# PixHawk_Fire_v1_4.net
KiCad netlist of a schematic drawn in EAGLE
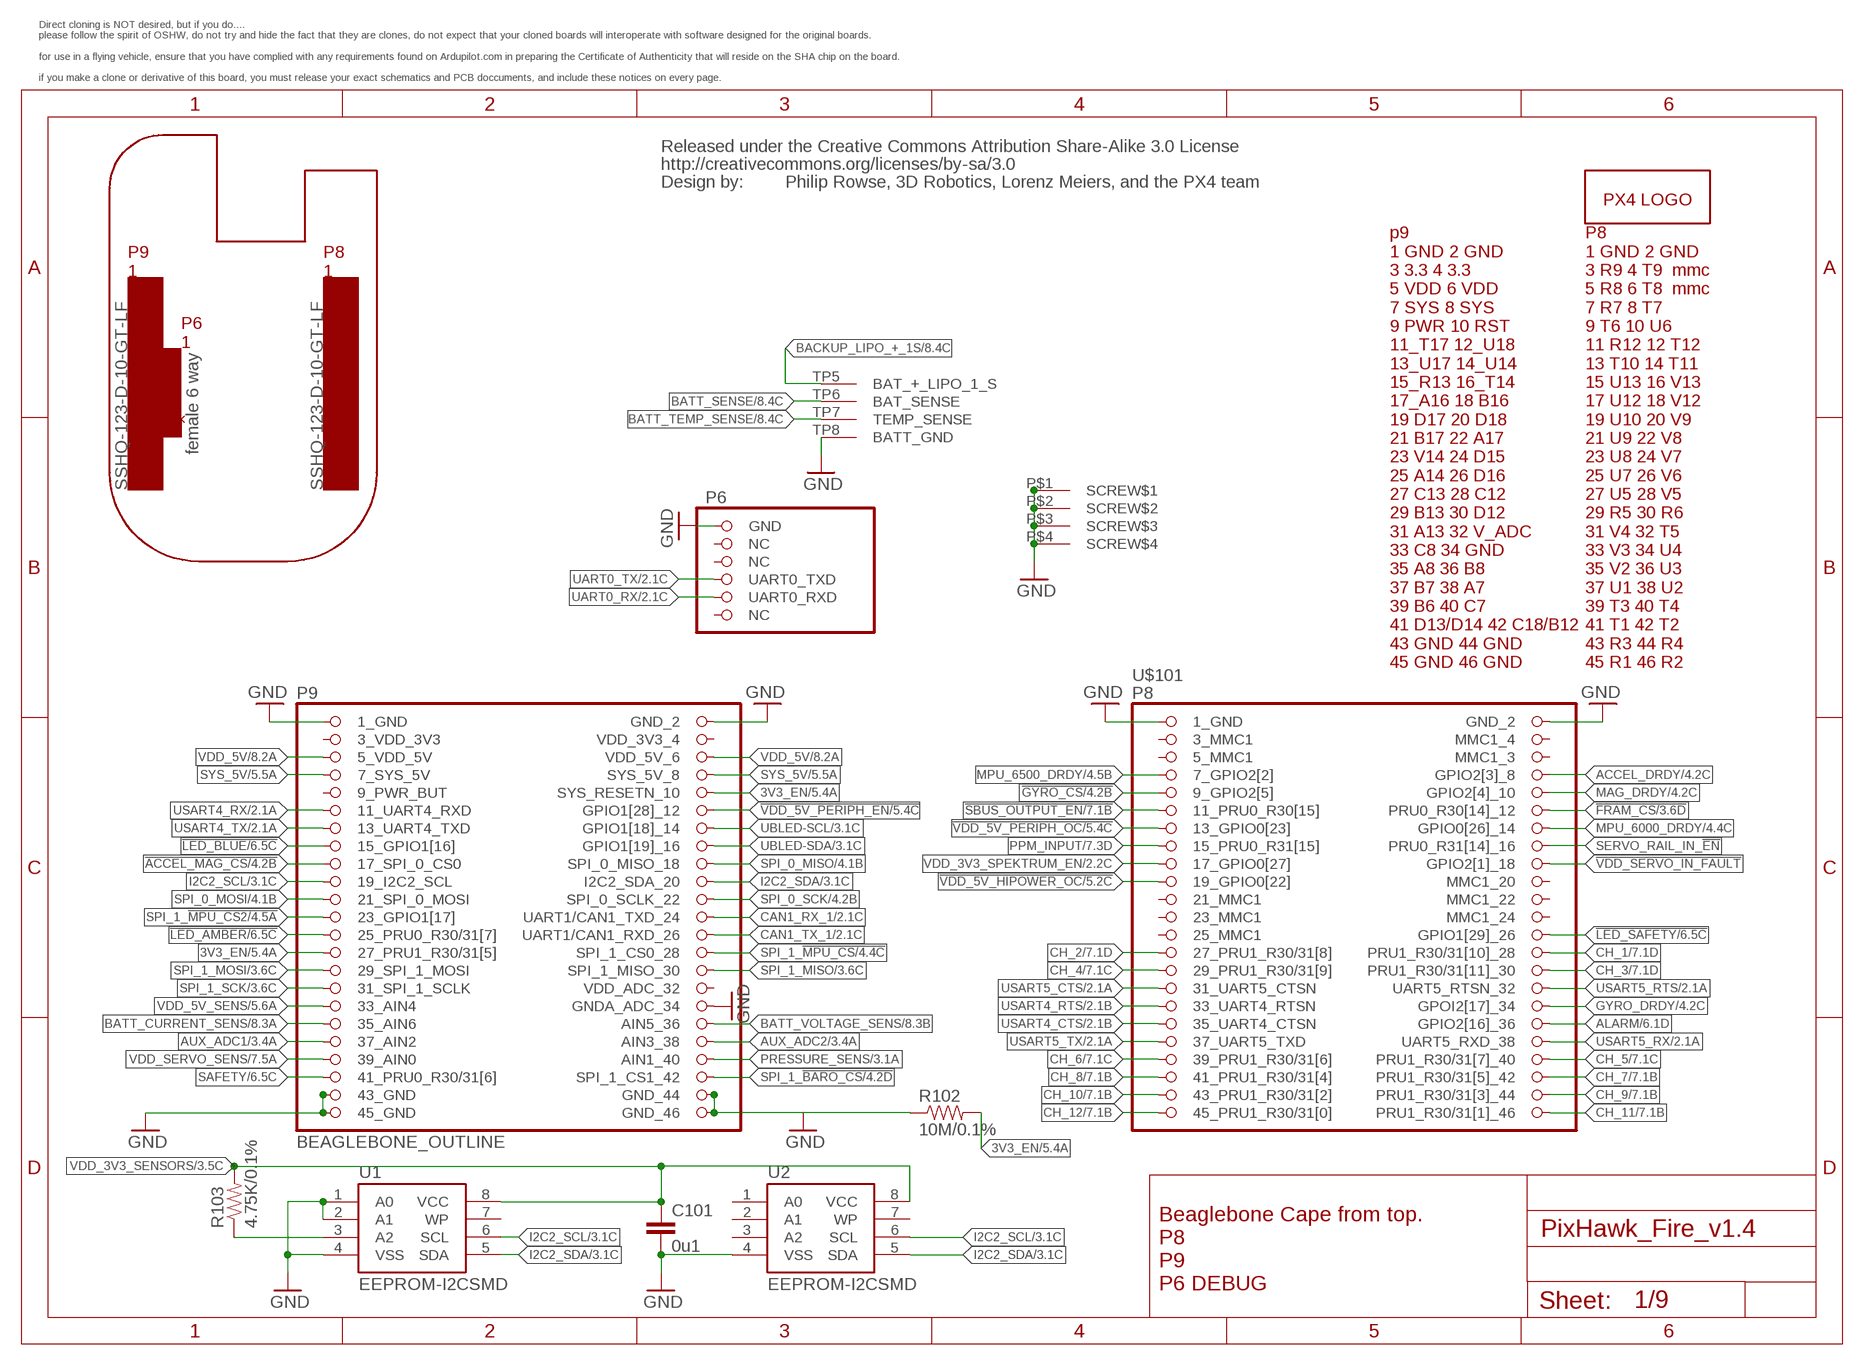
[diagram p0: schematic, sheet 1]
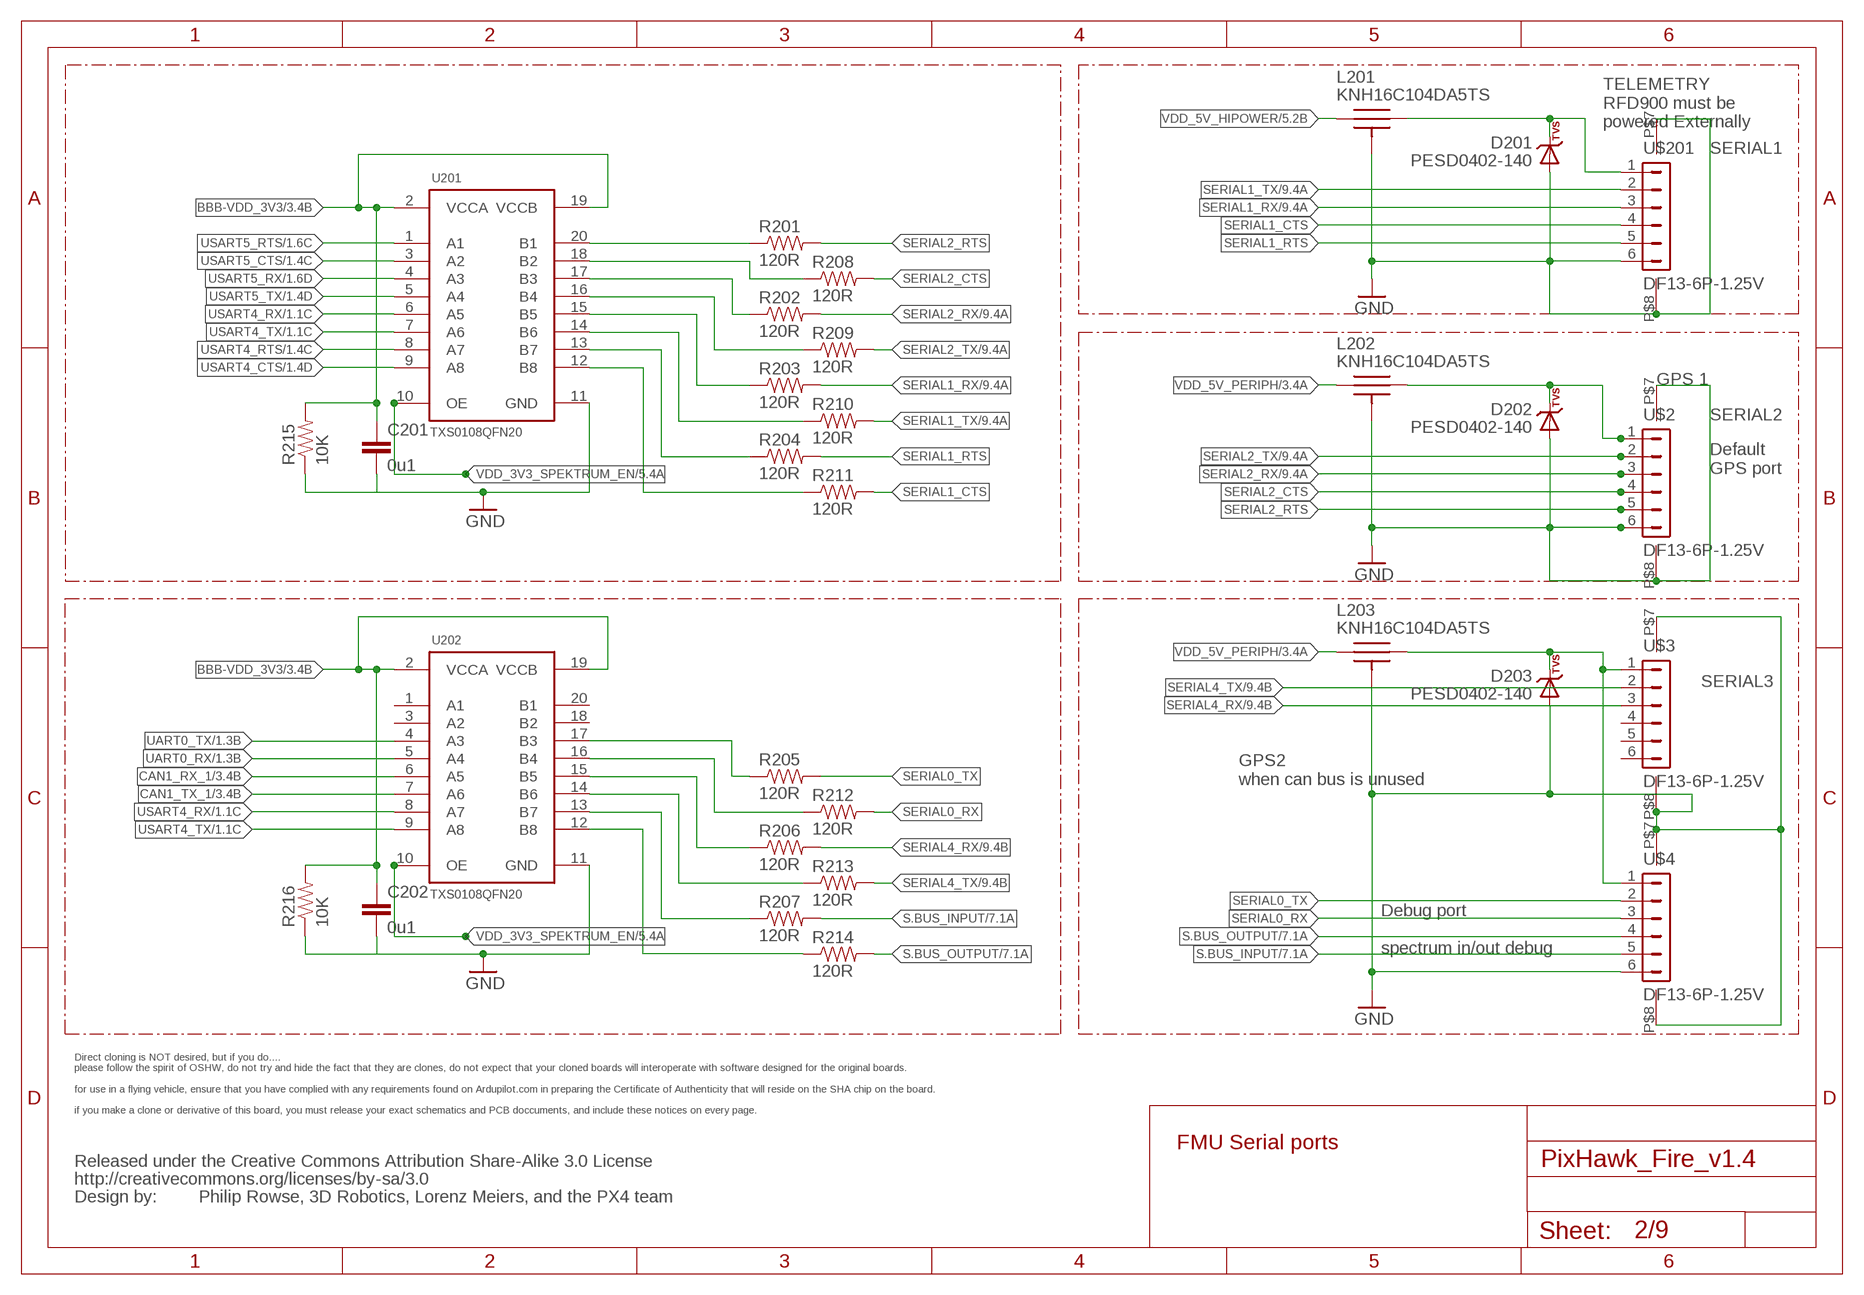
[diagram p1: schematic, sheet 2]
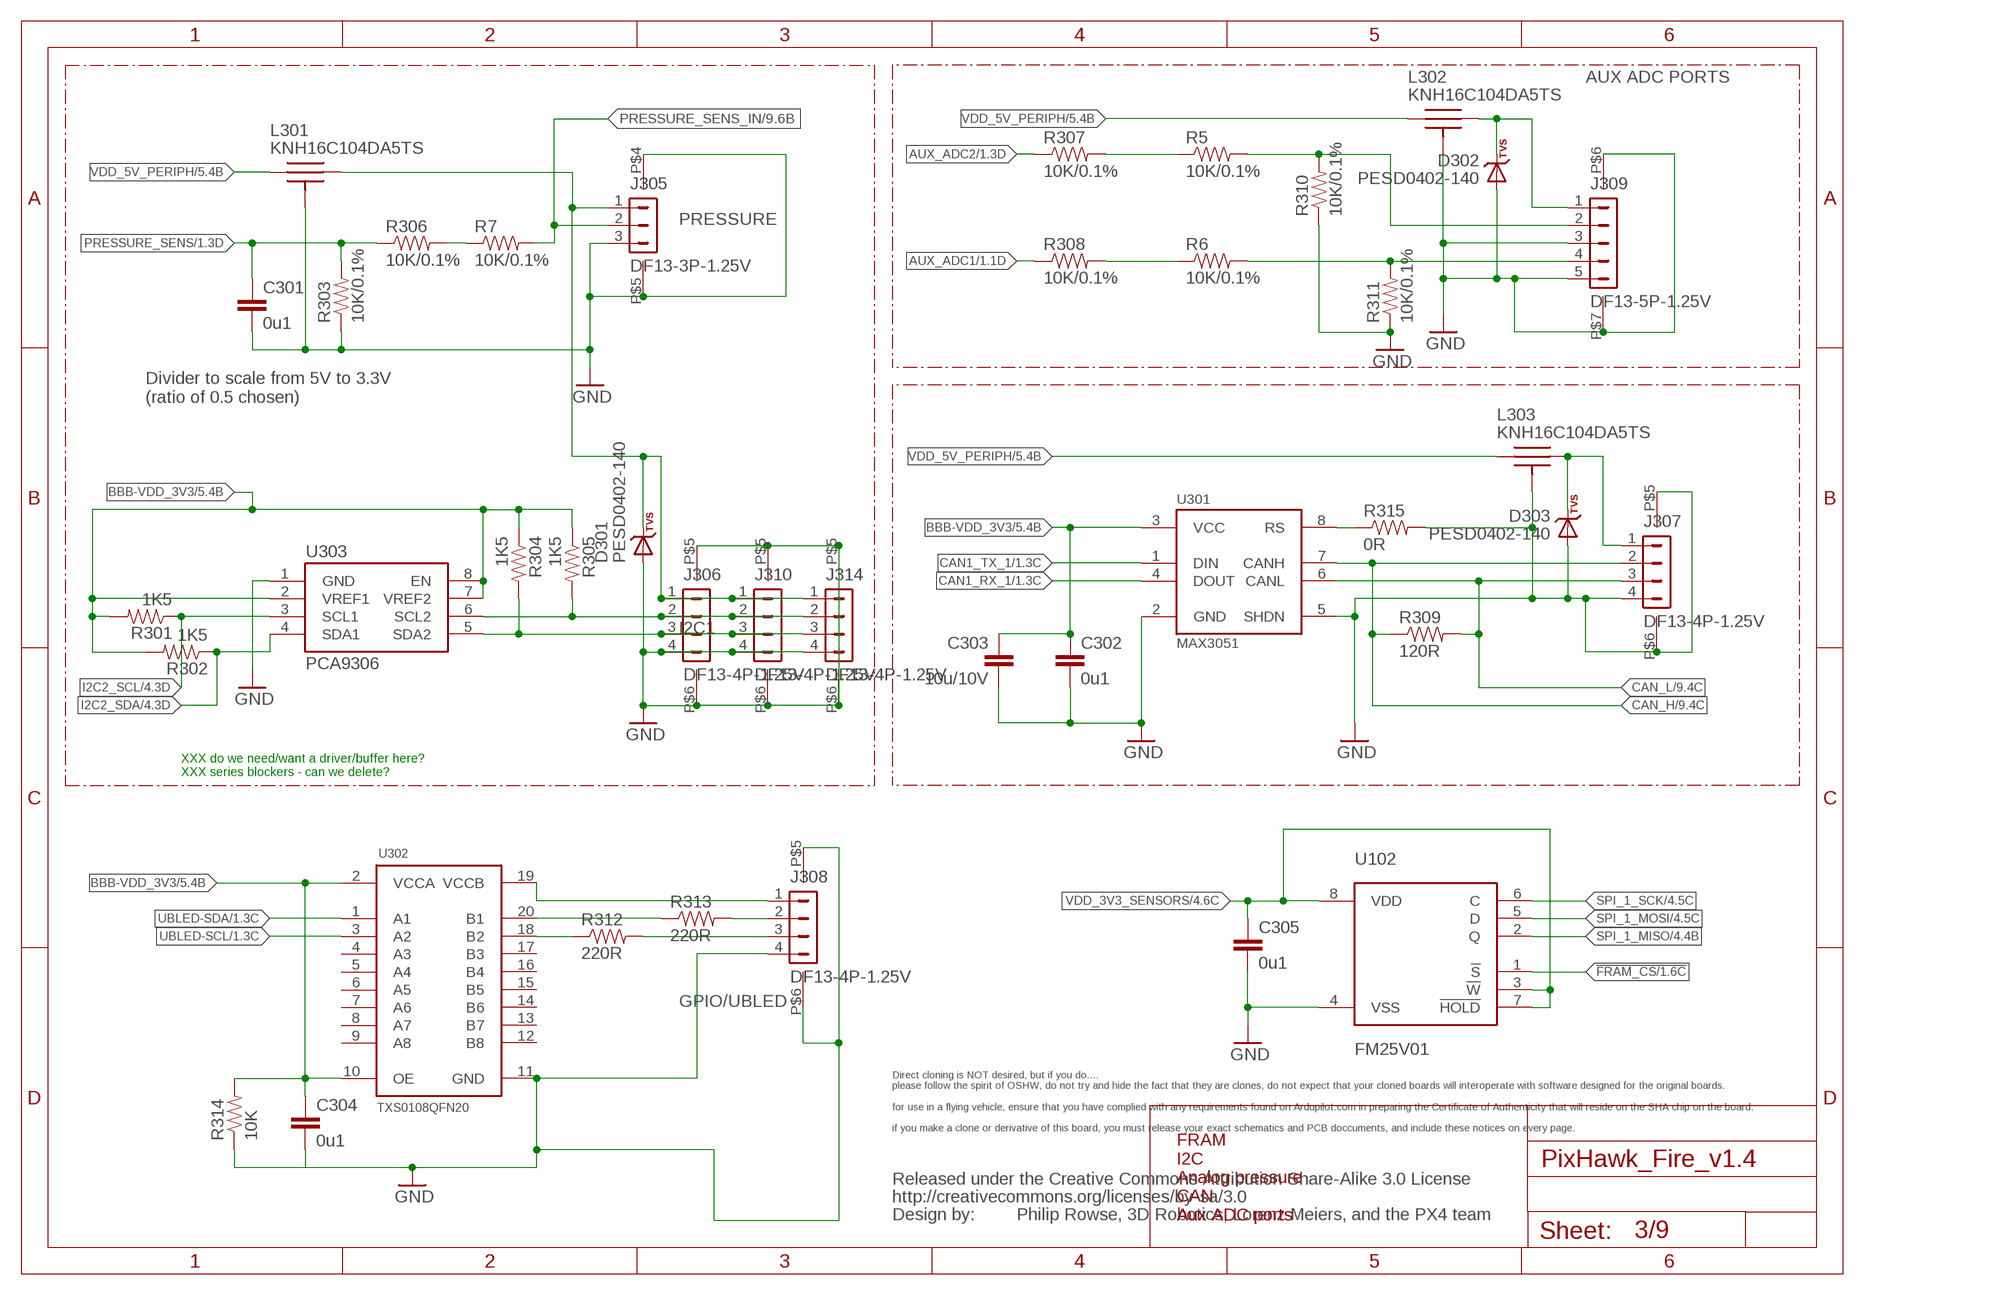
[diagram p2: schematic, sheet 3]
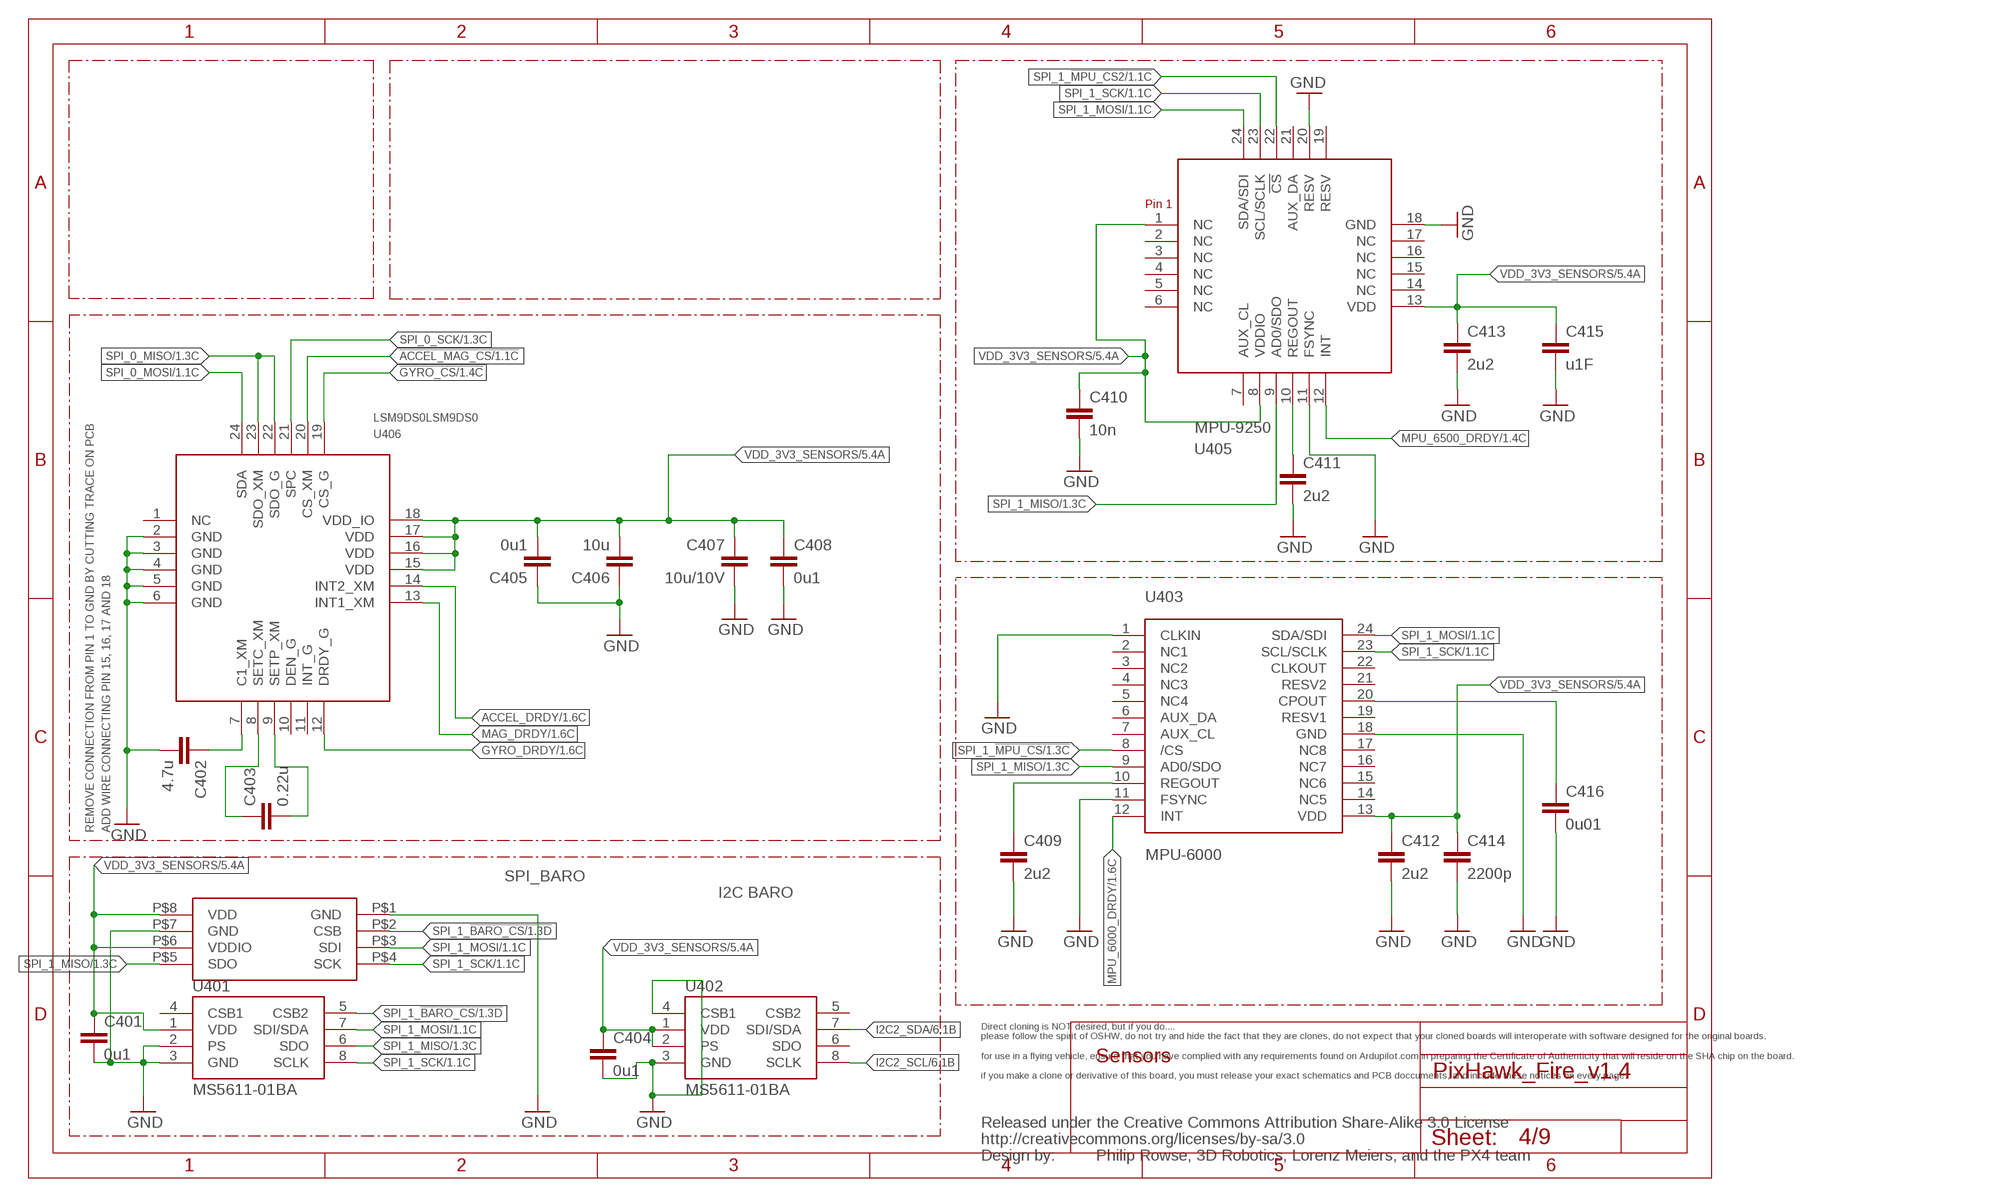
[diagram p3: schematic, sheet 4]
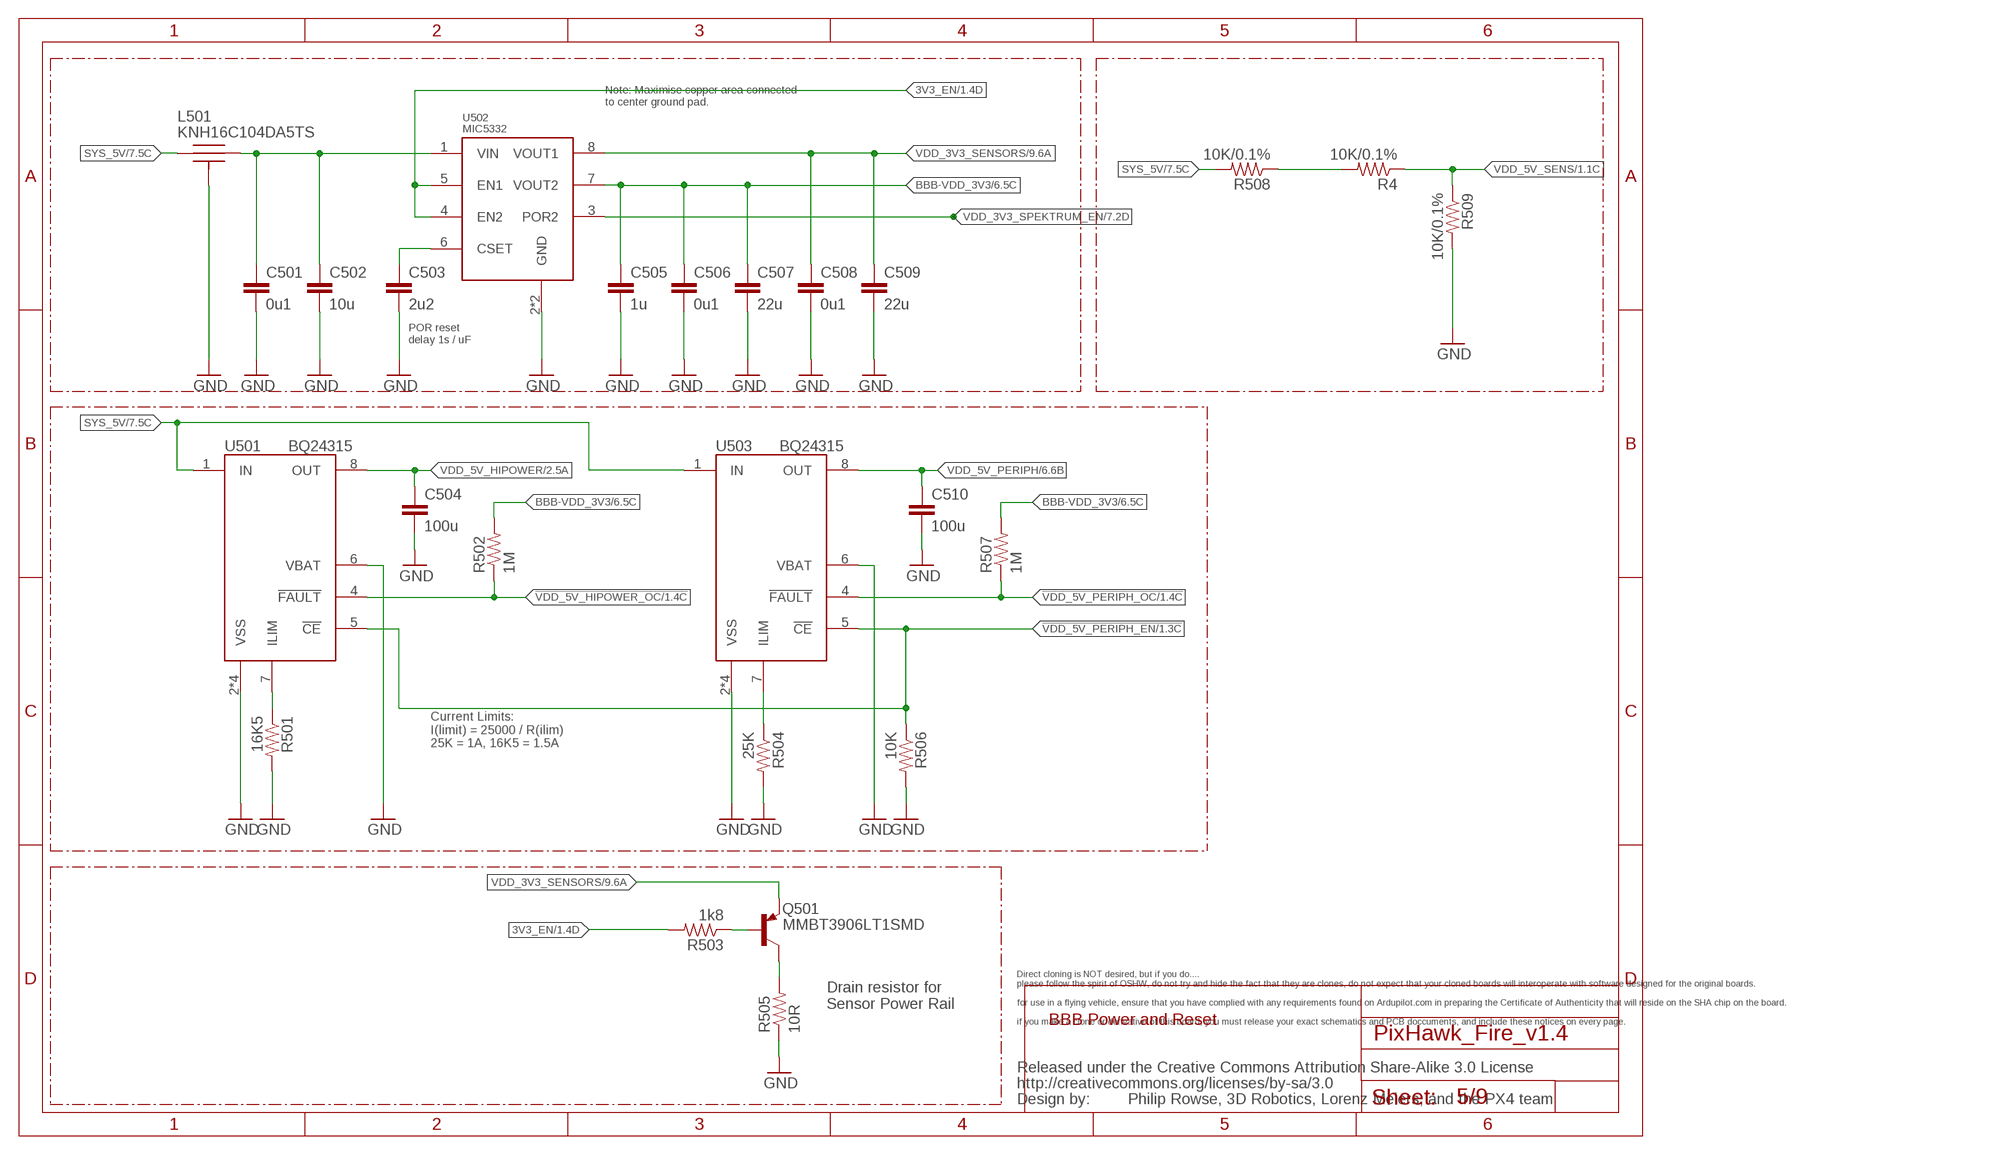
[diagram p4: schematic, sheet 5]
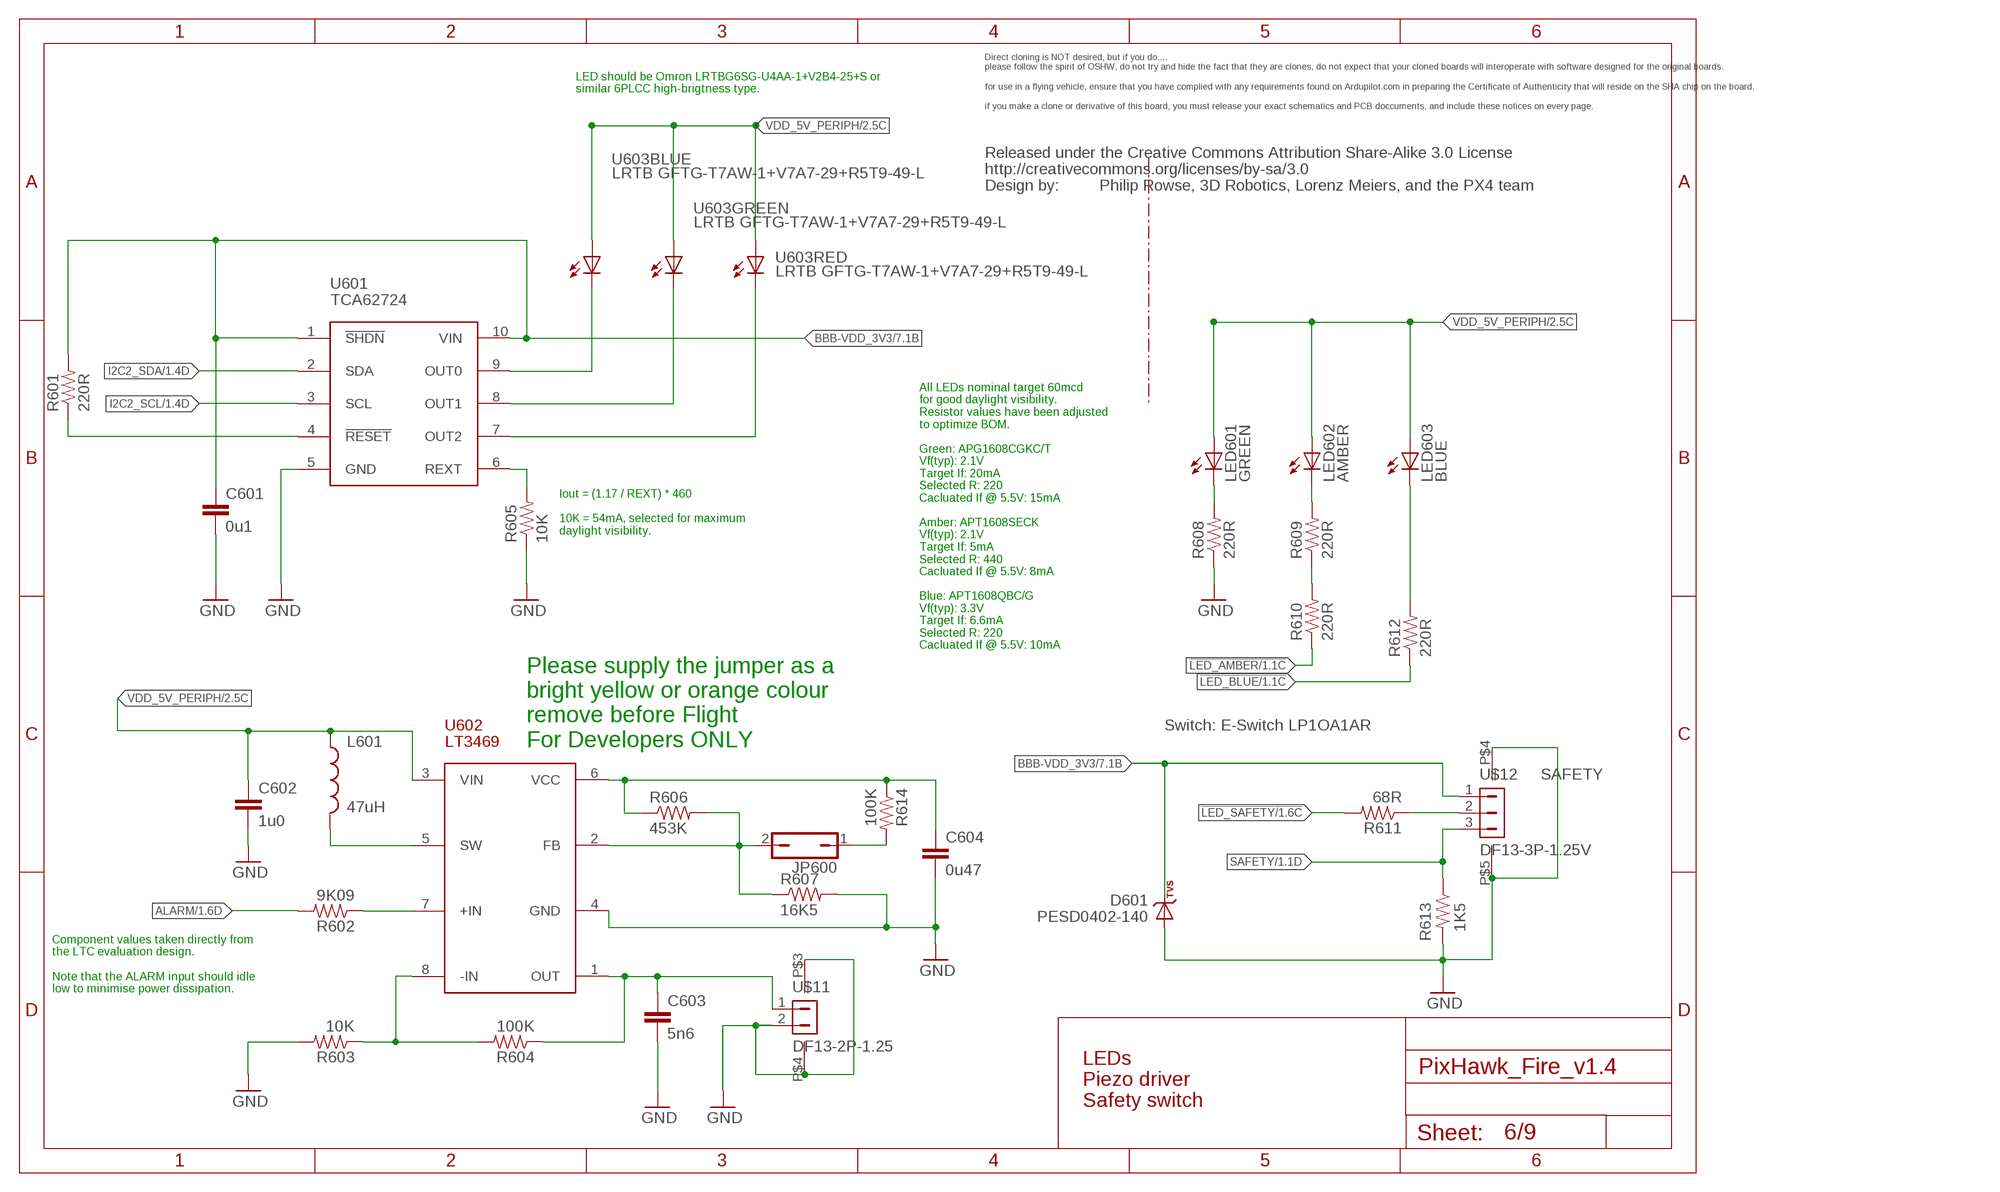
[diagram p5: schematic, sheet 6]
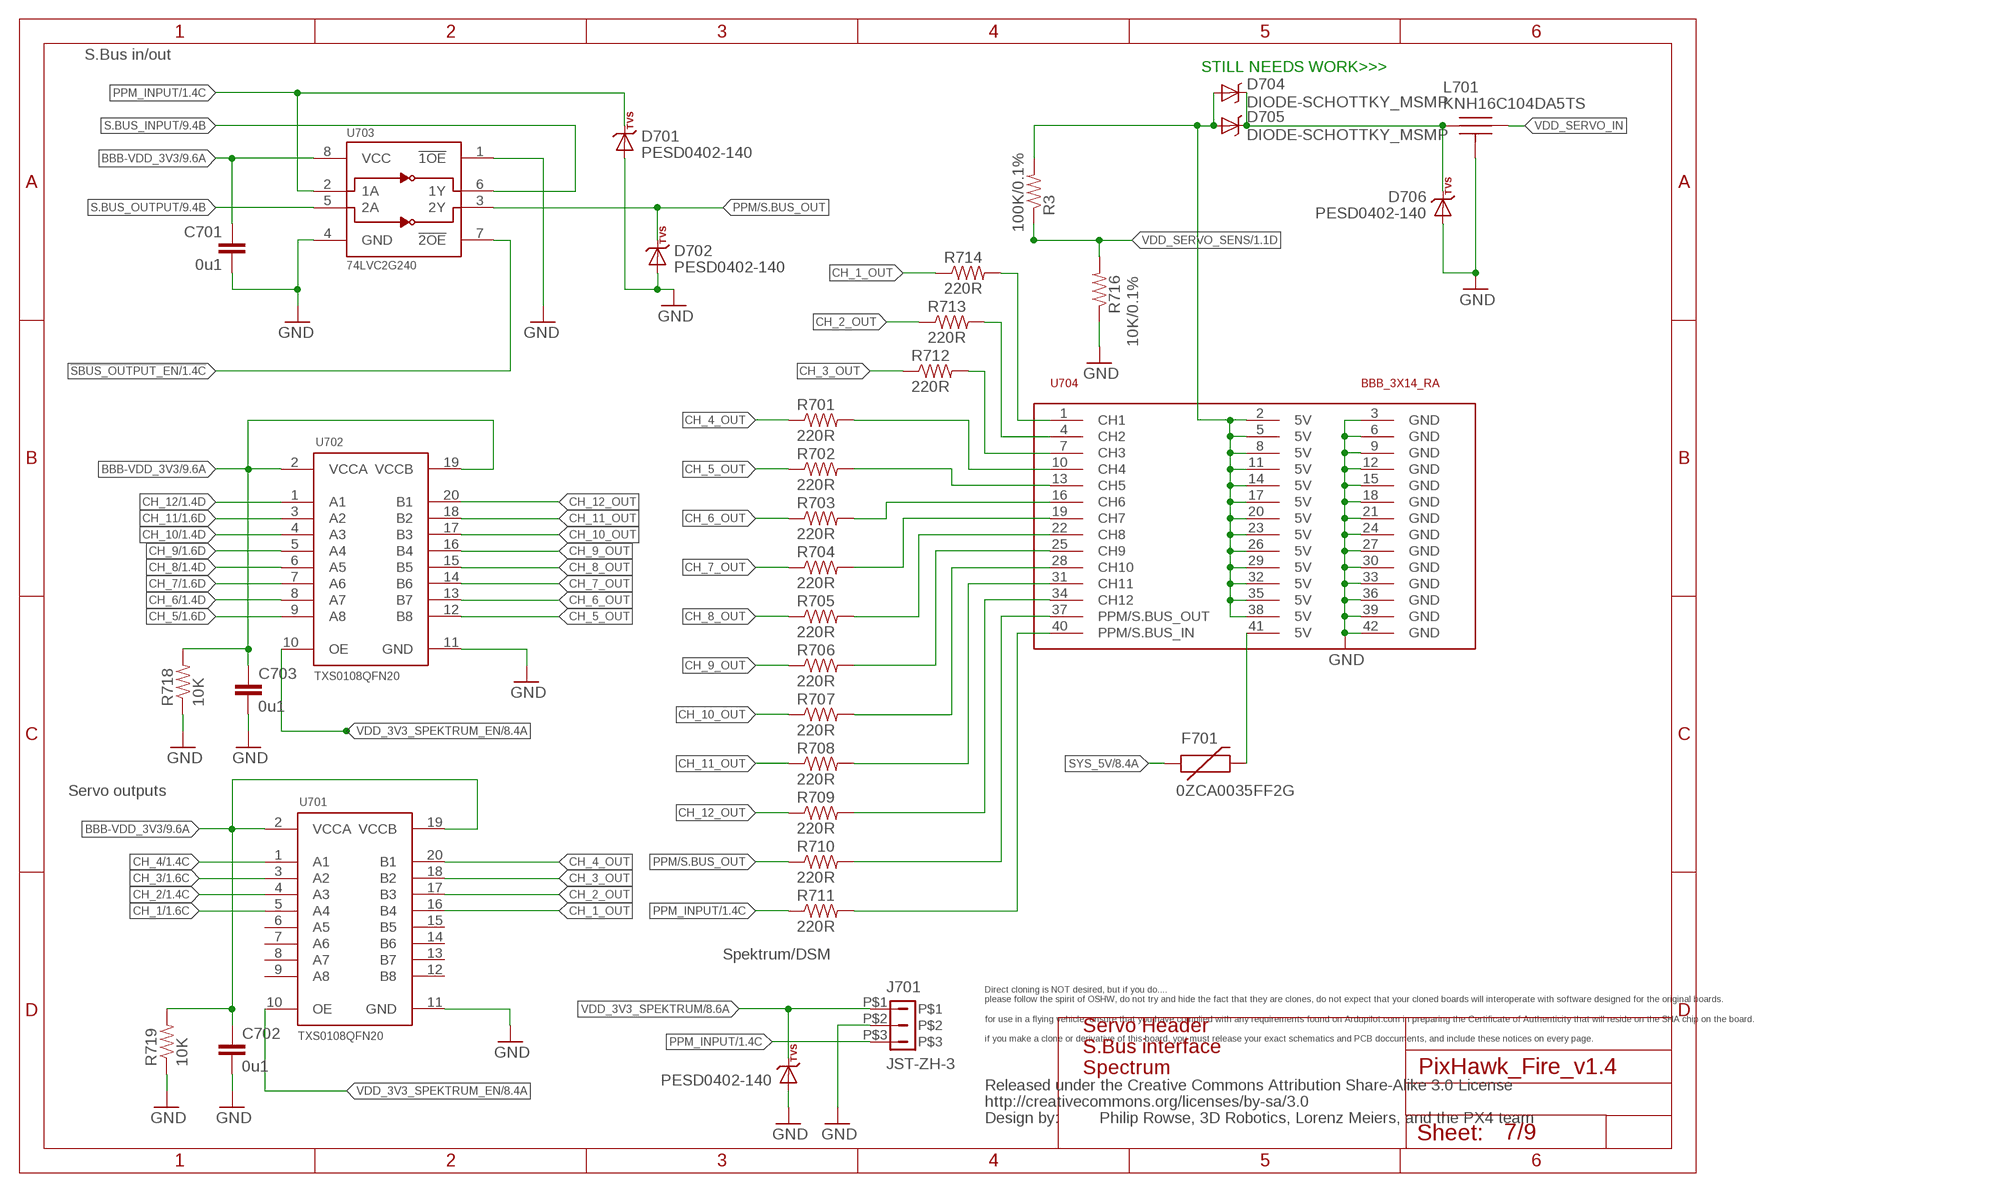
[diagram p6: schematic, sheet 7]
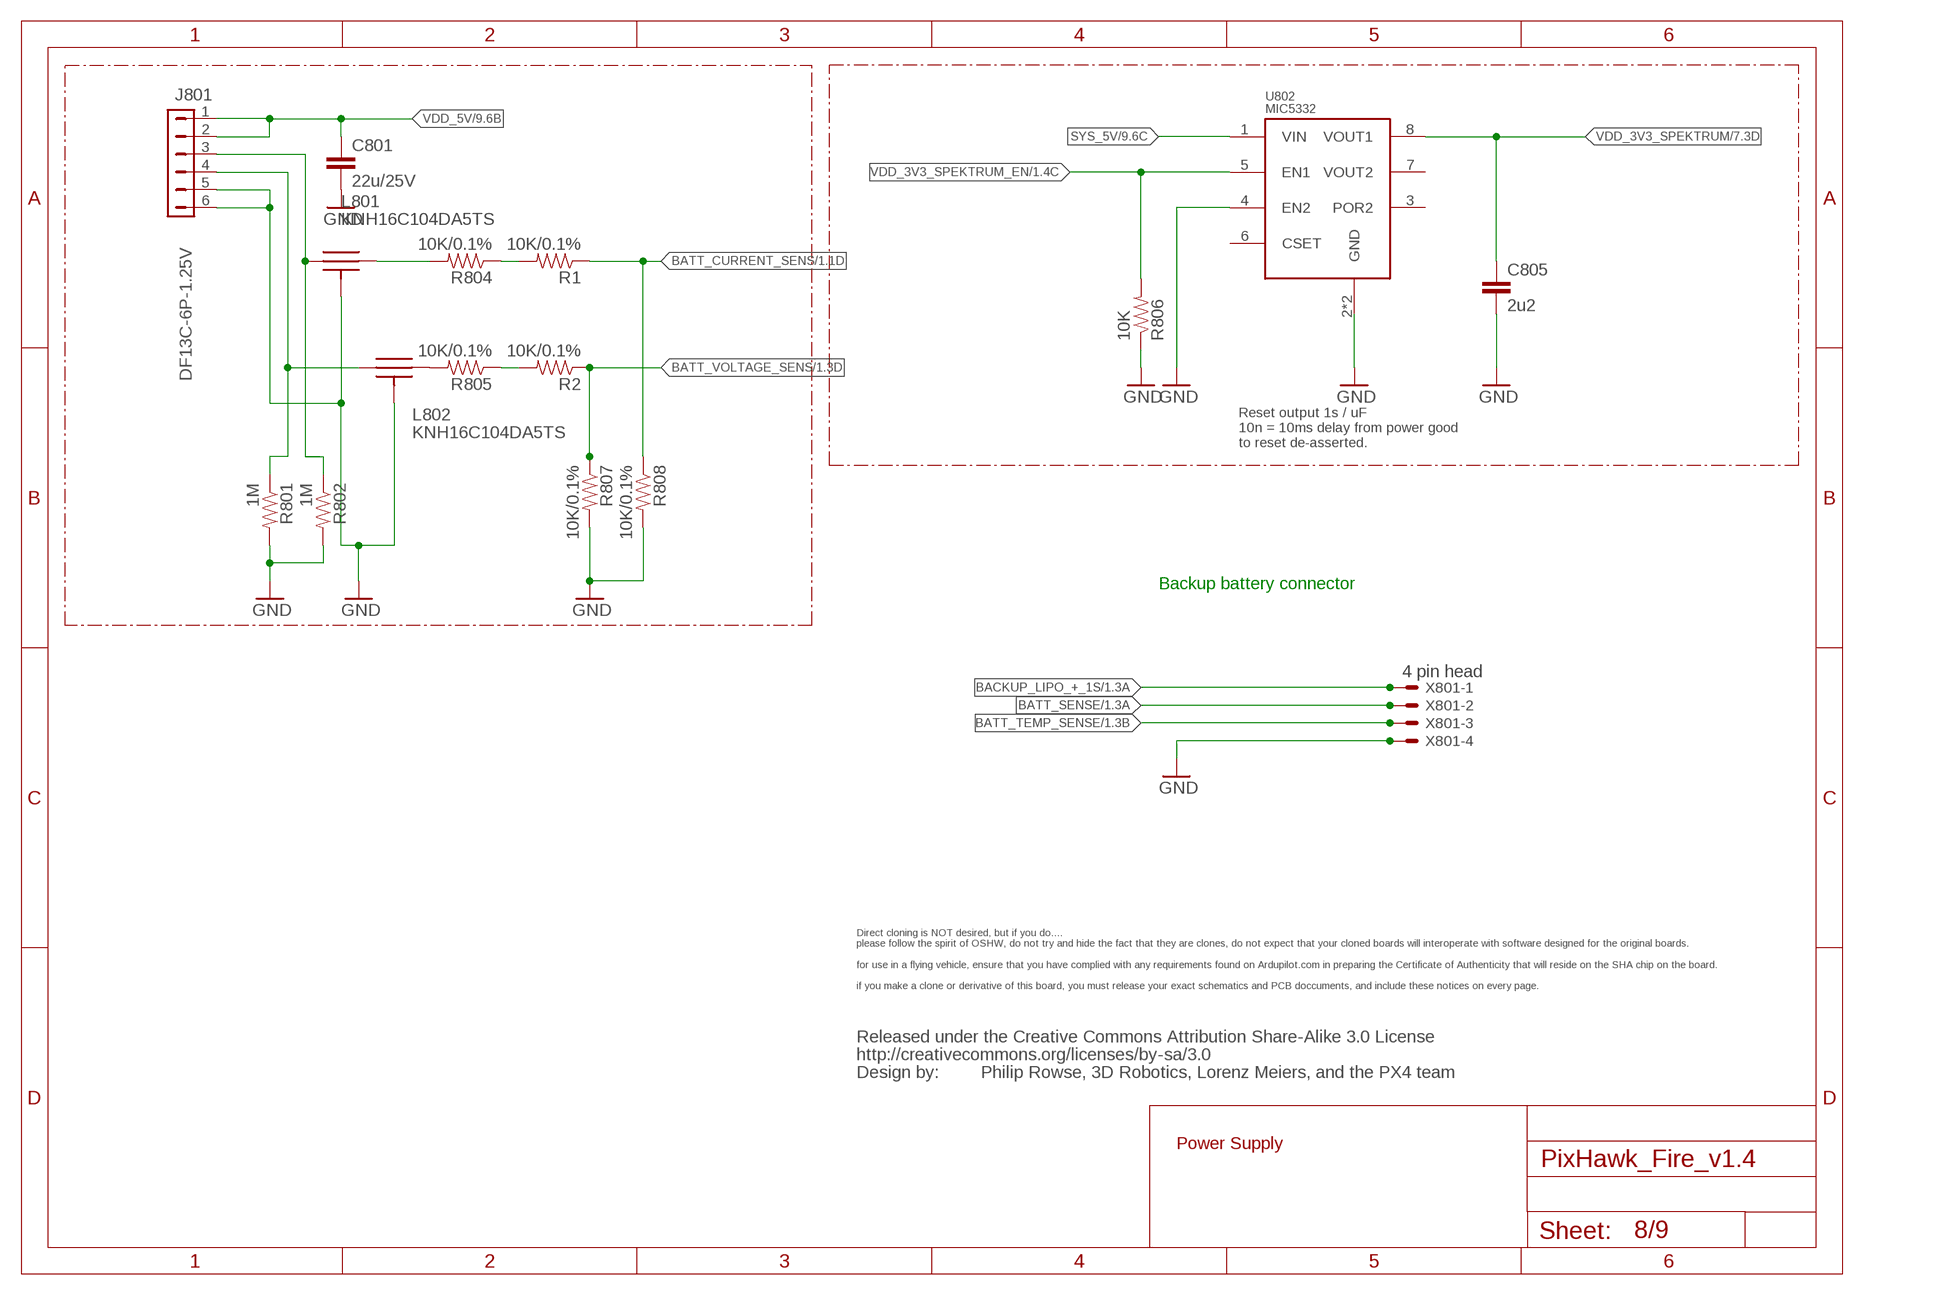
[diagram p7: schematic, sheet 8]
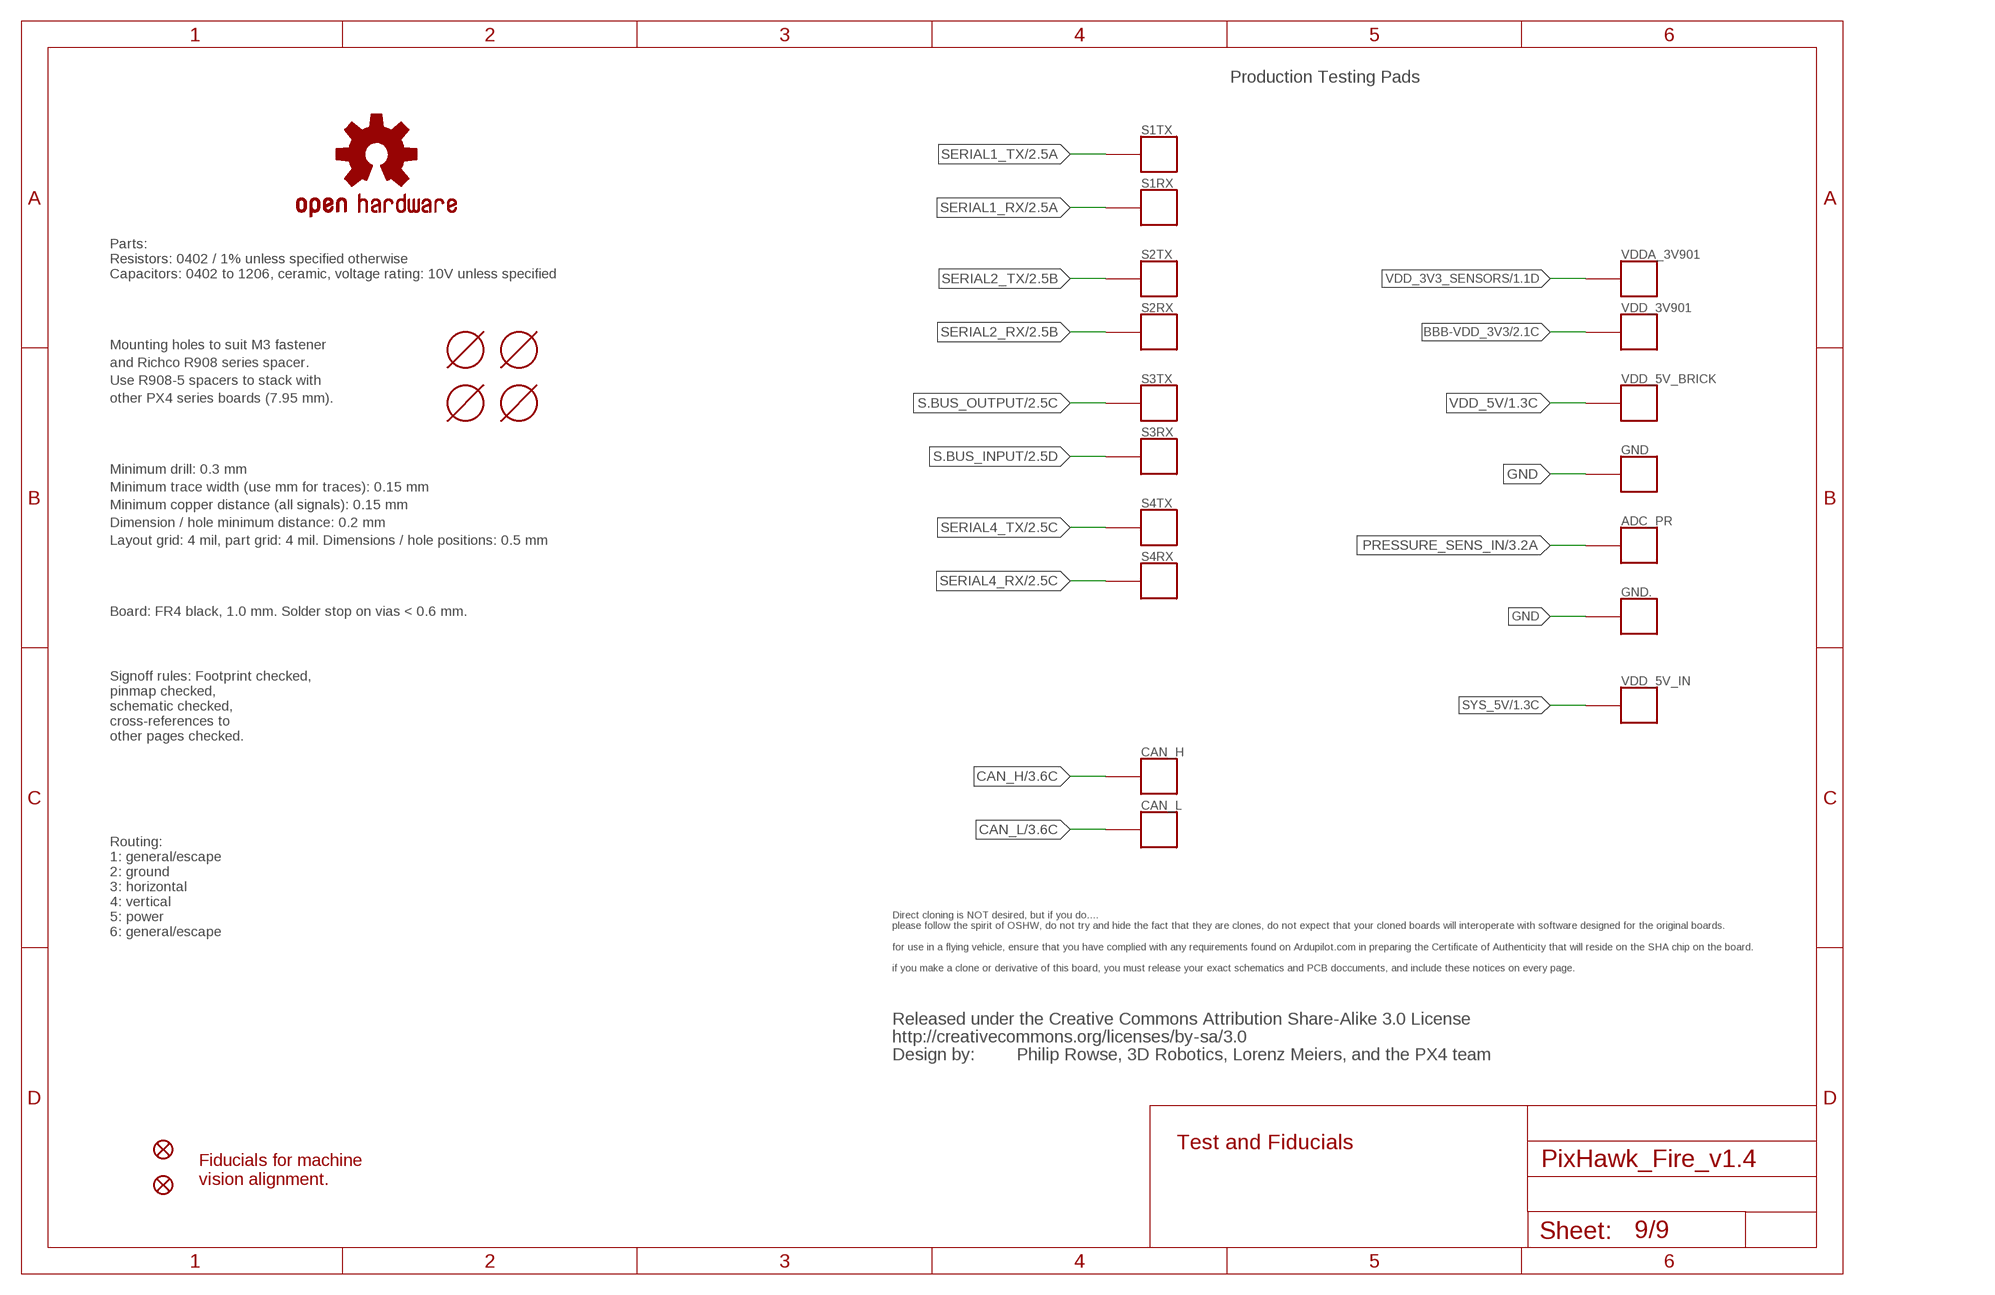
[diagram p8: schematic, sheet 9]

(export (version "E")
  (design (tool "Eeschema 10.0.6"))
  (components
    (comp (ref "C401")
      (value "0u1")
      (footprint "eagle-import:0402-CAP")
      (fields (field (name "PARTNO") "CC0402ZRY5V7BB104"))
      (libsource (lib "eagle-import") (part "CAP0402"))
    )
    (comp (ref "C402")
      (value "4.7u")
      (footprint "eagle-import:0603-CAP")
      (fields (field (name "PARTNO") "C1608X7S1A475K080AC"))
      (libsource (lib "eagle-import") (part "CAP0603"))
    )
    (comp (ref "C403")
      (value "0.22u")
      (footprint "eagle-import:0603-CAP")
      (fields (field (name "PARTNO") "CL10B224JP8NNNC"))
      (libsource (lib "eagle-import") (part "CAP0603"))
    )
    (comp (ref "C404")
      (value "0u1")
      (footprint "eagle-import:0402-CAP")
      (fields (field (name "PARTNO") "CC0402ZRY5V7BB104"))
      (libsource (lib "eagle-import") (part "CAP0402"))
    )
    (comp (ref "C405")
      (value "0u1")
      (footprint "eagle-import:0603-CAP")
      (fields (field (name "PARTNO") "CL10B104JO8NNNC"))
      (libsource (lib "eagle-import") (part "CAP0603"))
    )
    (comp (ref "C406")
      (value "10u")
      (footprint "eagle-import:0603-CAP")
      (fields (field (name "PARTNO") "C1608X7S0J106M080AC"))
      (libsource (lib "eagle-import") (part "CAP0603"))
    )
    (comp (ref "C407")
      (value "10u/10V")
      (footprint "eagle-import:0805-CAP")
      (fields (field (name "PARTNO") "CC0805ZKY5V6BB106"))
      (libsource (lib "eagle-import") (part "CAP0805"))
    )
    (comp (ref "C408")
      (value "0u1")
      (footprint "eagle-import:0402-CAP")
      (fields (field (name "PARTNO") "CC0402ZRY5V7BB104"))
      (libsource (lib "eagle-import") (part "CAP0402"))
    )
    (comp (ref "C409")
      (value "2u2")
      (footprint "eagle-import:0603-CAP")
      (fields (field (name "PARTNO") "C1608X6S1C225K080AC"))
      (libsource (lib "eagle-import") (part "CAP0603"))
    )
    (comp (ref "C410")
      (value "10n")
      (footprint "eagle-import:0603-CAP")
      (fields (field (name "PARTNO") "C0603C103J5RAC7411"))
      (libsource (lib "eagle-import") (part "CAP0603"))
    )
    (comp (ref "C411")
      (value "2u2")
      (footprint "eagle-import:0603-CAP")
      (fields (field (name "PARTNO") "C1608X6S1C225K080AC"))
      (libsource (lib "eagle-import") (part "CAP0603"))
    )
    (comp (ref "C412")
      (value "2u2")
      (footprint "eagle-import:0603-CAP")
      (fields (field (name "PARTNO") "CGA3E1X7R0J225K080AC"))
      (libsource (lib "eagle-import") (part "CAP0603"))
    )
    (comp (ref "C413")
      (value "2u2")
      (footprint "eagle-import:0603-CAP")
      (libsource (lib "eagle-import") (part "CAP0603"))
    )
    (comp (ref "C414")
      (value "2200p")
      (footprint "eagle-import:0402-CAP")
      (fields (field (name "PARTNO") "C0603C222J5RACTU"))
      (libsource (lib "eagle-import") (part "CAP0402"))
    )
    (comp (ref "C415")
      (value "u1F")
      (footprint "eagle-import:0402-CAP")
      (fields (field (name "PARTNO") "CC0402ZRY5V7BB104"))
      (libsource (lib "eagle-import") (part "CAP0402"))
    )
    (comp (ref "C416")
      (value "0u01")
      (footprint "eagle-import:0603-CAP")
      (fields (field (name "PARTNO") "06033C103JAT2A"))
      (libsource (lib "eagle-import") (part "CAP0603"))
    )
    (comp (ref "U$8")
      (value "CREATIVE_COMMONS")
      (footprint "eagle-import:CREATIVE_COMMONS")
      (libsource (lib "eagle-import") (part "CREATIVE_COMMONS"))
    )
    (comp (ref "U401")
      (value "MS5611-01BA")
      (footprint "eagle-import:MS5611-01BA")
      (libsource (lib "eagle-import") (part "MS5611-01BA"))
    )
    (comp (ref "U402")
      (value "MS5611-01BA")
      (footprint "eagle-import:MS5611-01BA")
      (libsource (lib "eagle-import") (part "MS5611-01BA"))
    )
    (comp (ref "U403")
      (value "MPU-6000")
      (footprint "eagle-import:QFN-24")
      (libsource (lib "eagle-import") (part "MPU-6000"))
    )
    (comp (ref "U405")
      (value "MPU-9250")
      (footprint "eagle-import:MPU-6500")
      (libsource (lib "eagle-import") (part "MPU-6500"))
    )
    (comp (ref "U406")
      (value "LSM9DS0LSM9DS0")
      (footprint "eagle-import:LSM9DS0")
      (fields (field (name "PARTNO") "LSM9DS0TR"))
      (libsource (lib "eagle-import") (part "LSM9DS0LSM9DS0"))
    )
    (comp (ref "U407")
      (value "BMP280_PRELIM")
      (footprint "eagle-import:BMP280_PRELIM")
      (libsource (lib "eagle-import") (part "BMP280_PRELIM"))
    )
    (comp (ref "C801")
      (value "22u/25V")
      (footprint "eagle-import:0805-CAP")
      (fields (field (name "PARTNO") "CL21A226MAQNNNE"))
      (libsource (lib "eagle-import") (part "CAP0805"))
    )
    (comp (ref "C805")
      (value "2u2")
      (footprint "eagle-import:0402-CAP")
      (fields (field (name "PARTNO") "CC0603ZRY5V6BB225"))
      (libsource (lib "eagle-import") (part "CAP0402"))
    )
    (comp (ref "J801")
      (value "DF13C-6P-1.25V")
      (footprint "eagle-import:DF13C-6P-1.25V")
      (fields (field (name "PARTNO") "DF13C-6P-1.25V(20)"))
      (libsource (lib "eagle-import") (part "DF13-6P-1.25V"))
    )
    (comp (ref "L801")
      (value "KNH16C104DA5TS")
      (footprint "eagle-import:KYOCERA-KNH16-DA")
      (libsource (lib "eagle-import") (part "KNH16C104DA5TS"))
    )
    (comp (ref "L802")
      (value "KNH16C104DA5TS")
      (footprint "eagle-import:KYOCERA-KNH16-DA")
      (libsource (lib "eagle-import") (part "KNH16C104DA5TS"))
    )
    (comp (ref "R1")
      (value "10K/0.1%")
      (footprint "eagle-import:0402-RES")
      (fields (field (name "PARTNO") "ERA-2AEB103X"))
      (libsource (lib "eagle-import") (part "RESISTOR0402-RES"))
    )
    (comp (ref "R2")
      (value "10K/0.1%")
      (footprint "eagle-import:0402-RES")
      (fields (field (name "PARTNO") "ERA-2AEB103X"))
      (libsource (lib "eagle-import") (part "RESISTOR0402-RES"))
    )
    (comp (ref "R801")
      (value "1M")
      (footprint "eagle-import:0402-RES")
      (fields (field (name "PARTNO") "RC0402FR-071ML"))
      (libsource (lib "eagle-import") (part "RESISTOR0402-RES"))
    )
    (comp (ref "R802")
      (value "1M")
      (footprint "eagle-import:0402-RES")
      (fields (field (name "PARTNO") "RC0402FR-071ML"))
      (libsource (lib "eagle-import") (part "RESISTOR0402-RES"))
    )
    (comp (ref "R804")
      (value "10K/0.1%")
      (footprint "eagle-import:0402-RES")
      (fields (field (name "PARTNO") "ERA-2AEB103X"))
      (libsource (lib "eagle-import") (part "RESISTOR0402-RES"))
    )
    (comp (ref "R805")
      (value "10K/0.1%")
      (footprint "eagle-import:0402-RES")
      (fields (field (name "PARTNO") "ERA-2AEB103X"))
      (libsource (lib "eagle-import") (part "RESISTOR0402-RES"))
    )
    (comp (ref "R806")
      (value "10K")
      (footprint "eagle-import:0402-RES")
      (fields (field (name "PARTNO") "ERA-2AEB103X"))
      (libsource (lib "eagle-import") (part "RESISTOR0402-RES"))
    )
    (comp (ref "R807")
      (value "10K/0.1%")
      (footprint "eagle-import:0402-RES")
      (fields (field (name "PARTNO") "ERA-2AEB103X"))
      (libsource (lib "eagle-import") (part "RESISTOR0402-RES"))
    )
    (comp (ref "R808")
      (value "10K/0.1%")
      (footprint "eagle-import:0402-RES")
      (fields (field (name "PARTNO") "ERA-2AEB103X"))
      (libsource (lib "eagle-import") (part "RESISTOR0402-RES"))
    )
    (comp (ref "U$14")
      (value "CREATIVE_COMMONS")
      (footprint "eagle-import:CREATIVE_COMMONS")
      (libsource (lib "eagle-import") (part "CREATIVE_COMMONS"))
    )
    (comp (ref "U802")
      (value "MIC5332")
      (footprint "eagle-import:MLF-8-EPAD")
      (fields (field (name "PARTNO") "MIC5332-SSYMT"))
      (libsource (lib "eagle-import") (part "MIC5332"))
    )
    (comp (ref "X801")
      (value "4 pin head")
      (footprint "eagle-import:53047-04")
      (fields (field (name "PARTNO") "53047-04"))
      (libsource (lib "eagle-import") (part "53?-04047"))
    )
    (comp (ref "ADC_PR")
      (value "PAD.04")
      (footprint "eagle-import:PAD.04X.04")
      (libsource (lib "eagle-import") (part "PAD.04"))
    )
    (comp (ref "CAN_H")
      (value "PAD.04")
      (footprint "eagle-import:PAD.04X.04")
      (libsource (lib "eagle-import") (part "PAD.04"))
    )
    (comp (ref "CAN_L")
      (value "PAD.04")
      (footprint "eagle-import:PAD.04X.04")
      (libsource (lib "eagle-import") (part "PAD.04"))
    )
    (comp (ref "GND")
      (value "PAD.04")
      (footprint "eagle-import:PAD.04X.04")
      (libsource (lib "eagle-import") (part "PAD.04"))
    )
    (comp (ref "GND.")
      (value "PAD.04")
      (footprint "eagle-import:PAD.04X.04")
      (libsource (lib "eagle-import") (part "PAD.04"))
    )
    (comp (ref "JP901")
      (value "FIDUCIAL1.5X3")
      (footprint "eagle-import:FIDUCIAL-1.5X3")
      (libsource (lib "eagle-import") (part "FIDUCIAL1.5X3"))
    )
    (comp (ref "JP902")
      (value "FIDUCIAL1.5X3")
      (footprint "eagle-import:FIDUCIAL-1.5X3")
      (libsource (lib "eagle-import") (part "FIDUCIAL1.5X3"))
    )
    (comp (ref "M3_MOUNT901")
      (value "MOUNT-HOLE3.1MM")
      (footprint "eagle-import:MOUNT-HOLE3.1")
      (libsource (lib "eagle-import") (part "MOUNT-HOLE3.1MM"))
    )
    (comp (ref "M3_MOUNT902")
      (value "MOUNT-HOLE3.1MM")
      (footprint "eagle-import:MOUNT-HOLE3.1")
      (libsource (lib "eagle-import") (part "MOUNT-HOLE3.1MM"))
    )
    (comp (ref "M3_MOUNT903")
      (value "MOUNT-HOLE3.1MM")
      (footprint "eagle-import:MOUNT-HOLE3.1")
      (libsource (lib "eagle-import") (part "MOUNT-HOLE3.1MM"))
    )
    (comp (ref "M3_MOUNT904")
      (value "MOUNT-HOLE3.1MM")
      (footprint "eagle-import:MOUNT-HOLE3.1")
      (libsource (lib "eagle-import") (part "MOUNT-HOLE3.1MM"))
    )
    (comp (ref "OSHW_LOGO")
      (value "OSHW-LOGOS")
      (footprint "eagle-import:OSHW-LOGO-S")
      (libsource (lib "eagle-import") (part "OSHW-LOGOS"))
    )
    (comp (ref "S1RX")
      (value "PAD.04")
      (footprint "eagle-import:PAD.04X.04")
      (libsource (lib "eagle-import") (part "PAD.04"))
    )
    (comp (ref "S1TX")
      (value "PAD.04")
      (footprint "eagle-import:PAD.04X.04")
      (libsource (lib "eagle-import") (part "PAD.04"))
    )
    (comp (ref "S2RX")
      (value "PAD.04")
      (footprint "eagle-import:PAD.04X.04")
      (libsource (lib "eagle-import") (part "PAD.04"))
    )
    (comp (ref "S2TX")
      (value "PAD.04")
      (footprint "eagle-import:PAD.04X.04")
      (libsource (lib "eagle-import") (part "PAD.04"))
    )
    (comp (ref "S3RX")
      (value "PAD.04")
      (footprint "eagle-import:PAD.04X.04")
      (libsource (lib "eagle-import") (part "PAD.04"))
    )
    (comp (ref "S3TX")
      (value "PAD.04")
      (footprint "eagle-import:PAD.04X.04")
      (libsource (lib "eagle-import") (part "PAD.04"))
    )
    (comp (ref "S4RX")
      (value "PAD.04")
      (footprint "eagle-import:PAD.04X.04")
      (libsource (lib "eagle-import") (part "PAD.04"))
    )
    (comp (ref "S4TX")
      (value "PAD.04")
      (footprint "eagle-import:PAD.04X.04")
      (libsource (lib "eagle-import") (part "PAD.04"))
    )
    (comp (ref "U$15")
      (value "CREATIVE_COMMONS")
      (footprint "eagle-import:CREATIVE_COMMONS")
      (libsource (lib "eagle-import") (part "CREATIVE_COMMONS"))
    )
    (comp (ref "VDDA_3V901")
      (value "PAD.04")
      (footprint "eagle-import:PAD.04X.04")
      (libsource (lib "eagle-import") (part "PAD.04"))
    )
    (comp (ref "VDD_3V901")
      (value "PAD.04")
      (footprint "eagle-import:PAD.04X.04")
      (libsource (lib "eagle-import") (part "PAD.04"))
    )
    (comp (ref "VDD_5V_BRICK")
      (value "PAD.04")
      (footprint "eagle-import:PAD.04X.04")
      (libsource (lib "eagle-import") (part "PAD.04"))
    )
    (comp (ref "VDD_5V_IN")
      (value "PAD.04")
      (footprint "eagle-import:PAD.04X.04")
      (libsource (lib "eagle-import") (part "PAD.04"))
    )
    (comp (ref "C701")
      (value "0u1")
      (footprint "eagle-import:0402-CAP")
      (fields (field (name "PARTNO") "CC0402ZRY5V7BB104"))
      (libsource (lib "eagle-import") (part "CAP0402"))
    )
    (comp (ref "C702")
      (value "0u1")
      (footprint "eagle-import:0402-CAP")
      (fields (field (name "PARTNO") "CC0402ZRY5V7BB104"))
      (libsource (lib "eagle-import") (part "CAP0402"))
    )
    (comp (ref "C703")
      (value "0u1")
      (footprint "eagle-import:0402-CAP")
      (fields (field (name "PARTNO") "CC0402ZRY5V7BB104"))
      (libsource (lib "eagle-import") (part "CAP0402"))
    )
    (comp (ref "D701")
      (value "PESD0402-140")
      (footprint "eagle-import:0402-TVS")
      (libsource (lib "eagle-import") (part "DIODE-TVS"))
    )
    (comp (ref "D702")
      (value "PESD0402-140")
      (footprint "eagle-import:0402-TVS")
      (libsource (lib "eagle-import") (part "DIODE-TVS"))
    )
    (comp (ref "D703")
      (value "PESD0402-140")
      (footprint "eagle-import:0402-TVS")
      (libsource (lib "eagle-import") (part "DIODE-TVS"))
    )
    (comp (ref "D704")
      (value "DIODE-SCHOTTKY_MSMP")
      (footprint "eagle-import:MICROSMP")
      (fields (field (name "PARTNO") "SS14"))
      (libsource (lib "eagle-import") (part "DIODE-SCHOTTKY_MSMP"))
    )
    (comp (ref "D705")
      (value "DIODE-SCHOTTKY_MSMP")
      (footprint "eagle-import:MICROSMP")
      (fields (field (name "PARTNO") "SS14"))
      (libsource (lib "eagle-import") (part "DIODE-SCHOTTKY_MSMP"))
    )
    (comp (ref "D706")
      (value "PESD0402-140")
      (footprint "eagle-import:0402-TVS")
      (libsource (lib "eagle-import") (part "DIODE-TVS"))
    )
    (comp (ref "F701")
      (value "0ZCA0035FF2G")
      (footprint "eagle-import:PTC-1206")
      (libsource (lib "eagle-import") (part "PTCSMD"))
    )
    (comp (ref "J701")
      (value "JST-ZH-3")
      (footprint "eagle-import:JST-ZH-SMT-VERTICAL")
      (fields (field (name "PARTNO") "B3B-ZR-SM4-TF (LF)(SN)(P)"))
      (libsource (lib "eagle-import") (part "JST-ZH-3"))
    )
    (comp (ref "L701")
      (value "KNH16C104DA5TS")
      (footprint "eagle-import:KYOCERA-KNH16-DA")
      (libsource (lib "eagle-import") (part "KNH16C104DA5TS"))
    )
    (comp (ref "R3")
      (value "100K/0.1%")
      (footprint "eagle-import:0402-RES")
      (fields (field (name "PARTNO") "ERA-2AEB104X"))
      (libsource (lib "eagle-import") (part "RESISTOR0402-RES"))
    )
    (comp (ref "R701")
      (value "220R")
      (footprint "eagle-import:0402-RES")
      (fields (field (name "PARTNO") "RC0402FR-07220RL"))
      (libsource (lib "eagle-import") (part "RESISTOR0402-RES"))
    )
    (comp (ref "R702")
      (value "220R")
      (footprint "eagle-import:0402-RES")
      (fields (field (name "PARTNO") "RC0402FR-07220RL"))
      (libsource (lib "eagle-import") (part "RESISTOR0402-RES"))
    )
    (comp (ref "R703")
      (value "220R")
      (footprint "eagle-import:0402-RES")
      (fields (field (name "PARTNO") "RC0402FR-07220RL"))
      (libsource (lib "eagle-import") (part "RESISTOR0402-RES"))
    )
    (comp (ref "R704")
      (value "220R")
      (footprint "eagle-import:0402-RES")
      (fields (field (name "PARTNO") "RC0402FR-07220RL"))
      (libsource (lib "eagle-import") (part "RESISTOR0402-RES"))
    )
    (comp (ref "R705")
      (value "220R")
      (footprint "eagle-import:0402-RES")
      (fields (field (name "PARTNO") "RC0402FR-07220RL"))
      (libsource (lib "eagle-import") (part "RESISTOR0402-RES"))
    )
    (comp (ref "R706")
      (value "220R")
      (footprint "eagle-import:0402-RES")
      (fields (field (name "PARTNO") "RC0402FR-07220RL"))
      (libsource (lib "eagle-import") (part "RESISTOR0402-RES"))
    )
    (comp (ref "R707")
      (value "220R")
      (footprint "eagle-import:0402-RES")
      (fields (field (name "PARTNO") "RC0402FR-07220RL"))
      (libsource (lib "eagle-import") (part "RESISTOR0402-RES"))
    )
    (comp (ref "R708")
      (value "220R")
      (footprint "eagle-import:0402-RES")
      (fields (field (name "PARTNO") "RC0402FR-07220RL"))
      (libsource (lib "eagle-import") (part "RESISTOR0402-RES"))
    )
    (comp (ref "R709")
      (value "220R")
      (footprint "eagle-import:0402-RES")
      (fields (field (name "PARTNO") "RC0402FR-07220RL"))
      (libsource (lib "eagle-import") (part "RESISTOR0402-RES"))
    )
    (comp (ref "R710")
      (value "220R")
      (footprint "eagle-import:0402-RES")
      (fields (field (name "PARTNO") "RC0402FR-07220RL"))
      (libsource (lib "eagle-import") (part "RESISTOR0402-RES"))
    )
    (comp (ref "R711")
      (value "220R")
      (footprint "eagle-import:0402-RES")
      (fields (field (name "PARTNO") "RC0402FR-07220RL"))
      (libsource (lib "eagle-import") (part "RESISTOR0402-RES"))
    )
    (comp (ref "R712")
      (value "220R")
      (footprint "eagle-import:0402-RES")
      (fields (field (name "PARTNO") "RC0402FR-07220RL"))
      (libsource (lib "eagle-import") (part "RESISTOR0402-RES"))
    )
    (comp (ref "R713")
      (value "220R")
      (footprint "eagle-import:0402-RES")
      (fields (field (name "PARTNO") "RC0402FR-07220RL"))
      (libsource (lib "eagle-import") (part "RESISTOR0402-RES"))
    )
    (comp (ref "R714")
      (value "220R")
      (footprint "eagle-import:0402-RES")
      (fields (field (name "PARTNO") "RC0402FR-07220RL"))
      (libsource (lib "eagle-import") (part "RESISTOR0402-RES"))
    )
    (comp (ref "R716")
      (value "10K/0.1%")
      (footprint "eagle-import:0402-RES")
      (fields (field (name "PARTNO") "ERA-2AEB103X"))
      (libsource (lib "eagle-import") (part "RESISTOR0402-RES"))
    )
    (comp (ref "R718")
      (value "10K")
      (footprint "eagle-import:0402-RES")
      (fields (field (name "PARTNO") "ERA-2AEB103X"))
      (libsource (lib "eagle-import") (part "RESISTOR0402-RES"))
    )
    (comp (ref "R719")
      (value "10K")
      (footprint "eagle-import:0402-RES")
      (fields (field (name "PARTNO") "ERA-2AEB103X"))
      (libsource (lib "eagle-import") (part "RESISTOR0402-RES"))
    )
    (comp (ref "U$13")
      (value "CREATIVE_COMMONS")
      (footprint "eagle-import:CREATIVE_COMMONS")
      (libsource (lib "eagle-import") (part "CREATIVE_COMMONS"))
    )
    (comp (ref "U701")
      (value "TXS0108QFN20")
      (footprint "eagle-import:QFN20-RGY")
      (fields (field (name "PARTNO") "TXS0108ERGYR"))
      (libsource (lib "eagle-import") (part "TXS0108QFN20"))
    )
    (comp (ref "U702")
      (value "TXS0108QFN20")
      (footprint "eagle-import:QFN20-RGY")
      (fields (field (name "PARTNO") "TXS0108ERGYR"))
      (libsource (lib "eagle-import") (part "TXS0108QFN20"))
    )
    (comp (ref "U703")
      (value "74LVC2G240")
      (footprint "eagle-import:TSSOP8_SOT505-2")
      (fields (field (name "PARTNO") "74LVC2G240DP,125"))
      (libsource (lib "eagle-import") (part "74LVC2G240-TSSOP-8"))
    )
    (comp (ref "U704")
      (value "BBB_3X14_RA")
      (footprint "eagle-import:3X14RA")
      (fields (field (name "PARTNO") "07579"))
      (libsource (lib "eagle-import") (part "BBB_3X14_RA"))
    )
    (comp (ref "C201")
      (value "0u1")
      (footprint "eagle-import:0402-CAP")
      (fields (field (name "PARTNO") "CC0402ZRY5V7BB104"))
      (libsource (lib "eagle-import") (part "CAP0402"))
    )
    (comp (ref "C202")
      (value "0u1")
      (footprint "eagle-import:0402-CAP")
      (fields (field (name "PARTNO") "CC0402ZRY5V7BB104"))
      (libsource (lib "eagle-import") (part "CAP0402"))
    )
    (comp (ref "D201")
      (value "PESD0402-140")
      (footprint "eagle-import:0402-TVS")
      (libsource (lib "eagle-import") (part "DIODE-TVS"))
    )
    (comp (ref "D202")
      (value "PESD0402-140")
      (footprint "eagle-import:0402-TVS")
      (libsource (lib "eagle-import") (part "DIODE-TVS"))
    )
    (comp (ref "D203")
      (value "PESD0402-140")
      (footprint "eagle-import:0402-TVS")
      (libsource (lib "eagle-import") (part "DIODE-TVS"))
    )
    (comp (ref "L201")
      (value "KNH16C104DA5TS")
      (footprint "eagle-import:KYOCERA-KNH16-DA")
      (libsource (lib "eagle-import") (part "KNH16C104DA5TS"))
    )
    (comp (ref "L202")
      (value "KNH16C104DA5TS")
      (footprint "eagle-import:KYOCERA-KNH16-DA")
      (libsource (lib "eagle-import") (part "KNH16C104DA5TS"))
    )
    (comp (ref "L203")
      (value "KNH16C104DA5TS")
      (footprint "eagle-import:KYOCERA-KNH16-DA")
      (libsource (lib "eagle-import") (part "KNH16C104DA5TS"))
    )
    (comp (ref "R201")
      (value "120R")
      (footprint "eagle-import:0402-RES")
      (fields (field (name "PARTNO") "RC0402FR-07120RL"))
      (libsource (lib "eagle-import") (part "RESISTOR0402-RES"))
    )
    (comp (ref "R202")
      (value "120R")
      (footprint "eagle-import:0402-RES")
      (fields (field (name "PARTNO") "RC0402FR-07120RL"))
      (libsource (lib "eagle-import") (part "RESISTOR0402-RES"))
    )
    (comp (ref "R203")
      (value "120R")
      (footprint "eagle-import:0402-RES")
      (fields (field (name "PARTNO") "RC0402FR-07120RL"))
      (libsource (lib "eagle-import") (part "RESISTOR0402-RES"))
    )
    (comp (ref "R204")
      (value "120R")
      (footprint "eagle-import:0402-RES")
      (fields (field (name "PARTNO") "RC0402FR-07120RL"))
      (libsource (lib "eagle-import") (part "RESISTOR0402-RES"))
    )
    (comp (ref "R205")
      (value "120R")
      (footprint "eagle-import:0402-RES")
      (fields (field (name "PARTNO") "RC0402FR-07120RL"))
      (libsource (lib "eagle-import") (part "RESISTOR0402-RES"))
    )
    (comp (ref "R206")
      (value "120R")
      (footprint "eagle-import:0402-RES")
      (fields (field (name "PARTNO") "RC0402FR-07120RL"))
      (libsource (lib "eagle-import") (part "RESISTOR0402-RES"))
    )
    (comp (ref "R207")
      (value "120R")
      (footprint "eagle-import:0402-RES")
      (fields (field (name "PARTNO") "RC0402FR-07120RL"))
      (libsource (lib "eagle-import") (part "RESISTOR0402-RES"))
    )
    (comp (ref "R208")
      (value "120R")
      (footprint "eagle-import:0402-RES")
      (fields (field (name "PARTNO") "RC0402FR-07120RL"))
      (libsource (lib "eagle-import") (part "RESISTOR0402-RES"))
    )
    (comp (ref "R209")
      (value "120R")
      (footprint "eagle-import:0402-RES")
      (fields (field (name "PARTNO") "RC0402FR-07120RL"))
      (libsource (lib "eagle-import") (part "RESISTOR0402-RES"))
    )
    (comp (ref "R210")
      (value "120R")
      (footprint "eagle-import:0402-RES")
      (fields (field (name "PARTNO") "RC0402FR-07120RL"))
      (libsource (lib "eagle-import") (part "RESISTOR0402-RES"))
    )
    (comp (ref "R211")
      (value "120R")
      (footprint "eagle-import:0402-RES")
      (fields (field (name "PARTNO") "RC0402FR-07120RL"))
      (libsource (lib "eagle-import") (part "RESISTOR0402-RES"))
    )
    (comp (ref "R212")
      (value "120R")
      (footprint "eagle-import:0402-RES")
      (fields (field (name "PARTNO") "RC0402FR-07120RL"))
      (libsource (lib "eagle-import") (part "RESISTOR0402-RES"))
    )
    (comp (ref "R213")
      (value "120R")
      (footprint "eagle-import:0402-RES")
      (fields (field (name "PARTNO") "RC0402FR-07120RL"))
      (libsource (lib "eagle-import") (part "RESISTOR0402-RES"))
    )
    (comp (ref "R214")
      (value "120R")
      (footprint "eagle-import:0402-RES")
      (fields (field (name "PARTNO") "RC0402FR-07120RL"))
      (libsource (lib "eagle-import") (part "RESISTOR0402-RES"))
    )
    (comp (ref "R215")
      (value "10K")
      (footprint "eagle-import:0402-RES")
      (fields (field (name "PARTNO") "ERA-2AEB103X"))
      (libsource (lib "eagle-import") (part "RESISTOR0402-RES"))
    )
    (comp (ref "R216")
      (value "10K")
      (footprint "eagle-import:0402-RES")
      (fields (field (name "PARTNO") "ERA-2AEB103X"))
      (libsource (lib "eagle-import") (part "RESISTOR0402-RES"))
    )
    (comp (ref "U$2")
      (value "DF13-6P-1.25V")
      (footprint "eagle-import:DF13C-6P-1.25V")
      (fields (field (name "PARTNO") "DF13C-6P-1.25V(20)"))
      (libsource (lib "eagle-import") (part "pxf_DF13-6P-1.25V"))
    )
    (comp (ref "U$3")
      (value "DF13-6P-1.25V")
      (footprint "eagle-import:DF13C-6P-1.25V")
      (fields (field (name "PARTNO") "DF13C-6P-1.25V(20)"))
      (libsource (lib "eagle-import") (part "pxf_DF13-6P-1.25V"))
    )
    (comp (ref "U$4")
      (value "DF13-6P-1.25V")
      (footprint "eagle-import:DF13C-6P-1.25V")
      (fields (field (name "PARTNO") "DF13C-6P-1.25V(20)"))
      (libsource (lib "eagle-import") (part "pxf_DF13-6P-1.25V"))
    )
    (comp (ref "U$5")
      (value "CREATIVE_COMMONS")
      (footprint "eagle-import:CREATIVE_COMMONS")
      (libsource (lib "eagle-import") (part "CREATIVE_COMMONS"))
    )
    (comp (ref "U$201")
      (value "DF13-6P-1.25V")
      (footprint "eagle-import:DF13C-6P-1.25V")
      (fields (field (name "PARTNO") "DF13C-6P-1.25V(20)"))
      (libsource (lib "eagle-import") (part "pxf_DF13-6P-1.25V"))
    )
    (comp (ref "U201")
      (value "TXS0108QFN20")
      (footprint "eagle-import:QFN20-RGY")
      (fields (field (name "PARTNO") "TXS0108ERGYR"))
      (libsource (lib "eagle-import") (part "TXS0108QFN20"))
    )
    (comp (ref "U202")
      (value "TXS0108QFN20")
      (footprint "eagle-import:QFN20-RGY")
      (fields (field (name "PARTNO") "TXS0108ERGYR"))
      (libsource (lib "eagle-import") (part "TXS0108QFN20"))
    )
    (comp (ref "C501")
      (value "0u1")
      (footprint "eagle-import:0402-CAP")
      (fields (field (name "PARTNO") "CC0402ZRY5V7BB104"))
      (libsource (lib "eagle-import") (part "CAP0402"))
    )
    (comp (ref "C502")
      (value "10u")
      (footprint "eagle-import:0805-CAP")
      (fields (field (name "PARTNO") "C1608X7S0J106M080AC"))
      (libsource (lib "eagle-import") (part "CAP0805"))
    )
    (comp (ref "C503")
      (value "2u2")
      (footprint "eagle-import:0603-CAP")
      (fields (field (name "PARTNO") "C1608X6S1C225K080AC"))
      (libsource (lib "eagle-import") (part "CAP0603"))
    )
    (comp (ref "C504")
      (value "100u")
      (footprint "eagle-import:1206-CAP")
      (fields (field (name "PARTNO") "C3216X5R1A107M160AC"))
      (libsource (lib "eagle-import") (part "CAP1206"))
    )
    (comp (ref "C505")
      (value "1u")
      (footprint "eagle-import:0603-CAP")
      (fields (field (name "PARTNO") "CC0603ZRY5V7BB105"))
      (libsource (lib "eagle-import") (part "CAP0603"))
    )
    (comp (ref "C506")
      (value "0u1")
      (footprint "eagle-import:0402-CAP")
      (fields (field (name "PARTNO") "CC0402ZRY5V7BB104"))
      (libsource (lib "eagle-import") (part "CAP0402"))
    )
    (comp (ref "C507")
      (value "22u")
      (footprint "eagle-import:0805-CAP")
      (fields (field (name "PARTNO") "CC0805MKX5R5BB226"))
      (libsource (lib "eagle-import") (part "CAP0805"))
    )
    (comp (ref "C508")
      (value "0u1")
      (footprint "eagle-import:0402-CAP")
      (fields (field (name "PARTNO") "CC0402ZRY5V7BB104"))
      (libsource (lib "eagle-import") (part "CAP0402"))
    )
    (comp (ref "C509")
      (value "22u")
      (footprint "eagle-import:0805-CAP")
      (fields (field (name "PARTNO") "CC0805MKX5R5BB226"))
      (libsource (lib "eagle-import") (part "CAP0805"))
    )
    (comp (ref "C510")
      (value "100u")
      (footprint "eagle-import:1206-CAP")
      (fields (field (name "PARTNO") "C3216X5R1A107M160AC"))
      (libsource (lib "eagle-import") (part "CAP1206"))
    )
    (comp (ref "L501")
      (value "KNH16C104DA5TS")
      (footprint "eagle-import:KYOCERA-KNH16-DA")
      (libsource (lib "eagle-import") (part "KNH16C104DA5TS"))
    )
    (comp (ref "Q501")
      (value "MMBT3906LT1SMD")
      (footprint "eagle-import:SOT23-BEC")
      (fields (field (name "PARTNO") "MMBT3906LT1G"))
      (libsource (lib "eagle-import") (part "MMBT3906SMDLT1"))
    )
    (comp (ref "R4")
      (value "10K/0.1%")
      (footprint "eagle-import:0402-RES")
      (fields (field (name "PARTNO") "ERA-2AEB103X"))
      (libsource (lib "eagle-import") (part "RESISTOR0402-RES"))
    )
    (comp (ref "R501")
      (value "16K5")
      (footprint "eagle-import:0402-RES")
      (fields (field (name "PARTNO") "RMCF0402FT16K5"))
      (libsource (lib "eagle-import") (part "RESISTOR0402-RES"))
    )
    (comp (ref "R502")
      (value "1M")
      (footprint "eagle-import:0402-RES")
      (fields (field (name "PARTNO") "MCR01MRTF1004"))
      (libsource (lib "eagle-import") (part "RESISTOR0402-RES"))
    )
    (comp (ref "R503")
      (value "1k8")
      (footprint "eagle-import:0402-RES")
      (fields (field (name "PARTNO") "RC0402FR-071K8L"))
      (libsource (lib "eagle-import") (part "RESISTOR0402-RES"))
    )
    (comp (ref "R504")
      (value "25K")
      (footprint "eagle-import:0402-RES")
      (fields (field (name "PARTNO") "RMCF0402FT25K5"))
      (libsource (lib "eagle-import") (part "RESISTOR0402-RES"))
    )
    (comp (ref "R505")
      (value "10R")
      (footprint "eagle-import:0603-RES")
      (fields (field (name "PARTNO") "RC0402FR-0710RL"))
      (libsource (lib "eagle-import") (part "RESISTOR0603-RES"))
    )
    (comp (ref "R506")
      (value "10K")
      (footprint "eagle-import:0402-RES")
      (fields (field (name "PARTNO") "ERA-2AEB103X"))
      (libsource (lib "eagle-import") (part "RESISTOR0402-RES"))
    )
    (comp (ref "R507")
      (value "1M")
      (footprint "eagle-import:0402-RES")
      (fields (field (name "PARTNO") "MCR01MRTF1004"))
      (libsource (lib "eagle-import") (part "RESISTOR0402-RES"))
    )
    (comp (ref "R508")
      (value "10K/0.1%")
      (footprint "eagle-import:0402-RES")
      (fields (field (name "PARTNO") "ERA-2AEB103X"))
      (libsource (lib "eagle-import") (part "RESISTOR0402-RES"))
    )
    (comp (ref "R509")
      (value "10K/0.1%")
      (footprint "eagle-import:0402-RES")
      (fields (field (name "PARTNO") "ERA-2AEB103X"))
      (libsource (lib "eagle-import") (part "RESISTOR0402-RES"))
    )
    (comp (ref "U$9")
      (value "CREATIVE_COMMONS")
      (footprint "eagle-import:CREATIVE_COMMONS")
      (libsource (lib "eagle-import") (part "CREATIVE_COMMONS"))
    )
    (comp (ref "U501")
      (value "BQ24315")
      (footprint "eagle-import:QFN8-DSG")
      (fields (field (name "PARTNO") "BQ24315DSGR"))
      (libsource (lib "eagle-import") (part "BQ24315"))
    )
    (comp (ref "U502")
      (value "MIC5332")
      (footprint "eagle-import:MLF-8-EPAD")
      (fields (field (name "PARTNO") "MIC5332-SSYMT"))
      (libsource (lib "eagle-import") (part "MIC5332"))
    )
    (comp (ref "U503")
      (value "BQ24315")
      (footprint "eagle-import:QFN8-DSG")
      (fields (field (name "PARTNO") "BQ24315DSGR"))
      (libsource (lib "eagle-import") (part "BQ24315"))
    )
    (comp (ref "C101")
      (value "0u1")
      (footprint "eagle-import:0402-CAP")
      (fields (field (name "PARTNO") "CC0402ZRY5V7BB104"))
      (libsource (lib "eagle-import") (part "CAP0402"))
    )
    (comp (ref "R102")
      (value "10M/0.1%")
      (footprint "eagle-import:0402-RES")
      (fields (field (name "PARTNO") "RC0402FR-0710ML"))
      (libsource (lib "eagle-import") (part "RESISTOR0402-RES"))
    )
    (comp (ref "R103")
      (value "4.75K/0.1%")
      (footprint "eagle-import:0402-RES")
      (fields (field (name "PARTNO") "RC0402FR-074K75L"))
      (libsource (lib "eagle-import") (part "RESISTOR0402-RES"))
    )
    (comp (ref "U$1")
      (value "PX4-LOGO")
      (footprint "eagle-import:PIXHAWK-FIRE-LOGO-30")
      (libsource (lib "eagle-import") (part "PX4-LOGO"))
    )
    (comp (ref "U$6")
      (value "CREATIVE_COMMONS")
      (footprint "eagle-import:CREATIVE_COMMONS")
      (libsource (lib "eagle-import") (part "CREATIVE_COMMONS"))
    )
    (comp (ref "U$101")
      (value "BEAGLEBONE_OUTLINE")
      (footprint "eagle-import:BEAGLEBONE_SHIELD")
      (libsource (lib "eagle-import") (part "BEAGLEBONE_OUTLINE"))
    )
    (comp (ref "U1")
      (value "EEPROM-I2CSMD")
      (footprint "eagle-import:SO08")
      (fields (field (name "PARTNO") "AT24CS32-SSHM"))
      (libsource (lib "eagle-import") (part "EEPROM-I2CSMD"))
    )
    (comp (ref "U2")
      (value "EEPROM-I2CSMD")
      (footprint "eagle-import:SO08")
      (fields (field (name "PARTNO") "ATSHA204-SH-DA-TTR-ND"))
      (libsource (lib "eagle-import") (part "EEPROM-I2CSMD"))
    )
    (comp (ref "C601")
      (value "0u1")
      (footprint "eagle-import:0402-CAP")
      (fields (field (name "PARTNO") "CC0402ZRY5V7BB104"))
      (libsource (lib "eagle-import") (part "CAP0402"))
    )
    (comp (ref "C602")
      (value "1u0")
      (footprint "eagle-import:0603-CAP")
      (fields (field (name "PARTNO") "CC0603ZRY5V7BB105"))
      (libsource (lib "eagle-import") (part "CAP0603"))
    )
    (comp (ref "C603")
      (value "5n6")
      (footprint "eagle-import:0402-CAP")
      (fields (field (name "PARTNO") "CC0402KRX7R7BB562"))
      (libsource (lib "eagle-import") (part "CAP0402"))
    )
    (comp (ref "C604")
      (value "0u47")
      (footprint "eagle-import:0402-CAP")
      (fields (field (name "PARTNO") "C1005X5R1C474K050BC"))
      (libsource (lib "eagle-import") (part "CAP0402"))
    )
    (comp (ref "D601")
      (value "PESD0402-140")
      (footprint "eagle-import:0402-TVS")
      (libsource (lib "eagle-import") (part "DIODE-TVS"))
    )
    (comp (ref "JP600")
      (value "JP1Q")
      (footprint "eagle-import:JP1")
      (fields (field (name "PARTNO") "1-87215-0"))
      (libsource (lib "eagle-import") (part "JP1Q"))
    )
    (comp (ref "L601")
      (value "47uH")
      (footprint "eagle-import:0805-IND")
      (fields (field (name "PARTNO") "MLZ2012M470W"))
      (libsource (lib "eagle-import") (part "INDUCTOR0805"))
    )
    (comp (ref "LED601")
      (value "GREEN")
      (footprint "eagle-import:0603-LED")
      (fields (field (name "PARTNO") "APTD1608CGCK"))
      (libsource (lib "eagle-import") (part "LED0603"))
    )
    (comp (ref "LED602")
      (value "AMBER")
      (footprint "eagle-import:0603-LED")
      (fields (field (name "PARTNO") "APTD1608SECK"))
      (libsource (lib "eagle-import") (part "LED0603"))
    )
    (comp (ref "LED603")
      (value "BLUE")
      (footprint "eagle-import:0603-LED")
      (fields (field (name "PARTNO") "APTD1608QBC/D"))
      (libsource (lib "eagle-import") (part "LED0603"))
    )
    (comp (ref "R601")
      (value "220R")
      (footprint "eagle-import:0402-RES")
      (fields (field (name "PARTNO") "RC0402FR-07220RL"))
      (libsource (lib "eagle-import") (part "RESISTOR0402-RES"))
    )
    (comp (ref "R602")
      (value "9K09")
      (footprint "eagle-import:0402-RES")
      (fields (field (name "PARTNO") "RMCF0402FT9K09"))
      (libsource (lib "eagle-import") (part "RESISTOR0402-RES"))
    )
    (comp (ref "R603")
      (value "10K")
      (footprint "eagle-import:0402-RES")
      (fields (field (name "PARTNO") "ERA-2AEB103X"))
      (libsource (lib "eagle-import") (part "RESISTOR0402-RES"))
    )
    (comp (ref "R604")
      (value "100K")
      (footprint "eagle-import:0402-RES")
      (fields (field (name "PARTNO") "RC0402FR-07100KL"))
      (libsource (lib "eagle-import") (part "RESISTOR0402-RES"))
    )
    (comp (ref "R605")
      (value "10K")
      (footprint "eagle-import:0402-RES")
      (fields (field (name "PARTNO") "ERA-2AEB103X"))
      (libsource (lib "eagle-import") (part "RESISTOR0402-RES"))
    )
    (comp (ref "R606")
      (value "453K")
      (footprint "eagle-import:0402-RES")
      (fields (field (name "PARTNO") "RMCF0402FT453K"))
      (libsource (lib "eagle-import") (part "RESISTOR0402-RES"))
    )
    (comp (ref "R607")
      (value "16K5")
      (footprint "eagle-import:0402-RES")
      (fields (field (name "PARTNO") "RMCF0402FT16K5"))
      (libsource (lib "eagle-import") (part "RESISTOR0402-RES"))
    )
    (comp (ref "R608")
      (value "220R")
      (footprint "eagle-import:0402-RES")
      (fields (field (name "PARTNO") "RC0402FR-07220RL"))
      (libsource (lib "eagle-import") (part "RESISTOR0402-RES"))
    )
    (comp (ref "R609")
      (value "220R")
      (footprint "eagle-import:0402-RES")
      (fields (field (name "PARTNO") "RC0402FR-07220RL"))
      (libsource (lib "eagle-import") (part "RESISTOR0402-RES"))
    )
    (comp (ref "R610")
      (value "220R")
      (footprint "eagle-import:0402-RES")
      (fields (field (name "PARTNO") "RC0402FR-07220RL"))
      (libsource (lib "eagle-import") (part "RESISTOR0402-RES"))
    )
    (comp (ref "R611")
      (value "68R")
      (footprint "eagle-import:0402-RES")
      (fields (field (name "PARTNO") "RC0402FR-0768RL"))
      (libsource (lib "eagle-import") (part "RESISTOR0402-RES"))
    )
    (comp (ref "R612")
      (value "220R")
      (footprint "eagle-import:0402-RES")
      (fields (field (name "PARTNO") "RC0402FR-07220RL"))
      (libsource (lib "eagle-import") (part "RESISTOR0402-RES"))
    )
    (comp (ref "R613")
      (value "1K5")
      (footprint "eagle-import:0402-RES")
      (fields (field (name "PARTNO") "RC0402FR-071K5L"))
      (libsource (lib "eagle-import") (part "RESISTOR0402-RES"))
    )
    (comp (ref "R614")
      (value "100K")
      (footprint "eagle-import:0402-RES")
      (fields (field (name "PARTNO") "RC0402FR-07100KL"))
      (libsource (lib "eagle-import") (part "RESISTOR0402-RES"))
    )
    (comp (ref "U$10")
      (value "CREATIVE_COMMONS")
      (footprint "eagle-import:CREATIVE_COMMONS")
      (libsource (lib "eagle-import") (part "CREATIVE_COMMONS"))
    )
    (comp (ref "U$11")
      (value "DF13-2P-1.25")
      (footprint "eagle-import:DF13C-2P-1.25V")
      (fields (field (name "PARTNO") "DF13C-2P-1.25V(20)"))
      (libsource (lib "eagle-import") (part "DF13-2P-1.25"))
    )
    (comp (ref "U$12")
      (value "DF13-3P-1.25V")
      (footprint "eagle-import:DF13C-3P-1.25V")
      (fields (field (name "PARTNO") "DF13C-3P-1.25V(20)"))
      (libsource (lib "eagle-import") (part "DF13-3P-1.25V"))
    )
    (comp (ref "U601")
      (value "TCA62724FMG")
      (footprint "eagle-import:SON10")
      (libsource (lib "eagle-import") (part "TCA62724FMG"))
    )
    (comp (ref "U602")
      (value "LT3469")
      (footprint "eagle-import:SOT23-8")
      (fields (field (name "PARTNO") "LT3469ETS8"))
      (libsource (lib "eagle-import") (part "LT3469"))
    )
    (comp (ref "U603")
      (value "LRTB GFTG-T7AW-1+V7A7-29+R5T9-49-L")
      (footprint "eagle-import:6-PLCC")
      (fields (field (name "PARTNO") "LRTB GFTG-T7AW-1+V7A7-29+R5T9-49-L"))
      (libsource (lib "eagle-import") (part "RGB-LED6-PLCC"))
    )
    (comp (ref "C301")
      (value "0u1")
      (footprint "eagle-import:0402-CAP")
      (fields (field (name "PARTNO") "CC0402ZRY5V7BB104"))
      (libsource (lib "eagle-import") (part "CAP0402"))
    )
    (comp (ref "C302")
      (value "0u1")
      (footprint "eagle-import:0402-CAP")
      (fields (field (name "PARTNO") "CC0402ZRY5V7BB104"))
      (libsource (lib "eagle-import") (part "CAP0402"))
    )
    (comp (ref "C303")
      (value "10u/10V")
      (footprint "eagle-import:0805-CAP")
      (fields (field (name "PARTNO") "CC0805ZKY5V6BB106"))
      (libsource (lib "eagle-import") (part "CAP0805"))
    )
    (comp (ref "C304")
      (value "0u1")
      (footprint "eagle-import:0402-CAP")
      (fields (field (name "PARTNO") "CC0402ZRY5V7BB104"))
      (libsource (lib "eagle-import") (part "CAP0402"))
    )
    (comp (ref "C305")
      (value "0u1")
      (footprint "eagle-import:0402-CAP")
      (fields (field (name "PARTNO") "CC0402ZRY5V7BB104"))
      (libsource (lib "eagle-import") (part "CAP0402"))
    )
    (comp (ref "D301")
      (value "PESD0402-140")
      (footprint "eagle-import:0402-TVS")
      (libsource (lib "eagle-import") (part "DIODE-TVS"))
    )
    (comp (ref "D302")
      (value "PESD0402-140")
      (footprint "eagle-import:0402-TVS")
      (libsource (lib "eagle-import") (part "DIODE-TVS"))
    )
    (comp (ref "D303")
      (value "PESD0402-140")
      (footprint "eagle-import:0402-TVS")
      (libsource (lib "eagle-import") (part "DIODE-TVS"))
    )
    (comp (ref "J305")
      (value "DF13-3P-1.25V")
      (footprint "eagle-import:DF13C-3P-1.25V")
      (fields (field (name "PARTNO") "DF13C-3P-1.25V(20)"))
      (libsource (lib "eagle-import") (part "DF13-3P-1.25V"))
    )
    (comp (ref "J306")
      (value "DF13-4P-1.25V")
      (footprint "eagle-import:DF13C-4P-1.25V")
      (fields (field (name "PARTNO") "DF13C-4P-1.25V(20)"))
      (libsource (lib "eagle-import") (part "DF13-4P-1.25V"))
    )
    (comp (ref "J307")
      (value "DF13-4P-1.25V")
      (footprint "eagle-import:DF13C-4P-1.25V")
      (fields (field (name "PARTNO") "DF13C-4P-1.25V(20)"))
      (libsource (lib "eagle-import") (part "DF13-4P-1.25V"))
    )
    (comp (ref "J308")
      (value "DF13-4P-1.25V")
      (footprint "eagle-import:DF13C-4P-1.25V")
      (fields (field (name "PARTNO") "DF13C-4P-1.25V(20)"))
      (libsource (lib "eagle-import") (part "DF13-4P-1.25V"))
    )
    (comp (ref "J309")
      (value "DF13-5P-1.25V")
      (footprint "eagle-import:DF13C-5P-1.25V")
      (fields (field (name "PARTNO") "DF13C-5P-1.25V(20)"))
      (libsource (lib "eagle-import") (part "DF13-5P-1.25V"))
    )
    (comp (ref "J310")
      (value "DF13-4P-1.25V")
      (footprint "eagle-import:DF13C-4P-1.25V")
      (fields (field (name "PARTNO") "DF13C-4P-1.25V(20)"))
      (libsource (lib "eagle-import") (part "DF13-4P-1.25V"))
    )
    (comp (ref "J314")
      (value "DF13-4P-1.25V")
      (footprint "eagle-import:DF13C-4P-1.25V")
      (fields (field (name "PARTNO") "DF13C-4P-1.25V(20)"))
      (libsource (lib "eagle-import") (part "DF13-4P-1.25V"))
    )
    (comp (ref "L301")
      (value "KNH16C104DA5TS")
      (footprint "eagle-import:KYOCERA-KNH16-DA")
      (libsource (lib "eagle-import") (part "KNH16C104DA5TS"))
    )
    (comp (ref "L302")
      (value "KNH16C104DA5TS")
      (footprint "eagle-import:KYOCERA-KNH16-DA")
      (libsource (lib "eagle-import") (part "KNH16C104DA5TS"))
    )
    (comp (ref "L303")
      (value "KNH16C104DA5TS")
      (footprint "eagle-import:KYOCERA-KNH16-DA")
      (libsource (lib "eagle-import") (part "KNH16C104DA5TS"))
    )
    (comp (ref "R5")
      (value "10K/0.1%")
      (footprint "eagle-import:0402-RES")
      (fields (field (name "PARTNO") "ERA-2AEB103X"))
      (libsource (lib "eagle-import") (part "RESISTOR0402-RES"))
    )
    (comp (ref "R6")
      (value "10K/0.1%")
      (footprint "eagle-import:0402-RES")
      (fields (field (name "PARTNO") "ERA-2AEB103X"))
      (libsource (lib "eagle-import") (part "RESISTOR0402-RES"))
    )
    (comp (ref "R7")
      (value "10K/0.1%")
      (footprint "eagle-import:0402-RES")
      (fields (field (name "PARTNO") "ERA-2AEB103X"))
      (libsource (lib "eagle-import") (part "RESISTOR0402-RES"))
    )
    (comp (ref "R301")
      (value "1K5")
      (footprint "eagle-import:0402-RES")
      (fields (field (name "PARTNO") "RC0402FR-071K5L"))
      (libsource (lib "eagle-import") (part "RESISTOR0402-RES"))
    )
    (comp (ref "R302")
      (value "1K5")
      (footprint "eagle-import:0402-RES")
      (fields (field (name "PARTNO") "RC0402FR-071K5L"))
      (libsource (lib "eagle-import") (part "RESISTOR0402-RES"))
    )
    (comp (ref "R303")
      (value "10K/0.1%")
      (footprint "eagle-import:0402-RES")
      (fields (field (name "PARTNO") "ERA-2AEB103X"))
      (libsource (lib "eagle-import") (part "RESISTOR0402-RES"))
    )
    (comp (ref "R304")
      (value "1K5")
      (footprint "eagle-import:0402-RES")
      (fields (field (name "PARTNO") "RC0402FR-071K5L"))
      (libsource (lib "eagle-import") (part "RESISTOR0402-RES"))
    )
    (comp (ref "R305")
      (value "1K5")
      (footprint "eagle-import:0402-RES")
      (fields (field (name "PARTNO") "RC0402FR-071K5L"))
      (libsource (lib "eagle-import") (part "RESISTOR0402-RES"))
    )
    (comp (ref "R306")
      (value "10K/0.1%")
      (footprint "eagle-import:0402-RES")
      (fields (field (name "PARTNO") "ERA-2AEB103X"))
      (libsource (lib "eagle-import") (part "RESISTOR0402-RES"))
    )
    (comp (ref "R307")
      (value "10K/0.1%")
      (footprint "eagle-import:0402-RES")
      (fields (field (name "PARTNO") "ERA-2AEB103X"))
      (libsource (lib "eagle-import") (part "RESISTOR0402-RES"))
    )
    (comp (ref "R308")
      (value "10K/0.1%")
      (footprint "eagle-import:0402-RES")
      (fields (field (name "PARTNO") "ERA-2AEB103X"))
      (libsource (lib "eagle-import") (part "RESISTOR0402-RES"))
    )
    (comp (ref "R309")
      (value "120R")
      (footprint "eagle-import:0402-RES")
      (fields (field (name "PARTNO") "RC0402FR-07120RL"))
      (libsource (lib "eagle-import") (part "RESISTOR0402-RES"))
    )
    (comp (ref "R310")
      (value "10K/0.1%")
      (footprint "eagle-import:0402-RES")
      (fields (field (name "PARTNO") "ERA-2AEB103X"))
      (libsource (lib "eagle-import") (part "RESISTOR0402-RES"))
    )
    (comp (ref "R311")
      (value "10K/0.1%")
      (footprint "eagle-import:0402-RES")
      (fields (field (name "PARTNO") "ERA-2AEB103X"))
      (libsource (lib "eagle-import") (part "RESISTOR0402-RES"))
    )
    (comp (ref "R312")
      (value "220R")
      (footprint "eagle-import:0402-RES")
      (fields (field (name "PARTNO") "RC0402FR-07220RL"))
      (libsource (lib "eagle-import") (part "RESISTOR0402-RES"))
    )
    (comp (ref "R313")
      (value "220R")
      (footprint "eagle-import:0402-RES")
      (fields (field (name "PARTNO") "RC0402FR-07220RL"))
      (libsource (lib "eagle-import") (part "RESISTOR0402-RES"))
    )
    (comp (ref "R314")
      (value "10K")
      (footprint "eagle-import:0402-RES")
      (fields (field (name "PARTNO") "ERA-2AEB103X"))
      (libsource (lib "eagle-import") (part "RESISTOR0402-RES"))
    )
    (comp (ref "R315")
      (value "0R")
      (footprint "eagle-import:0402-RES")
      (fields (field (name "PARTNO") "RC0402FR-070RL"))
      (libsource (lib "eagle-import") (part "RESISTOR0402-RES"))
    )
    (comp (ref "U$7")
      (value "CREATIVE_COMMONS")
      (footprint "eagle-import:CREATIVE_COMMONS")
      (libsource (lib "eagle-import") (part "CREATIVE_COMMONS"))
    )
    (comp (ref "U102")
      (value "FM25V01")
      (footprint "eagle-import:SO08")
      (fields (field (name "PARTNO") "FM25V01-G"))
      (libsource (lib "eagle-import") (part "FM25V01"))
    )
    (comp (ref "U301")
      (value "MAX3051")
      (footprint "eagle-import:SOT23-8")
      (fields (field (name "PARTNO") "MAX3051EKA"))
      (libsource (lib "eagle-import") (part "MAX3051MAX3051EKA"))
    )
    (comp (ref "U302")
      (value "TXS0108QFN20")
      (footprint "eagle-import:QFN20-RGY")
      (fields (field (name "PARTNO") "TXS0108ERGYR"))
      (libsource (lib "eagle-import") (part "TXS0108QFN20"))
    )
    (comp (ref "U303")
      (value "PCA9306")
      (footprint "eagle-import:PCA9306")
      (fields (field (name "PARTNO") "PCA9306DQER"))
      (libsource (lib "eagle-import") (part "PCA9306"))
    )
  )
  (nets
    (net (code "1") (name "3V3_EN") (class "Default")
      (node (ref "R102") (pin "P$2") (pinfunction "2_P$2") (pintype "passive"))
      (node (ref "R503") (pin "P$2") (pinfunction "2_P$2") (pintype "passive"))
      (node (ref "U$101") (pin "56") (pinfunction "SYS_RESETN_10_56") (pintype "passive"))
      (node (ref "U$101") (pin "73") (pinfunction "27_PRU1_R30/31[5]_73") (pintype "passive"))
      (node (ref "U502") (pin "4") (pinfunction "EN2_4") (pintype "bidirectional"))
      (node (ref "U502") (pin "5") (pinfunction "EN1_5") (pintype "bidirectional"))
    )
    (net (code "2") (name "3_VDD_3V3") (class "Default")
      (node (ref "U$101") (pin "49") (pinfunction "3_VDD_3V3_49") (pintype "power_in"))
    )
    (net (code "3") (name "ACCEL_DRDY") (class "Default")
      (node (ref "U$101") (pin "8") (pinfunction "GPIO2[3]_8_8") (pintype "passive"))
      (node (ref "U406") (pin "14") (pinfunction "INT2_XM_14") (pintype "bidirectional"))
    )
    (net (code "4") (name "ALARM") (class "Default")
      (node (ref "R602") (pin "P$2") (pinfunction "2_P$2") (pintype "passive"))
      (node (ref "U$101") (pin "36") (pinfunction "GPIO2[16]_36_36") (pintype "passive"))
    )
    (net (code "5") (name "AUX_ADC1") (class "Default")
      (node (ref "R308") (pin "P$1") (pinfunction "1_P$1") (pintype "passive"))
      (node (ref "U$101") (pin "83") (pinfunction "37_AIN2_83") (pintype "passive"))
    )
    (net (code "6") (name "AUX_ADC2") (class "Default")
      (node (ref "R307") (pin "P$1") (pinfunction "1_P$1") (pintype "passive"))
      (node (ref "U$101") (pin "84") (pinfunction "AIN3_38_84") (pintype "passive"))
    )
    (net (code "7") (name "BACKUP_LIPO_+_1S") (class "Default")
      (node (ref "U$101") (pin "TP5") (pinfunction "BAT_+_LIPO_1_S_TP5") (pintype "bidirectional"))
      (node (ref "X801") (pin "1") (pinfunction "S_1") (pintype "passive"))
    )
    (net (code "8") (name "BATT_CURRENT_SENS") (class "Default")
      (node (ref "R1") (pin "P$1") (pinfunction "1_P$1") (pintype "passive"))
      (node (ref "R808") (pin "P$1") (pinfunction "1_P$1") (pintype "passive"))
      (node (ref "U$101") (pin "81") (pinfunction "35_AIN6_81") (pintype "passive"))
    )
    (net (code "9") (name "BATT_SENSE") (class "Default")
      (node (ref "U$101") (pin "TP6") (pinfunction "BAT_SENSE_TP6") (pintype "bidirectional"))
      (node (ref "X801") (pin "2") (pinfunction "S_2") (pintype "passive"))
    )
    (net (code "10") (name "BATT_TEMP_SENSE") (class "Default")
      (node (ref "U$101") (pin "TP7") (pinfunction "TEMP_SENSE_TP7") (pintype "bidirectional"))
      (node (ref "X801") (pin "3") (pinfunction "S_3") (pintype "passive"))
    )
    (net (code "11") (name "BATT_VOLTAGE_SENS") (class "Default")
      (node (ref "R2") (pin "P$1") (pinfunction "1_P$1") (pintype "passive"))
      (node (ref "R807") (pin "P$1") (pinfunction "1_P$1") (pintype "passive"))
      (node (ref "U$101") (pin "82") (pinfunction "AIN5_36_82") (pintype "passive"))
    )
    (net (code "12") (name "BBB-VDD_3V3") (class "Default")
      (node (ref "C201") (pin "P$1") (pinfunction "1_P$1") (pintype "passive"))
      (node (ref "C202") (pin "P$1") (pinfunction "1_P$1") (pintype "passive"))
      (node (ref "C302") (pin "P$1") (pinfunction "1_P$1") (pintype "passive"))
      (node (ref "C303") (pin "P$1") (pinfunction "1_P$1") (pintype "passive"))
      (node (ref "C304") (pin "P$1") (pinfunction "1_P$1") (pintype "passive"))
      (node (ref "C505") (pin "P$1") (pinfunction "1_P$1") (pintype "passive"))
      (node (ref "C506") (pin "P$1") (pinfunction "1_P$1") (pintype "passive"))
      (node (ref "C507") (pin "P$1") (pinfunction "1_P$1") (pintype "passive"))
      (node (ref "C601") (pin "P$1") (pinfunction "1_P$1") (pintype "passive"))
      (node (ref "C701") (pin "P$1") (pinfunction "1_P$1") (pintype "passive"))
      (node (ref "C702") (pin "P$1") (pinfunction "1_P$1") (pintype "passive"))
      (node (ref "C703") (pin "P$1") (pinfunction "1_P$1") (pintype "passive"))
      (node (ref "D601") (pin "C") (pinfunction "C_C") (pintype "passive"))
      (node (ref "R215") (pin "P$2") (pinfunction "2_P$2") (pintype "passive"))
      (node (ref "R216") (pin "P$2") (pinfunction "2_P$2") (pintype "passive"))
      (node (ref "R301") (pin "P$2") (pinfunction "2_P$2") (pintype "passive"))
      (node (ref "R302") (pin "P$2") (pinfunction "2_P$2") (pintype "passive"))
      (node (ref "R304") (pin "P$1") (pinfunction "1_P$1") (pintype "passive"))
      (node (ref "R305") (pin "P$1") (pinfunction "1_P$1") (pintype "passive"))
      (node (ref "R314") (pin "P$2") (pinfunction "2_P$2") (pintype "passive"))
      (node (ref "R502") (pin "P$2") (pinfunction "2_P$2") (pintype "passive"))
      (node (ref "R507") (pin "P$2") (pinfunction "2_P$2") (pintype "passive"))
      (node (ref "R601") (pin "P$2") (pinfunction "2_P$2") (pintype "passive"))
      (node (ref "R718") (pin "P$2") (pinfunction "2_P$2") (pintype "passive"))
      (node (ref "R719") (pin "P$2") (pinfunction "2_P$2") (pintype "passive"))
      (node (ref "U$12") (pin "1") (pinfunction "1_1") (pintype "passive"))
      (node (ref "U201") (pin "19") (pinfunction "VCCB_19") (pintype "input"))
      (node (ref "U201") (pin "2") (pinfunction "VCCA_2") (pintype "input"))
      (node (ref "U202") (pin "19") (pinfunction "VCCB_19") (pintype "input"))
      (node (ref "U202") (pin "2") (pinfunction "VCCA_2") (pintype "input"))
      (node (ref "U301") (pin "3") (pinfunction "VCC_3") (pintype "input"))
      (node (ref "U302") (pin "10") (pinfunction "OE_10") (pintype "input"))
      (node (ref "U302") (pin "2") (pinfunction "VCCA_2") (pintype "input"))
      (node (ref "U303") (pin "2") (pinfunction "VREF1_2") (pintype "bidirectional"))
      (node (ref "U303") (pin "7") (pinfunction "VREF2_7") (pintype "bidirectional"))
      (node (ref "U303") (pin "8") (pinfunction "EN_8") (pintype "bidirectional"))
      (node (ref "U502") (pin "7") (pinfunction "VOUT2_7") (pintype "bidirectional"))
      (node (ref "U601") (pin "1") (pinfunction "~{SHDN}_1") (pintype "input"))
      (node (ref "U601") (pin "10") (pinfunction "VIN_10") (pintype "power_in"))
      (node (ref "U701") (pin "19") (pinfunction "VCCB_19") (pintype "input"))
      (node (ref "U701") (pin "2") (pinfunction "VCCA_2") (pintype "input"))
      (node (ref "U702") (pin "19") (pinfunction "VCCB_19") (pintype "input"))
      (node (ref "U702") (pin "2") (pinfunction "VCCA_2") (pintype "input"))
      (node (ref "U703") (pin "8") (pinfunction "VCC_8") (pintype "power_in"))
      (node (ref "VDD_3V901") (pin "P$1") (pinfunction "P$1_P$1") (pintype "passive"))
    )
    (net (code "13") (name "CAN1_RX_1") (class "Default")
      (node (ref "U$101") (pin "70") (pinfunction "UART1/CAN1_TXD_24_70") (pintype "passive"))
      (node (ref "U202") (pin "6") (pinfunction "A5_6") (pintype "bidirectional"))
      (node (ref "U301") (pin "4") (pinfunction "DOUT_4") (pintype "output"))
    )
    (net (code "14") (name "CAN1_TX_1") (class "Default")
      (node (ref "U$101") (pin "72") (pinfunction "UART1/CAN1_RXD_26_72") (pintype "passive"))
      (node (ref "U202") (pin "7") (pinfunction "A6_7") (pintype "bidirectional"))
      (node (ref "U301") (pin "1") (pinfunction "DIN_1") (pintype "input"))
    )
    (net (code "15") (name "CAN_H") (class "Default")
      (node (ref "CAN_H") (pin "P$1") (pinfunction "P$1_P$1") (pintype "passive"))
      (node (ref "J307") (pin "2") (pinfunction "2_2") (pintype "passive"))
      (node (ref "R309") (pin "P$1") (pinfunction "1_P$1") (pintype "passive"))
      (node (ref "U301") (pin "7") (pinfunction "CANH_7") (pintype "bidirectional"))
    )
    (net (code "16") (name "CAN_L") (class "Default")
      (node (ref "CAN_L") (pin "P$1") (pinfunction "P$1_P$1") (pintype "passive"))
      (node (ref "J307") (pin "3") (pinfunction "3_3") (pintype "passive"))
      (node (ref "R309") (pin "P$2") (pinfunction "2_P$2") (pintype "passive"))
      (node (ref "U301") (pin "6") (pinfunction "CANL_6") (pintype "bidirectional"))
    )
    (net (code "17") (name "CH_1") (class "Default")
      (node (ref "U$101") (pin "28") (pinfunction "PRU1_R30/31[10]_28_28") (pintype "passive"))
      (node (ref "U701") (pin "5") (pinfunction "A4_5") (pintype "bidirectional"))
    )
    (net (code "18") (name "CH_1_OUT") (class "Default")
      (node (ref "R714") (pin "P$1") (pinfunction "1_P$1") (pintype "passive"))
      (node (ref "U701") (pin "16") (pinfunction "B4_16") (pintype "bidirectional"))
    )
    (net (code "19") (name "CH_2") (class "Default")
      (node (ref "U$101") (pin "27") (pinfunction "27_PRU1_R30/31[8]_27") (pintype "passive"))
      (node (ref "U701") (pin "4") (pinfunction "A3_4") (pintype "bidirectional"))
    )
    (net (code "20") (name "CH_2_OUT") (class "Default")
      (node (ref "R713") (pin "P$1") (pinfunction "1_P$1") (pintype "passive"))
      (node (ref "U701") (pin "17") (pinfunction "B3_17") (pintype "bidirectional"))
    )
    (net (code "21") (name "CH_3") (class "Default")
      (node (ref "U$101") (pin "30") (pinfunction "PRU1_R30/31[11]_30_30") (pintype "passive"))
      (node (ref "U701") (pin "3") (pinfunction "A2_3") (pintype "bidirectional"))
    )
    (net (code "22") (name "CH_3_OUT") (class "Default")
      (node (ref "R712") (pin "P$1") (pinfunction "1_P$1") (pintype "passive"))
      (node (ref "U701") (pin "18") (pinfunction "B2_18") (pintype "bidirectional"))
    )
    (net (code "23") (name "CH_4") (class "Default")
      (node (ref "U$101") (pin "29") (pinfunction "29_PRU1_R30/31[9]_29") (pintype "passive"))
      (node (ref "U701") (pin "1") (pinfunction "A1_1") (pintype "bidirectional"))
    )
    (net (code "24") (name "CH_4_OUT") (class "Default")
      (node (ref "R701") (pin "P$1") (pinfunction "1_P$1") (pintype "passive"))
      (node (ref "U701") (pin "20") (pinfunction "B1_20") (pintype "bidirectional"))
    )
    (net (code "25") (name "CH_5") (class "Default")
      (node (ref "U$101") (pin "40") (pinfunction "PRU1_R30/31[7]_40_40") (pintype "passive"))
      (node (ref "U702") (pin "9") (pinfunction "A8_9") (pintype "bidirectional"))
    )
    (net (code "26") (name "CH_5_OUT") (class "Default")
      (node (ref "R702") (pin "P$1") (pinfunction "1_P$1") (pintype "passive"))
      (node (ref "U702") (pin "12") (pinfunction "B8_12") (pintype "bidirectional"))
    )
    (net (code "27") (name "CH_6") (class "Default")
      (node (ref "U$101") (pin "39") (pinfunction "39_PRU1_R30/31[6]_39") (pintype "passive"))
      (node (ref "U702") (pin "8") (pinfunction "A7_8") (pintype "bidirectional"))
    )
    (net (code "28") (name "CH_6_OUT") (class "Default")
      (node (ref "R703") (pin "P$1") (pinfunction "1_P$1") (pintype "passive"))
      (node (ref "U702") (pin "13") (pinfunction "B7_13") (pintype "bidirectional"))
    )
    (net (code "29") (name "CH_7") (class "Default")
      (node (ref "U$101") (pin "42") (pinfunction "PRU1_R30/31[5]_42_42") (pintype "passive"))
      (node (ref "U702") (pin "7") (pinfunction "A6_7") (pintype "bidirectional"))
    )
    (net (code "30") (name "CH_7_OUT") (class "Default")
      (node (ref "R704") (pin "P$1") (pinfunction "1_P$1") (pintype "passive"))
      (node (ref "U702") (pin "14") (pinfunction "B6_14") (pintype "bidirectional"))
    )
    (net (code "31") (name "CH_8") (class "Default")
      (node (ref "U$101") (pin "41") (pinfunction "41_PRU1_R30/31[4]_41") (pintype "passive"))
      (node (ref "U702") (pin "6") (pinfunction "A5_6") (pintype "bidirectional"))
    )
    (net (code "32") (name "CH_8_OUT") (class "Default")
      (node (ref "R705") (pin "P$1") (pinfunction "1_P$1") (pintype "passive"))
      (node (ref "U702") (pin "15") (pinfunction "B5_15") (pintype "bidirectional"))
    )
    (net (code "33") (name "CH_9") (class "Default")
      (node (ref "U$101") (pin "44") (pinfunction "PRU1_R30/31[3]_44_44") (pintype "passive"))
      (node (ref "U702") (pin "5") (pinfunction "A4_5") (pintype "bidirectional"))
    )
    (net (code "34") (name "CH_9_OUT") (class "Default")
      (node (ref "R706") (pin "P$1") (pinfunction "1_P$1") (pintype "passive"))
      (node (ref "U702") (pin "16") (pinfunction "B4_16") (pintype "bidirectional"))
    )
    (net (code "35") (name "CH_10") (class "Default")
      (node (ref "U$101") (pin "43") (pinfunction "43_PRU1_R30/31[2]_43") (pintype "passive"))
      (node (ref "U702") (pin "4") (pinfunction "A3_4") (pintype "bidirectional"))
    )
    (net (code "36") (name "CH_10_OUT") (class "Default")
      (node (ref "R707") (pin "P$1") (pinfunction "1_P$1") (pintype "passive"))
      (node (ref "U702") (pin "17") (pinfunction "B3_17") (pintype "bidirectional"))
    )
    (net (code "37") (name "CH_11") (class "Default")
      (node (ref "U$101") (pin "46") (pinfunction "PRU1_R30/31[1]_46_46") (pintype "passive"))
      (node (ref "U702") (pin "3") (pinfunction "A2_3") (pintype "bidirectional"))
    )
    (net (code "38") (name "CH_11_OUT") (class "Default")
      (node (ref "R708") (pin "P$1") (pinfunction "1_P$1") (pintype "passive"))
      (node (ref "U702") (pin "18") (pinfunction "B2_18") (pintype "bidirectional"))
    )
    (net (code "39") (name "CH_12") (class "Default")
      (node (ref "U$101") (pin "45") (pinfunction "45_PRU1_R30/31[0]_45") (pintype "passive"))
      (node (ref "U702") (pin "1") (pinfunction "A1_1") (pintype "bidirectional"))
    )
    (net (code "40") (name "CH_12_OUT") (class "Default")
      (node (ref "R709") (pin "P$1") (pinfunction "1_P$1") (pintype "passive"))
      (node (ref "U702") (pin "20") (pinfunction "B1_20") (pintype "bidirectional"))
    )
    (net (code "41") (name "GND") (class "Default")
      (node (ref "C101") (pin "P$2") (pinfunction "2_P$2") (pintype "passive"))
      (node (ref "C201") (pin "P$2") (pinfunction "2_P$2") (pintype "passive"))
      (node (ref "C202") (pin "P$2") (pinfunction "2_P$2") (pintype "passive"))
      (node (ref "C301") (pin "P$2") (pinfunction "2_P$2") (pintype "passive"))
      (node (ref "C302") (pin "P$2") (pinfunction "2_P$2") (pintype "passive"))
      (node (ref "C303") (pin "P$2") (pinfunction "2_P$2") (pintype "passive"))
      (node (ref "C304") (pin "P$2") (pinfunction "2_P$2") (pintype "passive"))
      (node (ref "C305") (pin "P$2") (pinfunction "2_P$2") (pintype "passive"))
      (node (ref "C401") (pin "P$2") (pinfunction "2_P$2") (pintype "passive"))
      (node (ref "C402") (pin "P$2") (pinfunction "2_P$2") (pintype "passive"))
      (node (ref "C404") (pin "P$2") (pinfunction "2_P$2") (pintype "passive"))
      (node (ref "C405") (pin "P$1") (pinfunction "1_P$1") (pintype "passive"))
      (node (ref "C406") (pin "P$1") (pinfunction "1_P$1") (pintype "passive"))
      (node (ref "C407") (pin "P$2") (pinfunction "2_P$2") (pintype "passive"))
      (node (ref "C408") (pin "P$2") (pinfunction "2_P$2") (pintype "passive"))
      (node (ref "C409") (pin "P$2") (pinfunction "2_P$2") (pintype "passive"))
      (node (ref "C410") (pin "P$2") (pinfunction "2_P$2") (pintype "passive"))
      (node (ref "C411") (pin "P$2") (pinfunction "2_P$2") (pintype "passive"))
      (node (ref "C412") (pin "P$2") (pinfunction "2_P$2") (pintype "passive"))
      (node (ref "C413") (pin "P$2") (pinfunction "2_P$2") (pintype "passive"))
      (node (ref "C414") (pin "P$2") (pinfunction "2_P$2") (pintype "passive"))
      (node (ref "C415") (pin "P$2") (pinfunction "2_P$2") (pintype "passive"))
      (node (ref "C416") (pin "P$2") (pinfunction "2_P$2") (pintype "passive"))
      (node (ref "C501") (pin "P$2") (pinfunction "2_P$2") (pintype "passive"))
      (node (ref "C502") (pin "P$2") (pinfunction "2_P$2") (pintype "passive"))
      (node (ref "C503") (pin "P$2") (pinfunction "2_P$2") (pintype "passive"))
      (node (ref "C504") (pin "P$2") (pinfunction "2_P$2") (pintype "passive"))
      (node (ref "C505") (pin "P$2") (pinfunction "2_P$2") (pintype "passive"))
      (node (ref "C506") (pin "P$2") (pinfunction "2_P$2") (pintype "passive"))
      (node (ref "C507") (pin "P$2") (pinfunction "2_P$2") (pintype "passive"))
      (node (ref "C508") (pin "P$2") (pinfunction "2_P$2") (pintype "passive"))
      (node (ref "C509") (pin "P$2") (pinfunction "2_P$2") (pintype "passive"))
      (node (ref "C510") (pin "P$2") (pinfunction "2_P$2") (pintype "passive"))
      (node (ref "C601") (pin "P$2") (pinfunction "2_P$2") (pintype "passive"))
      (node (ref "C602") (pin "P$2") (pinfunction "2_P$2") (pintype "passive"))
      (node (ref "C603") (pin "P$2") (pinfunction "2_P$2") (pintype "passive"))
      (node (ref "C604") (pin "P$2") (pinfunction "2_P$2") (pintype "passive"))
      (node (ref "C701") (pin "P$2") (pinfunction "2_P$2") (pintype "passive"))
      (node (ref "C702") (pin "P$2") (pinfunction "2_P$2") (pintype "passive"))
      (node (ref "C703") (pin "P$2") (pinfunction "2_P$2") (pintype "passive"))
      (node (ref "C801") (pin "P$2") (pinfunction "2_P$2") (pintype "passive"))
      (node (ref "C805") (pin "P$2") (pinfunction "2_P$2") (pintype "passive"))
      (node (ref "D201") (pin "A") (pinfunction "A_A") (pintype "passive"))
      (node (ref "D202") (pin "A") (pinfunction "A_A") (pintype "passive"))
      (node (ref "D203") (pin "A") (pinfunction "A_A") (pintype "passive"))
      (node (ref "D301") (pin "A") (pinfunction "A_A") (pintype "passive"))
      (node (ref "D302") (pin "A") (pinfunction "A_A") (pintype "passive"))
      (node (ref "D303") (pin "A") (pinfunction "A_A") (pintype "passive"))
      (node (ref "D601") (pin "A") (pinfunction "A_A") (pintype "passive"))
      (node (ref "D701") (pin "A") (pinfunction "A_A") (pintype "passive"))
      (node (ref "D702") (pin "A") (pinfunction "A_A") (pintype "passive"))
      (node (ref "D703") (pin "A") (pinfunction "A_A") (pintype "passive"))
      (node (ref "D706") (pin "A") (pinfunction "A_A") (pintype "passive"))
      (node (ref "GND") (pin "P$1") (pinfunction "P$1_P$1") (pintype "passive"))
      (node (ref "GND.") (pin "P$1") (pinfunction "P$1_P$1") (pintype "passive"))
      (node (ref "J305") (pin "3") (pinfunction "3_3") (pintype "passive"))
      (node (ref "J305") (pin "P$4") (pinfunction "P$1_P$4") (pintype "bidirectional"))
      (node (ref "J305") (pin "P$5") (pinfunction "P$2_P$5") (pintype "bidirectional"))
      (node (ref "J306") (pin "4") (pinfunction "4_4") (pintype "passive"))
      (node (ref "J306") (pin "P$5") (pinfunction "P$1_P$5") (pintype "bidirectional"))
      (node (ref "J306") (pin "P$6") (pinfunction "P$2_P$6") (pintype "bidirectional"))
      (node (ref "J307") (pin "4") (pinfunction "4_4") (pintype "passive"))
      (node (ref "J307") (pin "P$5") (pinfunction "P$1_P$5") (pintype "bidirectional"))
      (node (ref "J307") (pin "P$6") (pinfunction "P$2_P$6") (pintype "bidirectional"))
      (node (ref "J308") (pin "4") (pinfunction "4_4") (pintype "passive"))
      (node (ref "J308") (pin "P$5") (pinfunction "P$1_P$5") (pintype "bidirectional"))
      (node (ref "J308") (pin "P$6") (pinfunction "P$2_P$6") (pintype "bidirectional"))
      (node (ref "J309") (pin "3") (pinfunction "3_3") (pintype "passive"))
      (node (ref "J309") (pin "5") (pinfunction "5_5") (pintype "passive"))
      (node (ref "J309") (pin "P$6") (pinfunction "P$1_P$6") (pintype "bidirectional"))
      (node (ref "J309") (pin "P$7") (pinfunction "P$2_P$7") (pintype "bidirectional"))
      (node (ref "J310") (pin "4") (pinfunction "4_4") (pintype "passive"))
      (node (ref "J310") (pin "P$5") (pinfunction "P$1_P$5") (pintype "bidirectional"))
      (node (ref "J310") (pin "P$6") (pinfunction "P$2_P$6") (pintype "bidirectional"))
      (node (ref "J314") (pin "4") (pinfunction "4_4") (pintype "passive"))
      (node (ref "J314") (pin "P$5") (pinfunction "P$1_P$5") (pintype "bidirectional"))
      (node (ref "J314") (pin "P$6") (pinfunction "P$2_P$6") (pintype "bidirectional"))
      (node (ref "J701") (pin "P$2") (pinfunction "P$2_P$2") (pintype "bidirectional"))
      (node (ref "J801") (pin "5") (pinfunction "5_5") (pintype "passive"))
      (node (ref "J801") (pin "6") (pinfunction "6_6") (pintype "passive"))
      (node (ref "L201") (pin "P$3") (pinfunction "P$3_P$3") (pintype "bidirectional"))
      (node (ref "L201") (pin "P$4") (pinfunction "P$3_P$4") (pintype "bidirectional"))
      (node (ref "L201") (pin "P$5") (pinfunction "P$3_P$5") (pintype "bidirectional"))
      (node (ref "L202") (pin "P$3") (pinfunction "P$3_P$3") (pintype "bidirectional"))
      (node (ref "L202") (pin "P$4") (pinfunction "P$3_P$4") (pintype "bidirectional"))
      (node (ref "L202") (pin "P$5") (pinfunction "P$3_P$5") (pintype "bidirectional"))
      (node (ref "L203") (pin "P$3") (pinfunction "P$3_P$3") (pintype "bidirectional"))
      (node (ref "L203") (pin "P$4") (pinfunction "P$3_P$4") (pintype "bidirectional"))
      (node (ref "L203") (pin "P$5") (pinfunction "P$3_P$5") (pintype "bidirectional"))
      (node (ref "L301") (pin "P$3") (pinfunction "P$3_P$3") (pintype "bidirectional"))
      (node (ref "L301") (pin "P$4") (pinfunction "P$3_P$4") (pintype "bidirectional"))
      (node (ref "L301") (pin "P$5") (pinfunction "P$3_P$5") (pintype "bidirectional"))
      (node (ref "L302") (pin "P$3") (pinfunction "P$3_P$3") (pintype "bidirectional"))
      (node (ref "L302") (pin "P$4") (pinfunction "P$3_P$4") (pintype "bidirectional"))
      (node (ref "L302") (pin "P$5") (pinfunction "P$3_P$5") (pintype "bidirectional"))
      (node (ref "L303") (pin "P$3") (pinfunction "P$3_P$3") (pintype "bidirectional"))
      (node (ref "L303") (pin "P$4") (pinfunction "P$3_P$4") (pintype "bidirectional"))
      (node (ref "L303") (pin "P$5") (pinfunction "P$3_P$5") (pintype "bidirectional"))
      (node (ref "L501") (pin "P$3") (pinfunction "P$3_P$3") (pintype "bidirectional"))
      (node (ref "L501") (pin "P$4") (pinfunction "P$3_P$4") (pintype "bidirectional"))
      (node (ref "L501") (pin "P$5") (pinfunction "P$3_P$5") (pintype "bidirectional"))
      (node (ref "L701") (pin "P$3") (pinfunction "P$3_P$3") (pintype "bidirectional"))
      (node (ref "L701") (pin "P$4") (pinfunction "P$3_P$4") (pintype "bidirectional"))
      (node (ref "L701") (pin "P$5") (pinfunction "P$3_P$5") (pintype "bidirectional"))
      (node (ref "L801") (pin "P$3") (pinfunction "P$3_P$3") (pintype "bidirectional"))
      (node (ref "L801") (pin "P$4") (pinfunction "P$3_P$4") (pintype "bidirectional"))
      (node (ref "L801") (pin "P$5") (pinfunction "P$3_P$5") (pintype "bidirectional"))
      (node (ref "L802") (pin "P$3") (pinfunction "P$3_P$3") (pintype "bidirectional"))
      (node (ref "L802") (pin "P$4") (pinfunction "P$3_P$4") (pintype "bidirectional"))
      (node (ref "L802") (pin "P$5") (pinfunction "P$3_P$5") (pintype "bidirectional"))
      (node (ref "R102") (pin "P$1") (pinfunction "1_P$1") (pintype "passive"))
      (node (ref "R215") (pin "P$1") (pinfunction "1_P$1") (pintype "passive"))
      (node (ref "R216") (pin "P$1") (pinfunction "1_P$1") (pintype "passive"))
      (node (ref "R303") (pin "P$1") (pinfunction "1_P$1") (pintype "passive"))
      (node (ref "R310") (pin "P$1") (pinfunction "1_P$1") (pintype "passive"))
      (node (ref "R311") (pin "P$1") (pinfunction "1_P$1") (pintype "passive"))
      (node (ref "R314") (pin "P$1") (pinfunction "1_P$1") (pintype "passive"))
      (node (ref "R315") (pin "P$2") (pinfunction "2_P$2") (pintype "passive"))
      (node (ref "R501") (pin "P$2") (pinfunction "2_P$2") (pintype "passive"))
      (node (ref "R504") (pin "P$2") (pinfunction "2_P$2") (pintype "passive"))
      (node (ref "R505") (pin "1") (pinfunction "1_1") (pintype "passive"))
      (node (ref "R506") (pin "P$2") (pinfunction "2_P$2") (pintype "passive"))
      (node (ref "R509") (pin "P$2") (pinfunction "2_P$2") (pintype "passive"))
      (node (ref "R603") (pin "P$2") (pinfunction "2_P$2") (pintype "passive"))
      (node (ref "R605") (pin "P$1") (pinfunction "1_P$1") (pintype "passive"))
      (node (ref "R607") (pin "P$2") (pinfunction "2_P$2") (pintype "passive"))
      (node (ref "R608") (pin "P$1") (pinfunction "1_P$1") (pintype "passive"))
      (node (ref "R613") (pin "P$2") (pinfunction "2_P$2") (pintype "passive"))
      (node (ref "R716") (pin "P$1") (pinfunction "1_P$1") (pintype "passive"))
      (node (ref "R718") (pin "P$1") (pinfunction "1_P$1") (pintype "passive"))
      (node (ref "R719") (pin "P$1") (pinfunction "1_P$1") (pintype "passive"))
      (node (ref "R801") (pin "P$2") (pinfunction "2_P$2") (pintype "passive"))
      (node (ref "R802") (pin "P$2") (pinfunction "2_P$2") (pintype "passive"))
      (node (ref "R806") (pin "P$1") (pinfunction "1_P$1") (pintype "passive"))
      (node (ref "R807") (pin "P$2") (pinfunction "2_P$2") (pintype "passive"))
      (node (ref "R808") (pin "P$2") (pinfunction "2_P$2") (pintype "passive"))
      (node (ref "U$101") (pin "1") (pinfunction "1_GND_1") (pintype "power_in"))
      (node (ref "U$101") (pin "2") (pinfunction "GND_2_2") (pintype "power_in"))
      (node (ref "U$101") (pin "47") (pinfunction "1_GND_47") (pintype "power_in"))
      (node (ref "U$101") (pin "48") (pinfunction "GND_2_48") (pintype "power_in"))
      (node (ref "U$101") (pin "80") (pinfunction "GNDA_ADC_34_80") (pintype "passive"))
      (node (ref "U$101") (pin "89") (pinfunction "43_GND_89") (pintype "power_in"))
      (node (ref "U$101") (pin "90") (pinfunction "GND_44_90") (pintype "power_in"))
      (node (ref "U$101") (pin "91") (pinfunction "45_GND_91") (pintype "power_in"))
      (node (ref "U$101") (pin "92") (pinfunction "GND_46_92") (pintype "power_in"))
      (node (ref "U$101") (pin "93") (pinfunction "GND_93") (pintype "bidirectional"))
      (node (ref "U$101") (pin "P$1") (pinfunction "SCREW$1_P$1") (pintype "bidirectional"))
      (node (ref "U$101") (pin "P$2") (pinfunction "SCREW$2_P$2") (pintype "bidirectional"))
      (node (ref "U$101") (pin "P$3") (pinfunction "SCREW$3_P$3") (pintype "bidirectional"))
      (node (ref "U$101") (pin "P$4") (pinfunction "SCREW$4_P$4") (pintype "bidirectional"))
      (node (ref "U$101") (pin "TP8") (pinfunction "BATT_GND_TP8") (pintype "bidirectional"))
      (node (ref "U$11") (pin "2") (pinfunction "2_2") (pintype "passive"))
      (node (ref "U$11") (pin "P$3") (pinfunction "P$1_P$3") (pintype "bidirectional"))
      (node (ref "U$11") (pin "P$4") (pinfunction "P$2_P$4") (pintype "bidirectional"))
      (node (ref "U$12") (pin "P$4") (pinfunction "P$1_P$4") (pintype "bidirectional"))
      (node (ref "U$12") (pin "P$5") (pinfunction "P$2_P$5") (pintype "bidirectional"))
      (node (ref "U$2") (pin "6") (pinfunction "6_6") (pintype "passive"))
      (node (ref "U$2") (pin "P$7") (pinfunction "P$1_P$7") (pintype "bidirectional"))
      (node (ref "U$2") (pin "P$8") (pinfunction "P$2_P$8") (pintype "bidirectional"))
      (node (ref "U$201") (pin "6") (pinfunction "6_6") (pintype "passive"))
      (node (ref "U$201") (pin "P$7") (pinfunction "P$1_P$7") (pintype "bidirectional"))
      (node (ref "U$201") (pin "P$8") (pinfunction "P$2_P$8") (pintype "bidirectional"))
      (node (ref "U$3") (pin "P$7") (pinfunction "P$1_P$7") (pintype "bidirectional"))
      (node (ref "U$3") (pin "P$8") (pinfunction "P$2_P$8") (pintype "bidirectional"))
      (node (ref "U$4") (pin "6") (pinfunction "6_6") (pintype "passive"))
      (node (ref "U$4") (pin "P$7") (pinfunction "P$1_P$7") (pintype "bidirectional"))
      (node (ref "U$4") (pin "P$8") (pinfunction "P$2_P$8") (pintype "bidirectional"))
      (node (ref "U1") (pin "1") (pinfunction "A0_1") (pintype "bidirectional"))
      (node (ref "U1") (pin "2") (pinfunction "A1_2") (pintype "bidirectional"))
      (node (ref "U1") (pin "4") (pinfunction "VSS_4") (pintype "power_in"))
      (node (ref "U102") (pin "4") (pinfunction "VSS_4") (pintype "bidirectional"))
      (node (ref "U2") (pin "4") (pinfunction "VSS_4") (pintype "power_in"))
      (node (ref "U201") (pin "11") (pinfunction "GND_11") (pintype "power_in"))
      (node (ref "U202") (pin "11") (pinfunction "GND_11") (pintype "power_in"))
      (node (ref "U301") (pin "2") (pinfunction "GND_2") (pintype "power_in"))
      (node (ref "U301") (pin "5") (pinfunction "SHDN_5") (pintype "input"))
      (node (ref "U302") (pin "11") (pinfunction "GND_11") (pintype "power_in"))
      (node (ref "U303") (pin "1") (pinfunction "GND_1") (pintype "bidirectional"))
      (node (ref "U401") (pin "2") (pinfunction "PS_2") (pintype "bidirectional"))
      (node (ref "U401") (pin "3") (pinfunction "GND_3") (pintype "bidirectional"))
      (node (ref "U402") (pin "3") (pinfunction "GND_3") (pintype "bidirectional"))
      (node (ref "U402") (pin "4") (pinfunction "CSB1_4") (pintype "bidirectional"))
      (node (ref "U403") (pin "1") (pinfunction "CLKIN_1") (pintype "bidirectional"))
      (node (ref "U403") (pin "11") (pinfunction "FSYNC_11") (pintype "bidirectional"))
      (node (ref "U403") (pin "18") (pinfunction "GND_18") (pintype "bidirectional"))
      (node (ref "U405") (pin "11") (pinfunction "FSYNC_11") (pintype "bidirectional"))
      (node (ref "U405") (pin "18") (pinfunction "GND_18") (pintype "bidirectional"))
      (node (ref "U405") (pin "20") (pinfunction "RESV_20") (pintype "bidirectional"))
      (node (ref "U406") (pin "2") (pinfunction "GND_2") (pintype "bidirectional"))
      (node (ref "U406") (pin "3") (pinfunction "GND_3") (pintype "bidirectional"))
      (node (ref "U406") (pin "4") (pinfunction "GND_4") (pintype "bidirectional"))
      (node (ref "U406") (pin "5") (pinfunction "GND_5") (pintype "bidirectional"))
      (node (ref "U406") (pin "6") (pinfunction "GND_6") (pintype "bidirectional"))
      (node (ref "U407") (pin "P$1") (pinfunction "GND_P$1") (pintype "bidirectional"))
      (node (ref "U407") (pin "P$7") (pinfunction "GND_P$7") (pintype "bidirectional"))
      (node (ref "U501") (pin "2") (pinfunction "VSS_2") (pintype "bidirectional"))
      (node (ref "U501") (pin "6") (pinfunction "VBAT_6") (pintype "bidirectional"))
      (node (ref "U501") (pin "GND") (pinfunction "VSS_GND") (pintype "bidirectional"))
      (node (ref "U501") (pin "P$2") (pinfunction "VSS_P$2") (pintype "bidirectional"))
      (node (ref "U501") (pin "P$3") (pinfunction "VSS_P$3") (pintype "bidirectional"))
      (node (ref "U502") (pin "2") (pinfunction "GND_2") (pintype "bidirectional"))
      (node (ref "U502") (pin "GND") (pinfunction "GND_GND") (pintype "bidirectional"))
      (node (ref "U503") (pin "2") (pinfunction "VSS_2") (pintype "bidirectional"))
      (node (ref "U503") (pin "6") (pinfunction "VBAT_6") (pintype "bidirectional"))
      (node (ref "U503") (pin "GND") (pinfunction "VSS_GND") (pintype "bidirectional"))
      (node (ref "U503") (pin "P$2") (pinfunction "VSS_P$2") (pintype "bidirectional"))
      (node (ref "U503") (pin "P$3") (pinfunction "VSS_P$3") (pintype "bidirectional"))
      (node (ref "U601") (pin "5") (pinfunction "GND_5") (pintype "power_in"))
      (node (ref "U602") (pin "4") (pinfunction "GND_4") (pintype "power_in"))
      (node (ref "U701") (pin "11") (pinfunction "GND_11") (pintype "power_in"))
      (node (ref "U702") (pin "11") (pinfunction "GND_11") (pintype "power_in"))
      (node (ref "U703") (pin "1") (pinfunction "~{1OE}_1") (pintype "input"))
      (node (ref "U703") (pin "4") (pinfunction "GND_4") (pintype "power_in"))
      (node (ref "U704") (pin "12") (pinfunction "GND_12") (pintype "bidirectional"))
      (node (ref "U704") (pin "15") (pinfunction "GND_15") (pintype "bidirectional"))
      (node (ref "U704") (pin "18") (pinfunction "GND_18") (pintype "bidirectional"))
      (node (ref "U704") (pin "21") (pinfunction "GND_21") (pintype "bidirectional"))
      (node (ref "U704") (pin "24") (pinfunction "GND_24") (pintype "bidirectional"))
      (node (ref "U704") (pin "27") (pinfunction "GND_27") (pintype "bidirectional"))
      (node (ref "U704") (pin "3") (pinfunction "GND_3") (pintype "bidirectional"))
      (node (ref "U704") (pin "30") (pinfunction "GND_30") (pintype "bidirectional"))
      (node (ref "U704") (pin "33") (pinfunction "GND_33") (pintype "bidirectional"))
      (node (ref "U704") (pin "36") (pinfunction "GND_36") (pintype "bidirectional"))
      (node (ref "U704") (pin "39") (pinfunction "GND_39") (pintype "bidirectional"))
      (node (ref "U704") (pin "42") (pinfunction "GND_42") (pintype "bidirectional"))
      (node (ref "U704") (pin "6") (pinfunction "GND_6") (pintype "bidirectional"))
      (node (ref "U704") (pin "9") (pinfunction "GND_9") (pintype "bidirectional"))
      (node (ref "U802") (pin "2") (pinfunction "GND_2") (pintype "bidirectional"))
      (node (ref "U802") (pin "4") (pinfunction "EN2_4") (pintype "bidirectional"))
      (node (ref "U802") (pin "GND") (pinfunction "GND_GND") (pintype "bidirectional"))
      (node (ref "X801") (pin "4") (pinfunction "S_4") (pintype "passive"))
    )
    (net (code "42") (name "GYRO_DRDY") (class "Default")
      (node (ref "U$101") (pin "34") (pinfunction "GPOI2[17]_34_34") (pintype "passive"))
      (node (ref "U406") (pin "12") (pinfunction "DRDY_G_12") (pintype "bidirectional"))
    )
    (net (code "43") (name "I2C2_SCL") (class "Default")
      (node (ref "R301") (pin "P$1") (pinfunction "1_P$1") (pintype "passive"))
      (node (ref "U$101") (pin "65") (pinfunction "19_I2C2_SCL_65") (pintype "passive"))
      (node (ref "U1") (pin "6") (pinfunction "SCL_6") (pintype "bidirectional"))
      (node (ref "U2") (pin "6") (pinfunction "SCL_6") (pintype "bidirectional"))
      (node (ref "U303") (pin "3") (pinfunction "SCL1_3") (pintype "bidirectional"))
      (node (ref "U402") (pin "8") (pinfunction "SCLK_8") (pintype "bidirectional"))
      (node (ref "U601") (pin "3") (pinfunction "SCL_3") (pintype "bidirectional"))
    )
    (net (code "44") (name "I2C2_SDA") (class "Default")
      (node (ref "R302") (pin "P$1") (pinfunction "1_P$1") (pintype "passive"))
      (node (ref "U$101") (pin "66") (pinfunction "I2C2_SDA_20_66") (pintype "passive"))
      (node (ref "U1") (pin "5") (pinfunction "SDA_5") (pintype "bidirectional"))
      (node (ref "U2") (pin "5") (pinfunction "SDA_5") (pintype "bidirectional"))
      (node (ref "U303") (pin "4") (pinfunction "SDA1_4") (pintype "bidirectional"))
      (node (ref "U402") (pin "7") (pinfunction "SDI/SDA_7") (pintype "bidirectional"))
      (node (ref "U601") (pin "2") (pinfunction "SDA_2") (pintype "bidirectional"))
    )
    (net (code "45") (name "MAG_DRDY") (class "Default")
      (node (ref "U$101") (pin "10") (pinfunction "GPIO2[4]_10_10") (pintype "passive"))
      (node (ref "U406") (pin "13") (pinfunction "INT1_XM_13") (pintype "bidirectional"))
    )
    (net (code "46") (name "MPU_6000_DRDY") (class "Default")
      (node (ref "U$101") (pin "14") (pinfunction "GPIO0[26]_14_14") (pintype "passive"))
      (node (ref "U403") (pin "12") (pinfunction "INT_12") (pintype "bidirectional"))
    )
    (net (code "47") (name "MPU_6500_DRDY") (class "Default")
      (node (ref "U$101") (pin "7") (pinfunction "7_GPIO2[2]_7") (pintype "passive"))
      (node (ref "U405") (pin "12") (pinfunction "INT_12") (pintype "bidirectional"))
    )
    (net (code "48") (name "Net-(C402-1)") (class "Default")
      (node (ref "C402") (pin "P$1") (pinfunction "1_P$1") (pintype "passive"))
      (node (ref "U406") (pin "7") (pinfunction "C1_XM_7") (pintype "bidirectional"))
    )
    (net (code "49") (name "Net-(C403-1)") (class "Default")
      (node (ref "C403") (pin "P$1") (pinfunction "1_P$1") (pintype "passive"))
      (node (ref "U406") (pin "8") (pinfunction "SETC_XM_8") (pintype "bidirectional"))
    )
    (net (code "50") (name "Net-(C403-2)") (class "Default")
      (node (ref "C403") (pin "P$2") (pinfunction "2_P$2") (pintype "passive"))
      (node (ref "U406") (pin "9") (pinfunction "SETP_XM_9") (pintype "bidirectional"))
    )
    (net (code "51") (name "Net-(C409-1)") (class "Default")
      (node (ref "C409") (pin "P$1") (pinfunction "1_P$1") (pintype "passive"))
      (node (ref "U403") (pin "10") (pinfunction "REGOUT_10") (pintype "bidirectional"))
    )
    (net (code "52") (name "Net-(C411-1)") (class "Default")
      (node (ref "C411") (pin "P$1") (pinfunction "1_P$1") (pintype "passive"))
      (node (ref "U405") (pin "10") (pinfunction "REGOUT_10") (pintype "bidirectional"))
    )
    (net (code "53") (name "Net-(C416-1)") (class "Default")
      (node (ref "C416") (pin "P$1") (pinfunction "1_P$1") (pintype "passive"))
      (node (ref "U403") (pin "20") (pinfunction "CPOUT_20") (pintype "bidirectional"))
    )
    (net (code "54") (name "Net-(C501-1)") (class "Default")
      (node (ref "C501") (pin "P$1") (pinfunction "1_P$1") (pintype "passive"))
      (node (ref "C502") (pin "P$1") (pinfunction "1_P$1") (pintype "passive"))
      (node (ref "L501") (pin "P$2") (pinfunction "P$2_P$2") (pintype "bidirectional"))
      (node (ref "U502") (pin "1") (pinfunction "VIN_1") (pintype "bidirectional"))
    )
    (net (code "55") (name "Net-(C503-1)") (class "Default")
      (node (ref "C503") (pin "P$1") (pinfunction "1_P$1") (pintype "passive"))
      (node (ref "U502") (pin "6") (pinfunction "CSET_6") (pintype "bidirectional"))
    )
    (net (code "56") (name "Net-(C603-1)") (class "Default")
      (node (ref "C603") (pin "P$1") (pinfunction "1_P$1") (pintype "passive"))
      (node (ref "R604") (pin "P$1") (pinfunction "1_P$1") (pintype "passive"))
      (node (ref "U$11") (pin "1") (pinfunction "1_1") (pintype "passive"))
      (node (ref "U602") (pin "1") (pinfunction "OUT_1") (pintype "output"))
    )
    (net (code "57") (name "Net-(C604-1)") (class "Default")
      (node (ref "C604") (pin "P$1") (pinfunction "1_P$1") (pintype "passive"))
      (node (ref "R606") (pin "P$1") (pinfunction "1_P$1") (pintype "passive"))
      (node (ref "R614") (pin "P$1") (pinfunction "1_P$1") (pintype "passive"))
      (node (ref "U602") (pin "6") (pinfunction "VCC_6") (pintype "bidirectional"))
    )
    (net (code "58") (name "Net-(D201-PadC)") (class "Default")
      (node (ref "D201") (pin "C") (pinfunction "C_C") (pintype "passive"))
      (node (ref "L201") (pin "P$2") (pinfunction "P$2_P$2") (pintype "bidirectional"))
      (node (ref "U$201") (pin "1") (pinfunction "1_1") (pintype "passive"))
    )
    (net (code "59") (name "Net-(D202-PadC)") (class "Default")
      (node (ref "D202") (pin "C") (pinfunction "C_C") (pintype "passive"))
      (node (ref "L202") (pin "P$2") (pinfunction "P$2_P$2") (pintype "bidirectional"))
      (node (ref "U$2") (pin "1") (pinfunction "1_1") (pintype "passive"))
    )
    (net (code "60") (name "Net-(D203-PadC)") (class "Default")
      (node (ref "D203") (pin "C") (pinfunction "C_C") (pintype "passive"))
      (node (ref "L203") (pin "P$2") (pinfunction "P$2_P$2") (pintype "bidirectional"))
      (node (ref "U$3") (pin "1") (pinfunction "1_1") (pintype "passive"))
      (node (ref "U$4") (pin "1") (pinfunction "1_1") (pintype "passive"))
    )
    (net (code "61") (name "Net-(D301-PadC)") (class "Default")
      (node (ref "D301") (pin "C") (pinfunction "C_C") (pintype "passive"))
      (node (ref "J305") (pin "1") (pinfunction "1_1") (pintype "passive"))
      (node (ref "J306") (pin "1") (pinfunction "1_1") (pintype "passive"))
      (node (ref "J310") (pin "1") (pinfunction "1_1") (pintype "passive"))
      (node (ref "J314") (pin "1") (pinfunction "1_1") (pintype "passive"))
      (node (ref "L301") (pin "P$2") (pinfunction "P$2_P$2") (pintype "bidirectional"))
    )
    (net (code "62") (name "Net-(D302-PadC)") (class "Default")
      (node (ref "D302") (pin "C") (pinfunction "C_C") (pintype "passive"))
      (node (ref "J309") (pin "1") (pinfunction "1_1") (pintype "passive"))
      (node (ref "L302") (pin "P$2") (pinfunction "P$2_P$2") (pintype "bidirectional"))
    )
    (net (code "63") (name "Net-(D303-PadC)") (class "Default")
      (node (ref "D303") (pin "C") (pinfunction "C_C") (pintype "passive"))
      (node (ref "J307") (pin "1") (pinfunction "1_1") (pintype "passive"))
      (node (ref "L303") (pin "P$2") (pinfunction "P$2_P$2") (pintype "bidirectional"))
    )
    (net (code "64") (name "Net-(D704-A)") (class "Default")
      (node (ref "D704") (pin "ANODE") (pinfunction "A_ANODE") (pintype "passive"))
      (node (ref "D705") (pin "ANODE") (pinfunction "A_ANODE") (pintype "passive"))
      (node (ref "R3") (pin "P$2") (pinfunction "2_P$2") (pintype "passive"))
      (node (ref "U704") (pin "11") (pinfunction "5V_11") (pintype "bidirectional"))
      (node (ref "U704") (pin "14") (pinfunction "5V_14") (pintype "bidirectional"))
      (node (ref "U704") (pin "17") (pinfunction "5V_17") (pintype "bidirectional"))
      (node (ref "U704") (pin "2") (pinfunction "5V_2") (pintype "bidirectional"))
      (node (ref "U704") (pin "20") (pinfunction "5V_20") (pintype "bidirectional"))
      (node (ref "U704") (pin "23") (pinfunction "5V_23") (pintype "bidirectional"))
      (node (ref "U704") (pin "26") (pinfunction "5V_26") (pintype "bidirectional"))
      (node (ref "U704") (pin "29") (pinfunction "5V_29") (pintype "bidirectional"))
      (node (ref "U704") (pin "32") (pinfunction "5V_32") (pintype "bidirectional"))
      (node (ref "U704") (pin "35") (pinfunction "5V_35") (pintype "bidirectional"))
      (node (ref "U704") (pin "38") (pinfunction "5V_38") (pintype "bidirectional"))
      (node (ref "U704") (pin "5") (pinfunction "5V_5") (pintype "bidirectional"))
      (node (ref "U704") (pin "8") (pinfunction "5V_8") (pintype "bidirectional"))
    )
    (net (code "65") (name "Net-(D704-C)") (class "Default")
      (node (ref "D704") (pin "CATHODE") (pinfunction "C_CATHODE") (pintype "passive"))
      (node (ref "D705") (pin "CATHODE") (pinfunction "C_CATHODE") (pintype "passive"))
      (node (ref "D706") (pin "C") (pinfunction "C_C") (pintype "passive"))
      (node (ref "L701") (pin "P$1") (pinfunction "P$1_P$1") (pintype "bidirectional"))
    )
    (net (code "66") (name "Net-(F701-Pad2)") (class "Default")
      (node (ref "F701") (pin "2") (pinfunction "2_2") (pintype "bidirectional"))
      (node (ref "U704") (pin "41") (pinfunction "5V_41") (pintype "bidirectional"))
    )
    (net (code "67") (name "Net-(L601-2)") (class "Default")
      (node (ref "L601") (pin "P$2") (pinfunction "2_P$2") (pintype "passive"))
      (node (ref "U602") (pin "5") (pinfunction "SW_5") (pintype "passive"))
    )
    (net (code "68") (name "Net-(Q501-PadC)") (class "Default")
      (node (ref "Q501") (pin "C") (pinfunction "C_C") (pintype "passive"))
      (node (ref "R505") (pin "2") (pinfunction "2_2") (pintype "passive"))
    )
    (net (code "69") (name "Net-(R1-2)") (class "Default")
      (node (ref "R1") (pin "P$2") (pinfunction "2_P$2") (pintype "passive"))
      (node (ref "R804") (pin "P$1") (pinfunction "1_P$1") (pintype "passive"))
    )
    (net (code "70") (name "Net-(R2-2)") (class "Default")
      (node (ref "R2") (pin "P$2") (pinfunction "2_P$2") (pintype "passive"))
      (node (ref "R805") (pin "P$1") (pinfunction "1_P$1") (pintype "passive"))
    )
    (net (code "71") (name "Net-(R4-2)") (class "Default")
      (node (ref "R4") (pin "P$2") (pinfunction "2_P$2") (pintype "passive"))
      (node (ref "R508") (pin "P$1") (pinfunction "1_P$1") (pintype "passive"))
    )
    (net (code "72") (name "Net-(R103-1)") (class "Default")
      (node (ref "R103") (pin "P$1") (pinfunction "1_P$1") (pintype "passive"))
      (node (ref "U1") (pin "3") (pinfunction "A2_3") (pintype "bidirectional"))
    )
    (net (code "73") (name "Net-(R201-1)") (class "Default")
      (node (ref "R201") (pin "P$1") (pinfunction "1_P$1") (pintype "passive"))
      (node (ref "U201") (pin "20") (pinfunction "B1_20") (pintype "bidirectional"))
    )
    (net (code "74") (name "Net-(R202-1)") (class "Default")
      (node (ref "R202") (pin "P$1") (pinfunction "1_P$1") (pintype "passive"))
      (node (ref "U201") (pin "17") (pinfunction "B3_17") (pintype "bidirectional"))
    )
    (net (code "75") (name "Net-(R203-1)") (class "Default")
      (node (ref "R203") (pin "P$1") (pinfunction "1_P$1") (pintype "passive"))
      (node (ref "U201") (pin "15") (pinfunction "B5_15") (pintype "bidirectional"))
    )
    (net (code "76") (name "Net-(R204-1)") (class "Default")
      (node (ref "R204") (pin "P$1") (pinfunction "1_P$1") (pintype "passive"))
      (node (ref "U201") (pin "13") (pinfunction "B7_13") (pintype "bidirectional"))
    )
    (net (code "77") (name "Net-(R205-1)") (class "Default")
      (node (ref "R205") (pin "P$1") (pinfunction "1_P$1") (pintype "passive"))
      (node (ref "U202") (pin "17") (pinfunction "B3_17") (pintype "bidirectional"))
    )
    (net (code "78") (name "Net-(R206-1)") (class "Default")
      (node (ref "R206") (pin "P$1") (pinfunction "1_P$1") (pintype "passive"))
      (node (ref "U202") (pin "15") (pinfunction "B5_15") (pintype "bidirectional"))
    )
    (net (code "79") (name "Net-(R207-1)") (class "Default")
      (node (ref "R207") (pin "P$1") (pinfunction "1_P$1") (pintype "passive"))
      (node (ref "U202") (pin "13") (pinfunction "B7_13") (pintype "bidirectional"))
    )
    (net (code "80") (name "Net-(R208-1)") (class "Default")
      (node (ref "R208") (pin "P$1") (pinfunction "1_P$1") (pintype "passive"))
      (node (ref "U201") (pin "18") (pinfunction "B2_18") (pintype "bidirectional"))
    )
    (net (code "81") (name "Net-(R209-1)") (class "Default")
      (node (ref "R209") (pin "P$1") (pinfunction "1_P$1") (pintype "passive"))
      (node (ref "U201") (pin "16") (pinfunction "B4_16") (pintype "bidirectional"))
    )
    (net (code "82") (name "Net-(R210-1)") (class "Default")
      (node (ref "R210") (pin "P$1") (pinfunction "1_P$1") (pintype "passive"))
      (node (ref "U201") (pin "14") (pinfunction "B6_14") (pintype "bidirectional"))
    )
    (net (code "83") (name "Net-(R211-1)") (class "Default")
      (node (ref "R211") (pin "P$1") (pinfunction "1_P$1") (pintype "passive"))
      (node (ref "U201") (pin "12") (pinfunction "B8_12") (pintype "bidirectional"))
    )
    (net (code "84") (name "Net-(R212-1)") (class "Default")
      (node (ref "R212") (pin "P$1") (pinfunction "1_P$1") (pintype "passive"))
      (node (ref "U202") (pin "16") (pinfunction "B4_16") (pintype "bidirectional"))
    )
    (net (code "85") (name "Net-(R213-1)") (class "Default")
      (node (ref "R213") (pin "P$1") (pinfunction "1_P$1") (pintype "passive"))
      (node (ref "U202") (pin "14") (pinfunction "B6_14") (pintype "bidirectional"))
    )
    (net (code "86") (name "Net-(R214-1)") (class "Default")
      (node (ref "R214") (pin "P$1") (pinfunction "1_P$1") (pintype "passive"))
      (node (ref "U202") (pin "12") (pinfunction "B8_12") (pintype "bidirectional"))
    )
    (net (code "87") (name "Net-(R304-2)") (class "Default")
      (node (ref "J306") (pin "3") (pinfunction "3_3") (pintype "passive"))
      (node (ref "J310") (pin "3") (pinfunction "3_3") (pintype "passive"))
      (node (ref "J314") (pin "3") (pinfunction "3_3") (pintype "passive"))
      (node (ref "R304") (pin "P$2") (pinfunction "2_P$2") (pintype "passive"))
      (node (ref "U303") (pin "5") (pinfunction "SDA2_5") (pintype "bidirectional"))
    )
    (net (code "88") (name "Net-(R305-2)") (class "Default")
      (node (ref "J306") (pin "2") (pinfunction "2_2") (pintype "passive"))
      (node (ref "J310") (pin "2") (pinfunction "2_2") (pintype "passive"))
      (node (ref "J314") (pin "2") (pinfunction "2_2") (pintype "passive"))
      (node (ref "R305") (pin "P$2") (pinfunction "2_P$2") (pintype "passive"))
      (node (ref "U303") (pin "6") (pinfunction "SCL2_6") (pintype "bidirectional"))
    )
    (net (code "89") (name "Net-(R306-2)") (class "Default")
      (node (ref "R306") (pin "P$2") (pinfunction "2_P$2") (pintype "passive"))
      (node (ref "R7") (pin "P$1") (pinfunction "1_P$1") (pintype "passive"))
    )
    (net (code "90") (name "Net-(R307-2)") (class "Default")
      (node (ref "R307") (pin "P$2") (pinfunction "2_P$2") (pintype "passive"))
      (node (ref "R5") (pin "P$1") (pinfunction "1_P$1") (pintype "passive"))
    )
    (net (code "91") (name "Net-(R308-2)") (class "Default")
      (node (ref "R308") (pin "P$2") (pinfunction "2_P$2") (pintype "passive"))
      (node (ref "R6") (pin "P$1") (pinfunction "1_P$1") (pintype "passive"))
    )
    (net (code "92") (name "Net-(R310-2)") (class "Default")
      (node (ref "J309") (pin "2") (pinfunction "2_2") (pintype "passive"))
      (node (ref "R310") (pin "P$2") (pinfunction "2_P$2") (pintype "passive"))
      (node (ref "R5") (pin "P$2") (pinfunction "2_P$2") (pintype "passive"))
    )
    (net (code "93") (name "Net-(R311-2)") (class "Default")
      (node (ref "J309") (pin "4") (pinfunction "4_4") (pintype "passive"))
      (node (ref "R311") (pin "P$2") (pinfunction "2_P$2") (pintype "passive"))
      (node (ref "R6") (pin "P$2") (pinfunction "2_P$2") (pintype "passive"))
    )
    (net (code "94") (name "Net-(R312-1)") (class "Default")
      (node (ref "R312") (pin "P$1") (pinfunction "1_P$1") (pintype "passive"))
      (node (ref "U302") (pin "18") (pinfunction "B2_18") (pintype "bidirectional"))
    )
    (net (code "95") (name "Net-(R312-2)") (class "Default")
      (node (ref "J308") (pin "3") (pinfunction "3_3") (pintype "passive"))
      (node (ref "R312") (pin "P$2") (pinfunction "2_P$2") (pintype "passive"))
    )
    (net (code "96") (name "Net-(R313-1)") (class "Default")
      (node (ref "R313") (pin "P$1") (pinfunction "1_P$1") (pintype "passive"))
      (node (ref "U302") (pin "20") (pinfunction "B1_20") (pintype "bidirectional"))
    )
    (net (code "97") (name "Net-(R313-2)") (class "Default")
      (node (ref "J308") (pin "2") (pinfunction "2_2") (pintype "passive"))
      (node (ref "R313") (pin "P$2") (pinfunction "2_P$2") (pintype "passive"))
    )
    (net (code "98") (name "Net-(R315-1)") (class "Default")
      (node (ref "R315") (pin "P$1") (pinfunction "1_P$1") (pintype "passive"))
      (node (ref "U301") (pin "8") (pinfunction "RS_8") (pintype "input"))
    )
    (net (code "99") (name "Net-(R501-1)") (class "Default")
      (node (ref "R501") (pin "P$1") (pinfunction "1_P$1") (pintype "passive"))
      (node (ref "U501") (pin "7") (pinfunction "ILIM_7") (pintype "bidirectional"))
    )
    (net (code "100") (name "Net-(R503-1)") (class "Default")
      (node (ref "Q501") (pin "B") (pinfunction "B_B") (pintype "passive"))
      (node (ref "R503") (pin "P$1") (pinfunction "1_P$1") (pintype "passive"))
    )
    (net (code "101") (name "Net-(R504-1)") (class "Default")
      (node (ref "R504") (pin "P$1") (pinfunction "1_P$1") (pintype "passive"))
      (node (ref "U503") (pin "7") (pinfunction "ILIM_7") (pintype "bidirectional"))
    )
    (net (code "102") (name "Net-(R601-1)") (class "Default")
      (node (ref "R601") (pin "P$1") (pinfunction "1_P$1") (pintype "passive"))
      (node (ref "U601") (pin "4") (pinfunction "~{RESET}_4") (pintype "input"))
    )
    (net (code "103") (name "Net-(R602-1)") (class "Default")
      (node (ref "R602") (pin "P$1") (pinfunction "1_P$1") (pintype "passive"))
      (node (ref "U602") (pin "7") (pinfunction "+IN_7") (pintype "input"))
    )
    (net (code "104") (name "Net-(R603-1)") (class "Default")
      (node (ref "R603") (pin "P$1") (pinfunction "1_P$1") (pintype "passive"))
      (node (ref "R604") (pin "P$2") (pinfunction "2_P$2") (pintype "passive"))
      (node (ref "U602") (pin "8") (pinfunction "-IN_8") (pintype "input"))
    )
    (net (code "105") (name "Net-(R605-2)") (class "Default")
      (node (ref "R605") (pin "P$2") (pinfunction "2_P$2") (pintype "passive"))
      (node (ref "U601") (pin "6") (pinfunction "REXT_6") (pintype "bidirectional"))
    )
    (net (code "106") (name "Net-(R606-2)") (class "Default")
      (node (ref "JP600") (pin "2") (pinfunction "2_2") (pintype "passive"))
      (node (ref "R606") (pin "P$2") (pinfunction "2_P$2") (pintype "passive"))
      (node (ref "R607") (pin "P$1") (pinfunction "1_P$1") (pintype "passive"))
      (node (ref "U602") (pin "2") (pinfunction "FB_2") (pintype "bidirectional"))
    )
    (net (code "107") (name "Net-(R608-2)") (class "Default")
      (node (ref "LED601") (pin "C") (pinfunction "C_C") (pintype "passive"))
      (node (ref "R608") (pin "P$2") (pinfunction "2_P$2") (pintype "passive"))
    )
    (net (code "108") (name "Net-(R609-1)") (class "Default")
      (node (ref "R609") (pin "P$1") (pinfunction "1_P$1") (pintype "passive"))
      (node (ref "R610") (pin "P$2") (pinfunction "2_P$2") (pintype "passive"))
    )
    (net (code "109") (name "Net-(R609-2)") (class "Default")
      (node (ref "LED602") (pin "C") (pinfunction "C_C") (pintype "passive"))
      (node (ref "R609") (pin "P$2") (pinfunction "2_P$2") (pintype "passive"))
    )
    (net (code "110") (name "Net-(R611-1)") (class "Default")
      (node (ref "R611") (pin "P$1") (pinfunction "1_P$1") (pintype "passive"))
      (node (ref "U$12") (pin "2") (pinfunction "2_2") (pintype "passive"))
    )
    (net (code "111") (name "Net-(R612-2)") (class "Default")
      (node (ref "LED603") (pin "C") (pinfunction "C_C") (pintype "passive"))
      (node (ref "R612") (pin "P$2") (pinfunction "2_P$2") (pintype "passive"))
    )
    (net (code "112") (name "Net-(R614-2)") (class "Default")
      (node (ref "JP600") (pin "1") (pinfunction "1_1") (pintype "passive"))
      (node (ref "R614") (pin "P$2") (pinfunction "2_P$2") (pintype "passive"))
    )
    (net (code "113") (name "Net-(R701-2)") (class "Default")
      (node (ref "R701") (pin "P$2") (pinfunction "2_P$2") (pintype "passive"))
      (node (ref "U704") (pin "10") (pinfunction "CH4_10") (pintype "bidirectional"))
    )
    (net (code "114") (name "Net-(R702-2)") (class "Default")
      (node (ref "R702") (pin "P$2") (pinfunction "2_P$2") (pintype "passive"))
      (node (ref "U704") (pin "13") (pinfunction "CH5_13") (pintype "bidirectional"))
    )
    (net (code "115") (name "Net-(R703-2)") (class "Default")
      (node (ref "R703") (pin "P$2") (pinfunction "2_P$2") (pintype "passive"))
      (node (ref "U704") (pin "16") (pinfunction "CH6_16") (pintype "bidirectional"))
    )
    (net (code "116") (name "Net-(R704-2)") (class "Default")
      (node (ref "R704") (pin "P$2") (pinfunction "2_P$2") (pintype "passive"))
      (node (ref "U704") (pin "19") (pinfunction "CH7_19") (pintype "bidirectional"))
    )
    (net (code "117") (name "Net-(R705-2)") (class "Default")
      (node (ref "R705") (pin "P$2") (pinfunction "2_P$2") (pintype "passive"))
      (node (ref "U704") (pin "22") (pinfunction "CH8_22") (pintype "bidirectional"))
    )
    (net (code "118") (name "Net-(R706-2)") (class "Default")
      (node (ref "R706") (pin "P$2") (pinfunction "2_P$2") (pintype "passive"))
      (node (ref "U704") (pin "25") (pinfunction "CH9_25") (pintype "bidirectional"))
    )
    (net (code "119") (name "Net-(R707-2)") (class "Default")
      (node (ref "R707") (pin "P$2") (pinfunction "2_P$2") (pintype "passive"))
      (node (ref "U704") (pin "28") (pinfunction "CH10_28") (pintype "bidirectional"))
    )
    (net (code "120") (name "Net-(R708-2)") (class "Default")
      (node (ref "R708") (pin "P$2") (pinfunction "2_P$2") (pintype "passive"))
      (node (ref "U704") (pin "31") (pinfunction "CH11_31") (pintype "bidirectional"))
    )
    (net (code "121") (name "Net-(R709-2)") (class "Default")
      (node (ref "R709") (pin "P$2") (pinfunction "2_P$2") (pintype "passive"))
      (node (ref "U704") (pin "34") (pinfunction "CH12_34") (pintype "bidirectional"))
    )
    (net (code "122") (name "Net-(R710-2)") (class "Default")
      (node (ref "R710") (pin "P$2") (pinfunction "2_P$2") (pintype "passive"))
      (node (ref "U704") (pin "37") (pinfunction "PPM/S.BUS_OUT_37") (pintype "bidirectional"))
    )
    (net (code "123") (name "Net-(R711-2)") (class "Default")
      (node (ref "R711") (pin "P$2") (pinfunction "2_P$2") (pintype "passive"))
      (node (ref "U704") (pin "40") (pinfunction "PPM/S.BUS_IN_40") (pintype "bidirectional"))
    )
    (net (code "124") (name "Net-(R712-2)") (class "Default")
      (node (ref "R712") (pin "P$2") (pinfunction "2_P$2") (pintype "passive"))
      (node (ref "U704") (pin "7") (pinfunction "CH3_7") (pintype "bidirectional"))
    )
    (net (code "125") (name "Net-(R713-2)") (class "Default")
      (node (ref "R713") (pin "P$2") (pinfunction "2_P$2") (pintype "passive"))
      (node (ref "U704") (pin "4") (pinfunction "CH2_4") (pintype "bidirectional"))
    )
    (net (code "126") (name "Net-(R714-2)") (class "Default")
      (node (ref "R714") (pin "P$2") (pinfunction "2_P$2") (pintype "passive"))
      (node (ref "U704") (pin "1") (pinfunction "CH1_1") (pintype "bidirectional"))
    )
    (net (code "127") (name "Net-(R801-1)") (class "Default")
      (node (ref "J801") (pin "4") (pinfunction "4_4") (pintype "passive"))
      (node (ref "L802") (pin "P$1") (pinfunction "P$1_P$1") (pintype "bidirectional"))
      (node (ref "R801") (pin "P$1") (pinfunction "1_P$1") (pintype "passive"))
    )
    (net (code "128") (name "Net-(R802-1)") (class "Default")
      (node (ref "J801") (pin "3") (pinfunction "3_3") (pintype "passive"))
      (node (ref "L801") (pin "P$1") (pinfunction "P$1_P$1") (pintype "bidirectional"))
      (node (ref "R802") (pin "P$1") (pinfunction "1_P$1") (pintype "passive"))
    )
    (net (code "129") (name "Net-(R804-2)") (class "Default")
      (node (ref "L801") (pin "P$2") (pinfunction "P$2_P$2") (pintype "bidirectional"))
      (node (ref "R804") (pin "P$2") (pinfunction "2_P$2") (pintype "passive"))
    )
    (net (code "130") (name "Net-(R805-2)") (class "Default")
      (node (ref "L802") (pin "P$2") (pinfunction "P$2_P$2") (pintype "bidirectional"))
      (node (ref "R805") (pin "P$2") (pinfunction "2_P$2") (pintype "passive"))
    )
    (net (code "131") (name "Net-(U302-VCCB)") (class "Default")
      (node (ref "J308") (pin "1") (pinfunction "1_1") (pintype "passive"))
      (node (ref "U302") (pin "19") (pinfunction "VCCB_19") (pintype "input"))
    )
    (net (code "132") (name "Net-(U601-OUT0)") (class "Default")
      (node (ref "U601") (pin "9") (pinfunction "OUT0_9") (pintype "open_collector"))
      (node (ref "U603") (pin "C1") (pinfunction "C_C1") (pintype "passive"))
    )
    (net (code "133") (name "Net-(U601-OUT1)") (class "Default")
      (node (ref "U601") (pin "8") (pinfunction "OUT1_8") (pintype "open_collector"))
      (node (ref "U603") (pin "C2") (pinfunction "C_C2") (pintype "passive"))
    )
    (net (code "134") (name "Net-(U601-OUT2)") (class "Default")
      (node (ref "U601") (pin "7") (pinfunction "OUT2_7") (pintype "open_collector"))
      (node (ref "U603") (pin "C3") (pinfunction "C_C3") (pintype "passive"))
    )
    (net (code "135") (name "PPM_INPUT") (class "Default")
      (node (ref "D701") (pin "C") (pinfunction "C_C") (pintype "passive"))
      (node (ref "J701") (pin "P$3") (pinfunction "P$3_P$3") (pintype "bidirectional"))
      (node (ref "R711") (pin "P$1") (pinfunction "1_P$1") (pintype "passive"))
      (node (ref "U$101") (pin "15") (pinfunction "15_PRU0_R31[15]_15") (pintype "passive"))
      (node (ref "U703") (pin "2") (pinfunction "1A_2") (pintype "bidirectional"))
    )
    (net (code "136") (name "PPM{slash}S.BUS_OUT") (class "Default")
      (node (ref "D702") (pin "C") (pinfunction "C_C") (pintype "passive"))
      (node (ref "R710") (pin "P$1") (pinfunction "1_P$1") (pintype "passive"))
      (node (ref "U703") (pin "3") (pinfunction "2Y_3") (pintype "bidirectional"))
    )
    (net (code "137") (name "PRESSURE_SENS") (class "Default")
      (node (ref "C301") (pin "P$1") (pinfunction "1_P$1") (pintype "passive"))
      (node (ref "R303") (pin "P$2") (pinfunction "2_P$2") (pintype "passive"))
      (node (ref "R306") (pin "P$1") (pinfunction "1_P$1") (pintype "passive"))
      (node (ref "U$101") (pin "86") (pinfunction "AIN1_40_86") (pintype "passive"))
    )
    (net (code "138") (name "PRESSURE_SENS_IN") (class "Default")
      (node (ref "ADC_PR") (pin "P$1") (pinfunction "P$1_P$1") (pintype "passive"))
      (node (ref "J305") (pin "2") (pinfunction "2_2") (pintype "passive"))
      (node (ref "R7") (pin "P$2") (pinfunction "2_P$2") (pintype "passive"))
    )
    (net (code "139") (name "S.BUS_INPUT") (class "Default")
      (node (ref "R207") (pin "P$2") (pinfunction "2_P$2") (pintype "passive"))
      (node (ref "S3RX") (pin "P$1") (pinfunction "P$1_P$1") (pintype "passive"))
      (node (ref "U$4") (pin "5") (pinfunction "5_5") (pintype "passive"))
      (node (ref "U703") (pin "6") (pinfunction "1Y_6") (pintype "bidirectional"))
    )
    (net (code "140") (name "S.BUS_OUTPUT") (class "Default")
      (node (ref "R214") (pin "P$2") (pinfunction "2_P$2") (pintype "passive"))
      (node (ref "S3TX") (pin "P$1") (pinfunction "P$1_P$1") (pintype "passive"))
      (node (ref "U$4") (pin "4") (pinfunction "4_4") (pintype "passive"))
      (node (ref "U703") (pin "5") (pinfunction "2A_5") (pintype "bidirectional"))
    )
    (net (code "141") (name "SAFETY") (class "Default")
      (node (ref "R613") (pin "P$1") (pinfunction "1_P$1") (pintype "passive"))
      (node (ref "U$101") (pin "87") (pinfunction "41_PRU0_R30/31[6]_87") (pintype "input"))
      (node (ref "U$12") (pin "3") (pinfunction "3_3") (pintype "passive"))
    )
    (net (code "142") (name "SERIAL0_RX") (class "Default")
      (node (ref "R212") (pin "P$2") (pinfunction "2_P$2") (pintype "passive"))
      (node (ref "U$4") (pin "3") (pinfunction "3_3") (pintype "passive"))
    )
    (net (code "143") (name "SERIAL0_TX") (class "Default")
      (node (ref "R205") (pin "P$2") (pinfunction "2_P$2") (pintype "passive"))
      (node (ref "U$4") (pin "2") (pinfunction "2_2") (pintype "passive"))
    )
    (net (code "144") (name "SERIAL1_CTS") (class "Default")
      (node (ref "R211") (pin "P$2") (pinfunction "2_P$2") (pintype "passive"))
      (node (ref "U$201") (pin "4") (pinfunction "4_4") (pintype "passive"))
    )
    (net (code "145") (name "SERIAL1_RTS") (class "Default")
      (node (ref "R204") (pin "P$2") (pinfunction "2_P$2") (pintype "passive"))
      (node (ref "U$201") (pin "5") (pinfunction "5_5") (pintype "passive"))
    )
    (net (code "146") (name "SERIAL1_RX") (class "Default")
      (node (ref "R203") (pin "P$2") (pinfunction "2_P$2") (pintype "passive"))
      (node (ref "S1RX") (pin "P$1") (pinfunction "P$1_P$1") (pintype "passive"))
      (node (ref "U$201") (pin "3") (pinfunction "3_3") (pintype "passive"))
    )
    (net (code "147") (name "SERIAL1_TX") (class "Default")
      (node (ref "R210") (pin "P$2") (pinfunction "2_P$2") (pintype "passive"))
      (node (ref "S1TX") (pin "P$1") (pinfunction "P$1_P$1") (pintype "passive"))
      (node (ref "U$201") (pin "2") (pinfunction "2_2") (pintype "passive"))
    )
    (net (code "148") (name "SERIAL2_CTS") (class "Default")
      (node (ref "R208") (pin "P$2") (pinfunction "2_P$2") (pintype "passive"))
      (node (ref "U$2") (pin "4") (pinfunction "4_4") (pintype "passive"))
    )
    (net (code "149") (name "SERIAL2_RTS") (class "Default")
      (node (ref "R201") (pin "P$2") (pinfunction "2_P$2") (pintype "passive"))
      (node (ref "U$2") (pin "5") (pinfunction "5_5") (pintype "passive"))
    )
    (net (code "150") (name "SERIAL2_RX") (class "Default")
      (node (ref "R202") (pin "P$2") (pinfunction "2_P$2") (pintype "passive"))
      (node (ref "S2RX") (pin "P$1") (pinfunction "P$1_P$1") (pintype "passive"))
      (node (ref "U$2") (pin "3") (pinfunction "3_3") (pintype "passive"))
    )
    (net (code "151") (name "SERIAL2_TX") (class "Default")
      (node (ref "R209") (pin "P$2") (pinfunction "2_P$2") (pintype "passive"))
      (node (ref "S2TX") (pin "P$1") (pinfunction "P$1_P$1") (pintype "passive"))
      (node (ref "U$2") (pin "2") (pinfunction "2_2") (pintype "passive"))
    )
    (net (code "152") (name "SERIAL4_RX") (class "Default")
      (node (ref "R206") (pin "P$2") (pinfunction "2_P$2") (pintype "passive"))
      (node (ref "S4RX") (pin "P$1") (pinfunction "P$1_P$1") (pintype "passive"))
      (node (ref "U$3") (pin "3") (pinfunction "3_3") (pintype "passive"))
    )
    (net (code "153") (name "SERIAL4_TX") (class "Default")
      (node (ref "R213") (pin "P$2") (pinfunction "2_P$2") (pintype "passive"))
      (node (ref "S4TX") (pin "P$1") (pinfunction "P$1_P$1") (pintype "passive"))
      (node (ref "U$3") (pin "2") (pinfunction "2_2") (pintype "passive"))
    )
    (net (code "154") (name "SERVO_RAIL_IN_~{EN}") (class "Default")
      (node (ref "U$101") (pin "16") (pinfunction "PRU0_R31[14]_16_16") (pintype "passive"))
    )
    (net (code "155") (name "SPI_0_MISO") (class "Default")
      (node (ref "U$101") (pin "64") (pinfunction "SPI_0_MISO_18_64") (pintype "passive"))
      (node (ref "U406") (pin "22") (pinfunction "SDO_G_22") (pintype "bidirectional"))
      (node (ref "U406") (pin "23") (pinfunction "SDO_XM_23") (pintype "bidirectional"))
    )
    (net (code "156") (name "SPI_0_MOSI") (class "Default")
      (node (ref "U$101") (pin "67") (pinfunction "21_SPI_0_MOSI_67") (pintype "passive"))
      (node (ref "U406") (pin "24") (pinfunction "SDA_24") (pintype "bidirectional"))
    )
    (net (code "157") (name "SPI_0_SCK") (class "Default")
      (node (ref "U$101") (pin "68") (pinfunction "SPI_0_SCLK_22_68") (pintype "passive"))
      (node (ref "U406") (pin "21") (pinfunction "SPC_21") (pintype "bidirectional"))
    )
    (net (code "158") (name "SPI_1_MISO") (class "Default")
      (node (ref "U$101") (pin "76") (pinfunction "SPI_1_MISO_30_76") (pintype "passive"))
      (node (ref "U102") (pin "2") (pinfunction "Q_2") (pintype "bidirectional"))
      (node (ref "U401") (pin "6") (pinfunction "SDO_6") (pintype "bidirectional"))
      (node (ref "U403") (pin "9") (pinfunction "AD0/SDO_9") (pintype "bidirectional"))
      (node (ref "U405") (pin "9") (pinfunction "AD0/SDO_9") (pintype "bidirectional"))
      (node (ref "U407") (pin "P$5") (pinfunction "SDO_P$5") (pintype "bidirectional"))
    )
    (net (code "159") (name "SPI_1_MOSI") (class "Default")
      (node (ref "U$101") (pin "75") (pinfunction "29_SPI_1_MOSI_75") (pintype "passive"))
      (node (ref "U102") (pin "5") (pinfunction "D_5") (pintype "bidirectional"))
      (node (ref "U401") (pin "7") (pinfunction "SDI/SDA_7") (pintype "bidirectional"))
      (node (ref "U403") (pin "24") (pinfunction "SDA/SDI_24") (pintype "bidirectional"))
      (node (ref "U405") (pin "24") (pinfunction "SDA/SDI_24") (pintype "bidirectional"))
      (node (ref "U407") (pin "P$3") (pinfunction "SDI_P$3") (pintype "bidirectional"))
    )
    (net (code "160") (name "SPI_1_SCK") (class "Default")
      (node (ref "U$101") (pin "77") (pinfunction "31_SPI_1_SCLK_77") (pintype "passive"))
      (node (ref "U102") (pin "6") (pinfunction "C_6") (pintype "bidirectional"))
      (node (ref "U401") (pin "8") (pinfunction "SCLK_8") (pintype "bidirectional"))
      (node (ref "U403") (pin "23") (pinfunction "SCL/SCLK_23") (pintype "bidirectional"))
      (node (ref "U405") (pin "23") (pinfunction "SCL/SCLK_23") (pintype "bidirectional"))
      (node (ref "U407") (pin "P$4") (pinfunction "SCK_P$4") (pintype "bidirectional"))
    )
    (net (code "161") (name "SPI_1_~{BARO_CS}") (class "Default")
      (node (ref "U$101") (pin "88") (pinfunction "SPI_1_CS1_42_88") (pintype "passive"))
      (node (ref "U401") (pin "5") (pinfunction "CSB2_5") (pintype "bidirectional"))
      (node (ref "U407") (pin "P$2") (pinfunction "CSB_P$2") (pintype "bidirectional"))
    )
    (net (code "162") (name "SPI_1_~{MPU_CS2}") (class "Default")
      (node (ref "U$101") (pin "69") (pinfunction "23_GPIO1[17]_69") (pintype "passive"))
      (node (ref "U405") (pin "22") (pinfunction "~{CS}_22") (pintype "bidirectional"))
    )
    (net (code "163") (name "SPI_1_~{MPU_CS}") (class "Default")
      (node (ref "U$101") (pin "74") (pinfunction "SPI_1_CS0_28_74") (pintype "passive"))
      (node (ref "U403") (pin "8") (pinfunction "/CS_8") (pintype "bidirectional"))
    )
    (net (code "164") (name "SYS_5V") (class "Default")
      (node (ref "F701") (pin "1") (pinfunction "1_1") (pintype "bidirectional"))
      (node (ref "L501") (pin "P$1") (pinfunction "P$1_P$1") (pintype "bidirectional"))
      (node (ref "R508") (pin "P$2") (pinfunction "2_P$2") (pintype "passive"))
      (node (ref "U$101") (pin "53") (pinfunction "7_SYS_5V_53") (pintype "power_in"))
      (node (ref "U$101") (pin "54") (pinfunction "SYS_5V_8_54") (pintype "passive"))
      (node (ref "U501") (pin "1") (pinfunction "IN_1") (pintype "bidirectional"))
      (node (ref "U503") (pin "1") (pinfunction "IN_1") (pintype "bidirectional"))
      (node (ref "U802") (pin "1") (pinfunction "VIN_1") (pintype "bidirectional"))
      (node (ref "VDD_5V_IN") (pin "P$1") (pinfunction "P$1_P$1") (pintype "passive"))
    )
    (net (code "165") (name "UART0_RX") (class "Default")
      (node (ref "U$101") (pin "97") (pinfunction "UART0_RXD_97") (pintype "bidirectional"))
      (node (ref "U202") (pin "5") (pinfunction "A4_5") (pintype "bidirectional"))
    )
    (net (code "166") (name "UART0_TX") (class "Default")
      (node (ref "U$101") (pin "96") (pinfunction "UART0_TXD_96") (pintype "bidirectional"))
      (node (ref "U202") (pin "4") (pinfunction "A3_4") (pintype "bidirectional"))
    )
    (net (code "167") (name "UBLED-SCL") (class "Default")
      (node (ref "U$101") (pin "60") (pinfunction "GPIO1[18]_14_60") (pintype "passive"))
      (node (ref "U302") (pin "3") (pinfunction "A2_3") (pintype "bidirectional"))
    )
    (net (code "168") (name "UBLED-SDA") (class "Default")
      (node (ref "U$101") (pin "62") (pinfunction "GPIO1[19]_16_62") (pintype "passive"))
      (node (ref "U302") (pin "1") (pinfunction "A1_1") (pintype "bidirectional"))
    )
    (net (code "169") (name "USART4_CTS") (class "Default")
      (node (ref "U$101") (pin "35") (pinfunction "35_UART4_CTSN_35") (pintype "passive"))
      (node (ref "U201") (pin "9") (pinfunction "A8_9") (pintype "bidirectional"))
    )
    (net (code "170") (name "USART4_RTS") (class "Default")
      (node (ref "U$101") (pin "33") (pinfunction "33_UART4_RTSN_33") (pintype "passive"))
      (node (ref "U201") (pin "8") (pinfunction "A7_8") (pintype "bidirectional"))
    )
    (net (code "171") (name "USART4_RX") (class "Default")
      (node (ref "U$101") (pin "57") (pinfunction "11_UART4_RXD_57") (pintype "passive"))
      (node (ref "U201") (pin "6") (pinfunction "A5_6") (pintype "bidirectional"))
      (node (ref "U202") (pin "8") (pinfunction "A7_8") (pintype "bidirectional"))
    )
    (net (code "172") (name "USART4_TX") (class "Default")
      (node (ref "U$101") (pin "59") (pinfunction "13_UART4_TXD_59") (pintype "passive"))
      (node (ref "U201") (pin "7") (pinfunction "A6_7") (pintype "bidirectional"))
      (node (ref "U202") (pin "9") (pinfunction "A8_9") (pintype "bidirectional"))
    )
    (net (code "173") (name "USART5_CTS") (class "Default")
      (node (ref "U$101") (pin "31") (pinfunction "31_UART5_CTSN_31") (pintype "passive"))
      (node (ref "U201") (pin "3") (pinfunction "A2_3") (pintype "bidirectional"))
    )
    (net (code "174") (name "USART5_RTS") (class "Default")
      (node (ref "U$101") (pin "32") (pinfunction "UART5_RTSN_32_32") (pintype "passive"))
      (node (ref "U201") (pin "1") (pinfunction "A1_1") (pintype "bidirectional"))
    )
    (net (code "175") (name "USART5_RX") (class "Default")
      (node (ref "U$101") (pin "38") (pinfunction "UART5_RXD_38_38") (pintype "passive"))
      (node (ref "U201") (pin "4") (pinfunction "A3_4") (pintype "bidirectional"))
    )
    (net (code "176") (name "USART5_TX") (class "Default")
      (node (ref "U$101") (pin "37") (pinfunction "37_UART5_TXD_37") (pintype "passive"))
      (node (ref "U201") (pin "5") (pinfunction "A4_5") (pintype "bidirectional"))
    )
    (net (code "177") (name "VDD_3V3_4") (class "Default")
      (node (ref "U$101") (pin "50") (pinfunction "VDD_3V3_4_50") (pintype "power_in"))
    )
    (net (code "178") (name "VDD_3V3_SENSORS") (class "Default")
      (node (ref "C101") (pin "P$1") (pinfunction "1_P$1") (pintype "passive"))
      (node (ref "C305") (pin "P$1") (pinfunction "1_P$1") (pintype "passive"))
      (node (ref "C401") (pin "P$1") (pinfunction "1_P$1") (pintype "passive"))
      (node (ref "C404") (pin "P$1") (pinfunction "1_P$1") (pintype "passive"))
      (node (ref "C405") (pin "P$2") (pinfunction "2_P$2") (pintype "passive"))
      (node (ref "C406") (pin "P$2") (pinfunction "2_P$2") (pintype "passive"))
      (node (ref "C407") (pin "P$1") (pinfunction "1_P$1") (pintype "passive"))
      (node (ref "C408") (pin "P$1") (pinfunction "1_P$1") (pintype "passive"))
      (node (ref "C410") (pin "P$1") (pinfunction "1_P$1") (pintype "passive"))
      (node (ref "C412") (pin "P$1") (pinfunction "1_P$1") (pintype "passive"))
      (node (ref "C413") (pin "P$1") (pinfunction "1_P$1") (pintype "passive"))
      (node (ref "C414") (pin "P$1") (pinfunction "1_P$1") (pintype "passive"))
      (node (ref "C415") (pin "P$1") (pinfunction "1_P$1") (pintype "passive"))
      (node (ref "C508") (pin "P$1") (pinfunction "1_P$1") (pintype "passive"))
      (node (ref "C509") (pin "P$1") (pinfunction "1_P$1") (pintype "passive"))
      (node (ref "Q501") (pin "E") (pinfunction "E_E") (pintype "passive"))
      (node (ref "R103") (pin "P$2") (pinfunction "2_P$2") (pintype "passive"))
      (node (ref "U1") (pin "8") (pinfunction "VCC_8") (pintype "power_in"))
      (node (ref "U102") (pin "3") (pinfunction "~{W}_3") (pintype "bidirectional"))
      (node (ref "U102") (pin "7") (pinfunction "~{HOLD}_7") (pintype "bidirectional"))
      (node (ref "U102") (pin "8") (pinfunction "VDD_8") (pintype "bidirectional"))
      (node (ref "U2") (pin "8") (pinfunction "VCC_8") (pintype "power_in"))
      (node (ref "U401") (pin "1") (pinfunction "VDD_1") (pintype "bidirectional"))
      (node (ref "U402") (pin "1") (pinfunction "VDD_1") (pintype "bidirectional"))
      (node (ref "U402") (pin "2") (pinfunction "PS_2") (pintype "bidirectional"))
      (node (ref "U403") (pin "13") (pinfunction "VDD_13") (pintype "bidirectional"))
      (node (ref "U405") (pin "1") (pinfunction "NC_1") (pintype "bidirectional"))
      (node (ref "U405") (pin "13") (pinfunction "VDD_13") (pintype "bidirectional"))
      (node (ref "U405") (pin "8") (pinfunction "VDDIO_8") (pintype "bidirectional"))
      (node (ref "U406") (pin "15") (pinfunction "VDD_15") (pintype "bidirectional"))
      (node (ref "U406") (pin "16") (pinfunction "VDD_16") (pintype "bidirectional"))
      (node (ref "U406") (pin "17") (pinfunction "VDD_17") (pintype "bidirectional"))
      (node (ref "U406") (pin "18") (pinfunction "VDD_IO_18") (pintype "bidirectional"))
      (node (ref "U407") (pin "P$6") (pinfunction "VDDIO_P$6") (pintype "bidirectional"))
      (node (ref "U407") (pin "P$8") (pinfunction "VDD_P$8") (pintype "bidirectional"))
      (node (ref "U502") (pin "8") (pinfunction "VOUT1_8") (pintype "bidirectional"))
      (node (ref "VDDA_3V901") (pin "P$1") (pinfunction "P$1_P$1") (pintype "passive"))
    )
    (net (code "179") (name "VDD_3V3_SPEKTRUM") (class "Default")
      (node (ref "C805") (pin "P$1") (pinfunction "1_P$1") (pintype "passive"))
      (node (ref "D703") (pin "C") (pinfunction "C_C") (pintype "passive"))
      (node (ref "J701") (pin "P$1") (pinfunction "P$1_P$1") (pintype "bidirectional"))
      (node (ref "U802") (pin "8") (pinfunction "VOUT1_8") (pintype "bidirectional"))
    )
    (net (code "180") (name "VDD_3V3_SPEKTRUM_EN") (class "Default")
      (node (ref "R806") (pin "P$2") (pinfunction "2_P$2") (pintype "passive"))
      (node (ref "U$101") (pin "17") (pinfunction "17_GPIO0[27]_17") (pintype "passive"))
      (node (ref "U201") (pin "10") (pinfunction "OE_10") (pintype "input"))
      (node (ref "U202") (pin "10") (pinfunction "OE_10") (pintype "input"))
      (node (ref "U502") (pin "3") (pinfunction "POR2_3") (pintype "bidirectional"))
      (node (ref "U701") (pin "10") (pinfunction "OE_10") (pintype "input"))
      (node (ref "U702") (pin "10") (pinfunction "OE_10") (pintype "input"))
      (node (ref "U802") (pin "5") (pinfunction "EN1_5") (pintype "bidirectional"))
    )
    (net (code "181") (name "VDD_5V") (class "Default")
      (node (ref "C801") (pin "P$1") (pinfunction "1_P$1") (pintype "passive"))
      (node (ref "J801") (pin "1") (pinfunction "1_1") (pintype "passive"))
      (node (ref "J801") (pin "2") (pinfunction "2_2") (pintype "passive"))
      (node (ref "U$101") (pin "51") (pinfunction "5_VDD_5V_51") (pintype "power_in"))
      (node (ref "U$101") (pin "52") (pinfunction "VDD_5V_6_52") (pintype "power_in"))
      (node (ref "VDD_5V_BRICK") (pin "P$1") (pinfunction "P$1_P$1") (pintype "passive"))
    )
    (net (code "182") (name "VDD_5V_HIPOWER") (class "Default")
      (node (ref "C504") (pin "P$1") (pinfunction "1_P$1") (pintype "passive"))
      (node (ref "L201") (pin "P$1") (pinfunction "P$1_P$1") (pintype "bidirectional"))
      (node (ref "U501") (pin "8") (pinfunction "OUT_8") (pintype "bidirectional"))
    )
    (net (code "183") (name "VDD_5V_PERIPH") (class "Default")
      (node (ref "C510") (pin "P$1") (pinfunction "1_P$1") (pintype "passive"))
      (node (ref "C602") (pin "P$1") (pinfunction "1_P$1") (pintype "passive"))
      (node (ref "L202") (pin "P$1") (pinfunction "P$1_P$1") (pintype "bidirectional"))
      (node (ref "L203") (pin "P$1") (pinfunction "P$1_P$1") (pintype "bidirectional"))
      (node (ref "L301") (pin "P$1") (pinfunction "P$1_P$1") (pintype "bidirectional"))
      (node (ref "L302") (pin "P$1") (pinfunction "P$1_P$1") (pintype "bidirectional"))
      (node (ref "L303") (pin "P$1") (pinfunction "P$1_P$1") (pintype "bidirectional"))
      (node (ref "L601") (pin "P$1") (pinfunction "1_P$1") (pintype "passive"))
      (node (ref "LED601") (pin "A") (pinfunction "A_A") (pintype "passive"))
      (node (ref "LED602") (pin "A") (pinfunction "A_A") (pintype "passive"))
      (node (ref "LED603") (pin "A") (pinfunction "A_A") (pintype "passive"))
      (node (ref "U503") (pin "8") (pinfunction "OUT_8") (pintype "bidirectional"))
      (node (ref "U602") (pin "3") (pinfunction "VIN_3") (pintype "power_in"))
      (node (ref "U603") (pin "A1") (pinfunction "A_A1") (pintype "passive"))
      (node (ref "U603") (pin "A2") (pinfunction "A_A2") (pintype "passive"))
      (node (ref "U603") (pin "A3") (pinfunction "A_A3") (pintype "passive"))
    )
    (net (code "184") (name "VDD_5V_SENS") (class "Default")
      (node (ref "R4") (pin "P$1") (pinfunction "1_P$1") (pintype "passive"))
      (node (ref "R509") (pin "P$1") (pinfunction "1_P$1") (pintype "passive"))
      (node (ref "U$101") (pin "79") (pinfunction "33_AIN4_79") (pintype "passive"))
    )
    (net (code "185") (name "VDD_SERVO_IN") (class "Default")
      (node (ref "L701") (pin "P$2") (pinfunction "P$2_P$2") (pintype "bidirectional"))
    )
    (net (code "186") (name "VDD_SERVO_SENS") (class "Default")
      (node (ref "R3") (pin "P$1") (pinfunction "1_P$1") (pintype "passive"))
      (node (ref "R716") (pin "P$2") (pinfunction "2_P$2") (pintype "passive"))
      (node (ref "U$101") (pin "85") (pinfunction "39_AIN0_85") (pintype "power_in"))
    )
    (net (code "187") (name "unconnected-(U$3-Pad4)") (class "Default")
      (node (ref "U$3") (pin "4") (pinfunction "4_4") (pintype "passive"))
    )
    (net (code "188") (name "unconnected-(U$3-Pad5)") (class "Default")
      (node (ref "U$3") (pin "5") (pinfunction "5_5") (pintype "passive"))
    )
    (net (code "189") (name "unconnected-(U$3-Pad6)") (class "Default")
      (node (ref "U$3") (pin "6") (pinfunction "6_6") (pintype "passive"))
    )
    (net (code "190") (name "unconnected-(U$101-3_MMC1-Pad3)") (class "Default")
      (node (ref "U$101") (pin "3") (pinfunction "3_MMC1_3") (pintype "passive"))
    )
    (net (code "191") (name "unconnected-(U$101-5_MMC1-Pad5)") (class "Default")
      (node (ref "U$101") (pin "5") (pinfunction "5_MMC1_5") (pintype "passive"))
    )
    (net (code "192") (name "unconnected-(U$101-9_PWR_BUT-Pad55)") (class "Default")
      (node (ref "U$101") (pin "55") (pinfunction "9_PWR_BUT_55") (pintype "passive"))
    )
    (net (code "193") (name "unconnected-(U$101-21_MMC1-Pad21)") (class "Default")
      (node (ref "U$101") (pin "21") (pinfunction "21_MMC1_21") (pintype "passive"))
    )
    (net (code "194") (name "unconnected-(U$101-23_MMC1-Pad23)") (class "Default")
      (node (ref "U$101") (pin "23") (pinfunction "23_MMC1_23") (pintype "passive"))
    )
    (net (code "195") (name "unconnected-(U$101-25_MMC1-Pad25)") (class "Default")
      (node (ref "U$101") (pin "25") (pinfunction "25_MMC1_25") (pintype "passive"))
    )
    (net (code "196") (name "unconnected-(U$101-MMC1_3-Pad6)") (class "Default")
      (node (ref "U$101") (pin "6") (pinfunction "MMC1_3_6") (pintype "passive"))
    )
    (net (code "197") (name "unconnected-(U$101-MMC1_4-Pad4)") (class "Default")
      (node (ref "U$101") (pin "4") (pinfunction "MMC1_4_4") (pintype "passive"))
    )
    (net (code "198") (name "unconnected-(U$101-MMC1_20-Pad20)") (class "Default")
      (node (ref "U$101") (pin "20") (pinfunction "MMC1_20_20") (pintype "passive"))
    )
    (net (code "199") (name "unconnected-(U$101-MMC1_22-Pad22)") (class "Default")
      (node (ref "U$101") (pin "22") (pinfunction "MMC1_22_22") (pintype "passive"))
    )
    (net (code "200") (name "unconnected-(U$101-MMC1_24-Pad24)") (class "Default")
      (node (ref "U$101") (pin "24") (pinfunction "MMC1_24_24") (pintype "passive"))
    )
    (net (code "201") (name "unconnected-(U$101-NC-Pad94)") (class "Default")
      (node (ref "U$101") (pin "94") (pinfunction "NC_94") (pintype "bidirectional"))
    )
    (net (code "202") (name "unconnected-(U$101-NC-Pad95)") (class "Default")
      (node (ref "U$101") (pin "95") (pinfunction "NC_95") (pintype "bidirectional"))
    )
    (net (code "203") (name "unconnected-(U$101-NC-Pad98)") (class "Default")
      (node (ref "U$101") (pin "98") (pinfunction "NC_98") (pintype "bidirectional"))
    )
    (net (code "204") (name "unconnected-(U$101-VDD_ADC_32-Pad78)") (class "Default")
      (node (ref "U$101") (pin "78") (pinfunction "VDD_ADC_32_78") (pintype "passive"))
    )
    (net (code "205") (name "unconnected-(U1-WP-Pad7)") (class "Default")
      (node (ref "U1") (pin "7") (pinfunction "WP_7") (pintype "bidirectional"))
    )
    (net (code "206") (name "unconnected-(U2-A0-Pad1)") (class "Default")
      (node (ref "U2") (pin "1") (pinfunction "A0_1") (pintype "bidirectional"))
    )
    (net (code "207") (name "unconnected-(U2-A1-Pad2)") (class "Default")
      (node (ref "U2") (pin "2") (pinfunction "A1_2") (pintype "bidirectional"))
    )
    (net (code "208") (name "unconnected-(U2-A2-Pad3)") (class "Default")
      (node (ref "U2") (pin "3") (pinfunction "A2_3") (pintype "bidirectional"))
    )
    (net (code "209") (name "unconnected-(U2-WP-Pad7)") (class "Default")
      (node (ref "U2") (pin "7") (pinfunction "WP_7") (pintype "bidirectional"))
    )
    (net (code "210") (name "unconnected-(U202-A1-Pad1)") (class "Default")
      (node (ref "U202") (pin "1") (pinfunction "A1_1") (pintype "bidirectional"))
    )
    (net (code "211") (name "unconnected-(U202-A2-Pad3)") (class "Default")
      (node (ref "U202") (pin "3") (pinfunction "A2_3") (pintype "bidirectional"))
    )
    (net (code "212") (name "unconnected-(U202-B1-Pad20)") (class "Default")
      (node (ref "U202") (pin "20") (pinfunction "B1_20") (pintype "bidirectional"))
    )
    (net (code "213") (name "unconnected-(U202-B2-Pad18)") (class "Default")
      (node (ref "U202") (pin "18") (pinfunction "B2_18") (pintype "bidirectional"))
    )
    (net (code "214") (name "unconnected-(U302-A3-Pad4)") (class "Default")
      (node (ref "U302") (pin "4") (pinfunction "A3_4") (pintype "bidirectional"))
    )
    (net (code "215") (name "unconnected-(U302-A4-Pad5)") (class "Default")
      (node (ref "U302") (pin "5") (pinfunction "A4_5") (pintype "bidirectional"))
    )
    (net (code "216") (name "unconnected-(U302-A5-Pad6)") (class "Default")
      (node (ref "U302") (pin "6") (pinfunction "A5_6") (pintype "bidirectional"))
    )
    (net (code "217") (name "unconnected-(U302-A6-Pad7)") (class "Default")
      (node (ref "U302") (pin "7") (pinfunction "A6_7") (pintype "bidirectional"))
    )
    (net (code "218") (name "unconnected-(U302-A7-Pad8)") (class "Default")
      (node (ref "U302") (pin "8") (pinfunction "A7_8") (pintype "bidirectional"))
    )
    (net (code "219") (name "unconnected-(U302-A8-Pad9)") (class "Default")
      (node (ref "U302") (pin "9") (pinfunction "A8_9") (pintype "bidirectional"))
    )
    (net (code "220") (name "unconnected-(U302-B3-Pad17)") (class "Default")
      (node (ref "U302") (pin "17") (pinfunction "B3_17") (pintype "bidirectional"))
    )
    (net (code "221") (name "unconnected-(U302-B4-Pad16)") (class "Default")
      (node (ref "U302") (pin "16") (pinfunction "B4_16") (pintype "bidirectional"))
    )
    (net (code "222") (name "unconnected-(U302-B5-Pad15)") (class "Default")
      (node (ref "U302") (pin "15") (pinfunction "B5_15") (pintype "bidirectional"))
    )
    (net (code "223") (name "unconnected-(U302-B6-Pad14)") (class "Default")
      (node (ref "U302") (pin "14") (pinfunction "B6_14") (pintype "bidirectional"))
    )
    (net (code "224") (name "unconnected-(U302-B7-Pad13)") (class "Default")
      (node (ref "U302") (pin "13") (pinfunction "B7_13") (pintype "bidirectional"))
    )
    (net (code "225") (name "unconnected-(U302-B8-Pad12)") (class "Default")
      (node (ref "U302") (pin "12") (pinfunction "B8_12") (pintype "bidirectional"))
    )
    (net (code "226") (name "unconnected-(U401-CSB1-Pad4)") (class "Default")
      (node (ref "U401") (pin "4") (pinfunction "CSB1_4") (pintype "bidirectional"))
    )
    (net (code "227") (name "unconnected-(U402-CSB2-Pad5)") (class "Default")
      (node (ref "U402") (pin "5") (pinfunction "CSB2_5") (pintype "bidirectional"))
    )
    (net (code "228") (name "unconnected-(U402-SDO-Pad6)") (class "Default")
      (node (ref "U402") (pin "6") (pinfunction "SDO_6") (pintype "bidirectional"))
    )
    (net (code "229") (name "unconnected-(U403-AUX_CL-Pad7)") (class "Default")
      (node (ref "U403") (pin "7") (pinfunction "AUX_CL_7") (pintype "bidirectional"))
    )
    (net (code "230") (name "unconnected-(U403-AUX_DA-Pad6)") (class "Default")
      (node (ref "U403") (pin "6") (pinfunction "AUX_DA_6") (pintype "bidirectional"))
    )
    (net (code "231") (name "unconnected-(U403-CLKOUT-Pad22)") (class "Default")
      (node (ref "U403") (pin "22") (pinfunction "CLKOUT_22") (pintype "bidirectional"))
    )
    (net (code "232") (name "unconnected-(U403-NC1-Pad2)") (class "Default")
      (node (ref "U403") (pin "2") (pinfunction "NC1_2") (pintype "bidirectional"))
    )
    (net (code "233") (name "unconnected-(U403-NC2-Pad3)") (class "Default")
      (node (ref "U403") (pin "3") (pinfunction "NC2_3") (pintype "bidirectional"))
    )
    (net (code "234") (name "unconnected-(U403-NC3-Pad4)") (class "Default")
      (node (ref "U403") (pin "4") (pinfunction "NC3_4") (pintype "bidirectional"))
    )
    (net (code "235") (name "unconnected-(U403-NC4-Pad5)") (class "Default")
      (node (ref "U403") (pin "5") (pinfunction "NC4_5") (pintype "bidirectional"))
    )
    (net (code "236") (name "unconnected-(U403-NC5-Pad14)") (class "Default")
      (node (ref "U403") (pin "14") (pinfunction "NC5_14") (pintype "bidirectional"))
    )
    (net (code "237") (name "unconnected-(U403-NC6-Pad15)") (class "Default")
      (node (ref "U403") (pin "15") (pinfunction "NC6_15") (pintype "bidirectional"))
    )
    (net (code "238") (name "unconnected-(U403-NC7-Pad16)") (class "Default")
      (node (ref "U403") (pin "16") (pinfunction "NC7_16") (pintype "bidirectional"))
    )
    (net (code "239") (name "unconnected-(U403-NC8-Pad17)") (class "Default")
      (node (ref "U403") (pin "17") (pinfunction "NC8_17") (pintype "bidirectional"))
    )
    (net (code "240") (name "unconnected-(U403-RESV1-Pad19)") (class "Default")
      (node (ref "U403") (pin "19") (pinfunction "RESV1_19") (pintype "bidirectional"))
    )
    (net (code "241") (name "unconnected-(U403-RESV2-Pad21)") (class "Default")
      (node (ref "U403") (pin "21") (pinfunction "RESV2_21") (pintype "bidirectional"))
    )
    (net (code "242") (name "unconnected-(U405-AUX_CL-Pad7)") (class "Default")
      (node (ref "U405") (pin "7") (pinfunction "AUX_CL_7") (pintype "bidirectional"))
    )
    (net (code "243") (name "unconnected-(U405-AUX_DA-Pad21)") (class "Default")
      (node (ref "U405") (pin "21") (pinfunction "AUX_DA_21") (pintype "bidirectional"))
    )
    (net (code "244") (name "unconnected-(U405-NC-Pad2)") (class "Default")
      (node (ref "U405") (pin "2") (pinfunction "NC_2") (pintype "bidirectional"))
    )
    (net (code "245") (name "unconnected-(U405-NC-Pad3)") (class "Default")
      (node (ref "U405") (pin "3") (pinfunction "NC_3") (pintype "bidirectional"))
    )
    (net (code "246") (name "unconnected-(U405-NC-Pad4)") (class "Default")
      (node (ref "U405") (pin "4") (pinfunction "NC_4") (pintype "bidirectional"))
    )
    (net (code "247") (name "unconnected-(U405-NC-Pad5)") (class "Default")
      (node (ref "U405") (pin "5") (pinfunction "NC_5") (pintype "bidirectional"))
    )
    (net (code "248") (name "unconnected-(U405-NC-Pad6)") (class "Default")
      (node (ref "U405") (pin "6") (pinfunction "NC_6") (pintype "bidirectional"))
    )
    (net (code "249") (name "unconnected-(U405-NC-Pad14)") (class "Default")
      (node (ref "U405") (pin "14") (pinfunction "NC_14") (pintype "bidirectional"))
    )
    (net (code "250") (name "unconnected-(U405-NC-Pad15)") (class "Default")
      (node (ref "U405") (pin "15") (pinfunction "NC_15") (pintype "bidirectional"))
    )
    (net (code "251") (name "unconnected-(U405-NC-Pad16)") (class "Default")
      (node (ref "U405") (pin "16") (pinfunction "NC_16") (pintype "bidirectional"))
    )
    (net (code "252") (name "unconnected-(U405-NC-Pad17)") (class "Default")
      (node (ref "U405") (pin "17") (pinfunction "NC_17") (pintype "bidirectional"))
    )
    (net (code "253") (name "unconnected-(U405-RESV-Pad19)") (class "Default")
      (node (ref "U405") (pin "19") (pinfunction "RESV_19") (pintype "bidirectional"))
    )
    (net (code "254") (name "unconnected-(U406-DEN_G-Pad10)") (class "Default")
      (node (ref "U406") (pin "10") (pinfunction "DEN_G_10") (pintype "bidirectional"))
    )
    (net (code "255") (name "unconnected-(U406-INT_G-Pad11)") (class "Default")
      (node (ref "U406") (pin "11") (pinfunction "INT_G_11") (pintype "bidirectional"))
    )
    (net (code "256") (name "unconnected-(U406-NC-Pad1)") (class "Default")
      (node (ref "U406") (pin "1") (pinfunction "NC_1") (pintype "bidirectional"))
    )
    (net (code "257") (name "unconnected-(U701-A5-Pad6)") (class "Default")
      (node (ref "U701") (pin "6") (pinfunction "A5_6") (pintype "bidirectional"))
    )
    (net (code "258") (name "unconnected-(U701-A6-Pad7)") (class "Default")
      (node (ref "U701") (pin "7") (pinfunction "A6_7") (pintype "bidirectional"))
    )
    (net (code "259") (name "unconnected-(U701-A7-Pad8)") (class "Default")
      (node (ref "U701") (pin "8") (pinfunction "A7_8") (pintype "bidirectional"))
    )
    (net (code "260") (name "unconnected-(U701-A8-Pad9)") (class "Default")
      (node (ref "U701") (pin "9") (pinfunction "A8_9") (pintype "bidirectional"))
    )
    (net (code "261") (name "unconnected-(U701-B5-Pad15)") (class "Default")
      (node (ref "U701") (pin "15") (pinfunction "B5_15") (pintype "bidirectional"))
    )
    (net (code "262") (name "unconnected-(U701-B6-Pad14)") (class "Default")
      (node (ref "U701") (pin "14") (pinfunction "B6_14") (pintype "bidirectional"))
    )
    (net (code "263") (name "unconnected-(U701-B7-Pad13)") (class "Default")
      (node (ref "U701") (pin "13") (pinfunction "B7_13") (pintype "bidirectional"))
    )
    (net (code "264") (name "unconnected-(U701-B8-Pad12)") (class "Default")
      (node (ref "U701") (pin "12") (pinfunction "B8_12") (pintype "bidirectional"))
    )
    (net (code "265") (name "unconnected-(U802-CSET-Pad6)") (class "Default")
      (node (ref "U802") (pin "6") (pinfunction "CSET_6") (pintype "bidirectional"))
    )
    (net (code "266") (name "unconnected-(U802-POR2-Pad3)") (class "Default")
      (node (ref "U802") (pin "3") (pinfunction "POR2_3") (pintype "bidirectional"))
    )
    (net (code "267") (name "unconnected-(U802-VOUT2-Pad7)") (class "Default")
      (node (ref "U802") (pin "7") (pinfunction "VOUT2_7") (pintype "bidirectional"))
    )
    (net (code "268") (name "~{ACCEL_MAG_CS}") (class "Default")
      (node (ref "U$101") (pin "63") (pinfunction "17_SPI_0_CS0_63") (pintype "passive"))
      (node (ref "U406") (pin "20") (pinfunction "CS_XM_20") (pintype "bidirectional"))
    )
    (net (code "269") (name "~{FRAM_CS}") (class "Default")
      (node (ref "U$101") (pin "12") (pinfunction "PRU0_R30[14]_12_12") (pintype "passive"))
      (node (ref "U102") (pin "1") (pinfunction "~{S}_1") (pintype "bidirectional"))
    )
    (net (code "270") (name "~{GYRO_CS}") (class "Default")
      (node (ref "U$101") (pin "9") (pinfunction "9_GPIO2[5]_9") (pintype "passive"))
      (node (ref "U406") (pin "19") (pinfunction "CS_G_19") (pintype "bidirectional"))
    )
    (net (code "271") (name "~{LED_AMBER}") (class "Default")
      (node (ref "R610") (pin "P$1") (pinfunction "1_P$1") (pintype "passive"))
      (node (ref "U$101") (pin "71") (pinfunction "25_PRU0_R30/31[7]_71") (pintype "passive"))
    )
    (net (code "272") (name "~{LED_BLUE}") (class "Default")
      (node (ref "R612") (pin "P$1") (pinfunction "1_P$1") (pintype "passive"))
      (node (ref "U$101") (pin "61") (pinfunction "15_GPIO1[16]_61") (pintype "passive"))
    )
    (net (code "273") (name "~{LED_SAFETY}") (class "Default")
      (node (ref "R611") (pin "P$2") (pinfunction "2_P$2") (pintype "passive"))
      (node (ref "U$101") (pin "26") (pinfunction "GPIO1[29]_26_26") (pintype "passive"))
    )
    (net (code "274") (name "~{SBUS_OUTPUT_EN}") (class "Default")
      (node (ref "U$101") (pin "11") (pinfunction "11_PRU0_R30[15]_11") (pintype "passive"))
      (node (ref "U703") (pin "7") (pinfunction "~{2OE}_7") (pintype "input"))
    )
    (net (code "275") (name "~{VDD_5V_HIPOWER_OC}") (class "Default")
      (node (ref "R502") (pin "P$1") (pinfunction "1_P$1") (pintype "passive"))
      (node (ref "U$101") (pin "19") (pinfunction "19_GPIO0[22]_19") (pintype "passive"))
      (node (ref "U501") (pin "4") (pinfunction "~{FAULT}_4") (pintype "bidirectional"))
    )
    (net (code "276") (name "~{VDD_5V_PERIPH_EN}") (class "Default")
      (node (ref "R506") (pin "P$1") (pinfunction "1_P$1") (pintype "passive"))
      (node (ref "U$101") (pin "58") (pinfunction "GPIO1[28]_12_58") (pintype "passive"))
      (node (ref "U501") (pin "5") (pinfunction "~{CE}_5") (pintype "bidirectional"))
      (node (ref "U503") (pin "5") (pinfunction "~{CE}_5") (pintype "bidirectional"))
    )
    (net (code "277") (name "~{VDD_5V_PERIPH_OC}") (class "Default")
      (node (ref "R507") (pin "P$1") (pinfunction "1_P$1") (pintype "passive"))
      (node (ref "U$101") (pin "13") (pinfunction "13_GPIO0[23]_13") (pintype "passive"))
      (node (ref "U503") (pin "4") (pinfunction "~{FAULT}_4") (pintype "bidirectional"))
    )
    (net (code "278") (name "~{VDD_SERVO_IN_FAULT}") (class "Default")
      (node (ref "U$101") (pin "18") (pinfunction "GPIO2[1]_18_18") (pintype "passive"))
    )
  )
)
